# SCH_Central_Unit_for_AgOpenGPS_Zentralba.net
KiCad netlist of a schematic drawn in EasyEDA
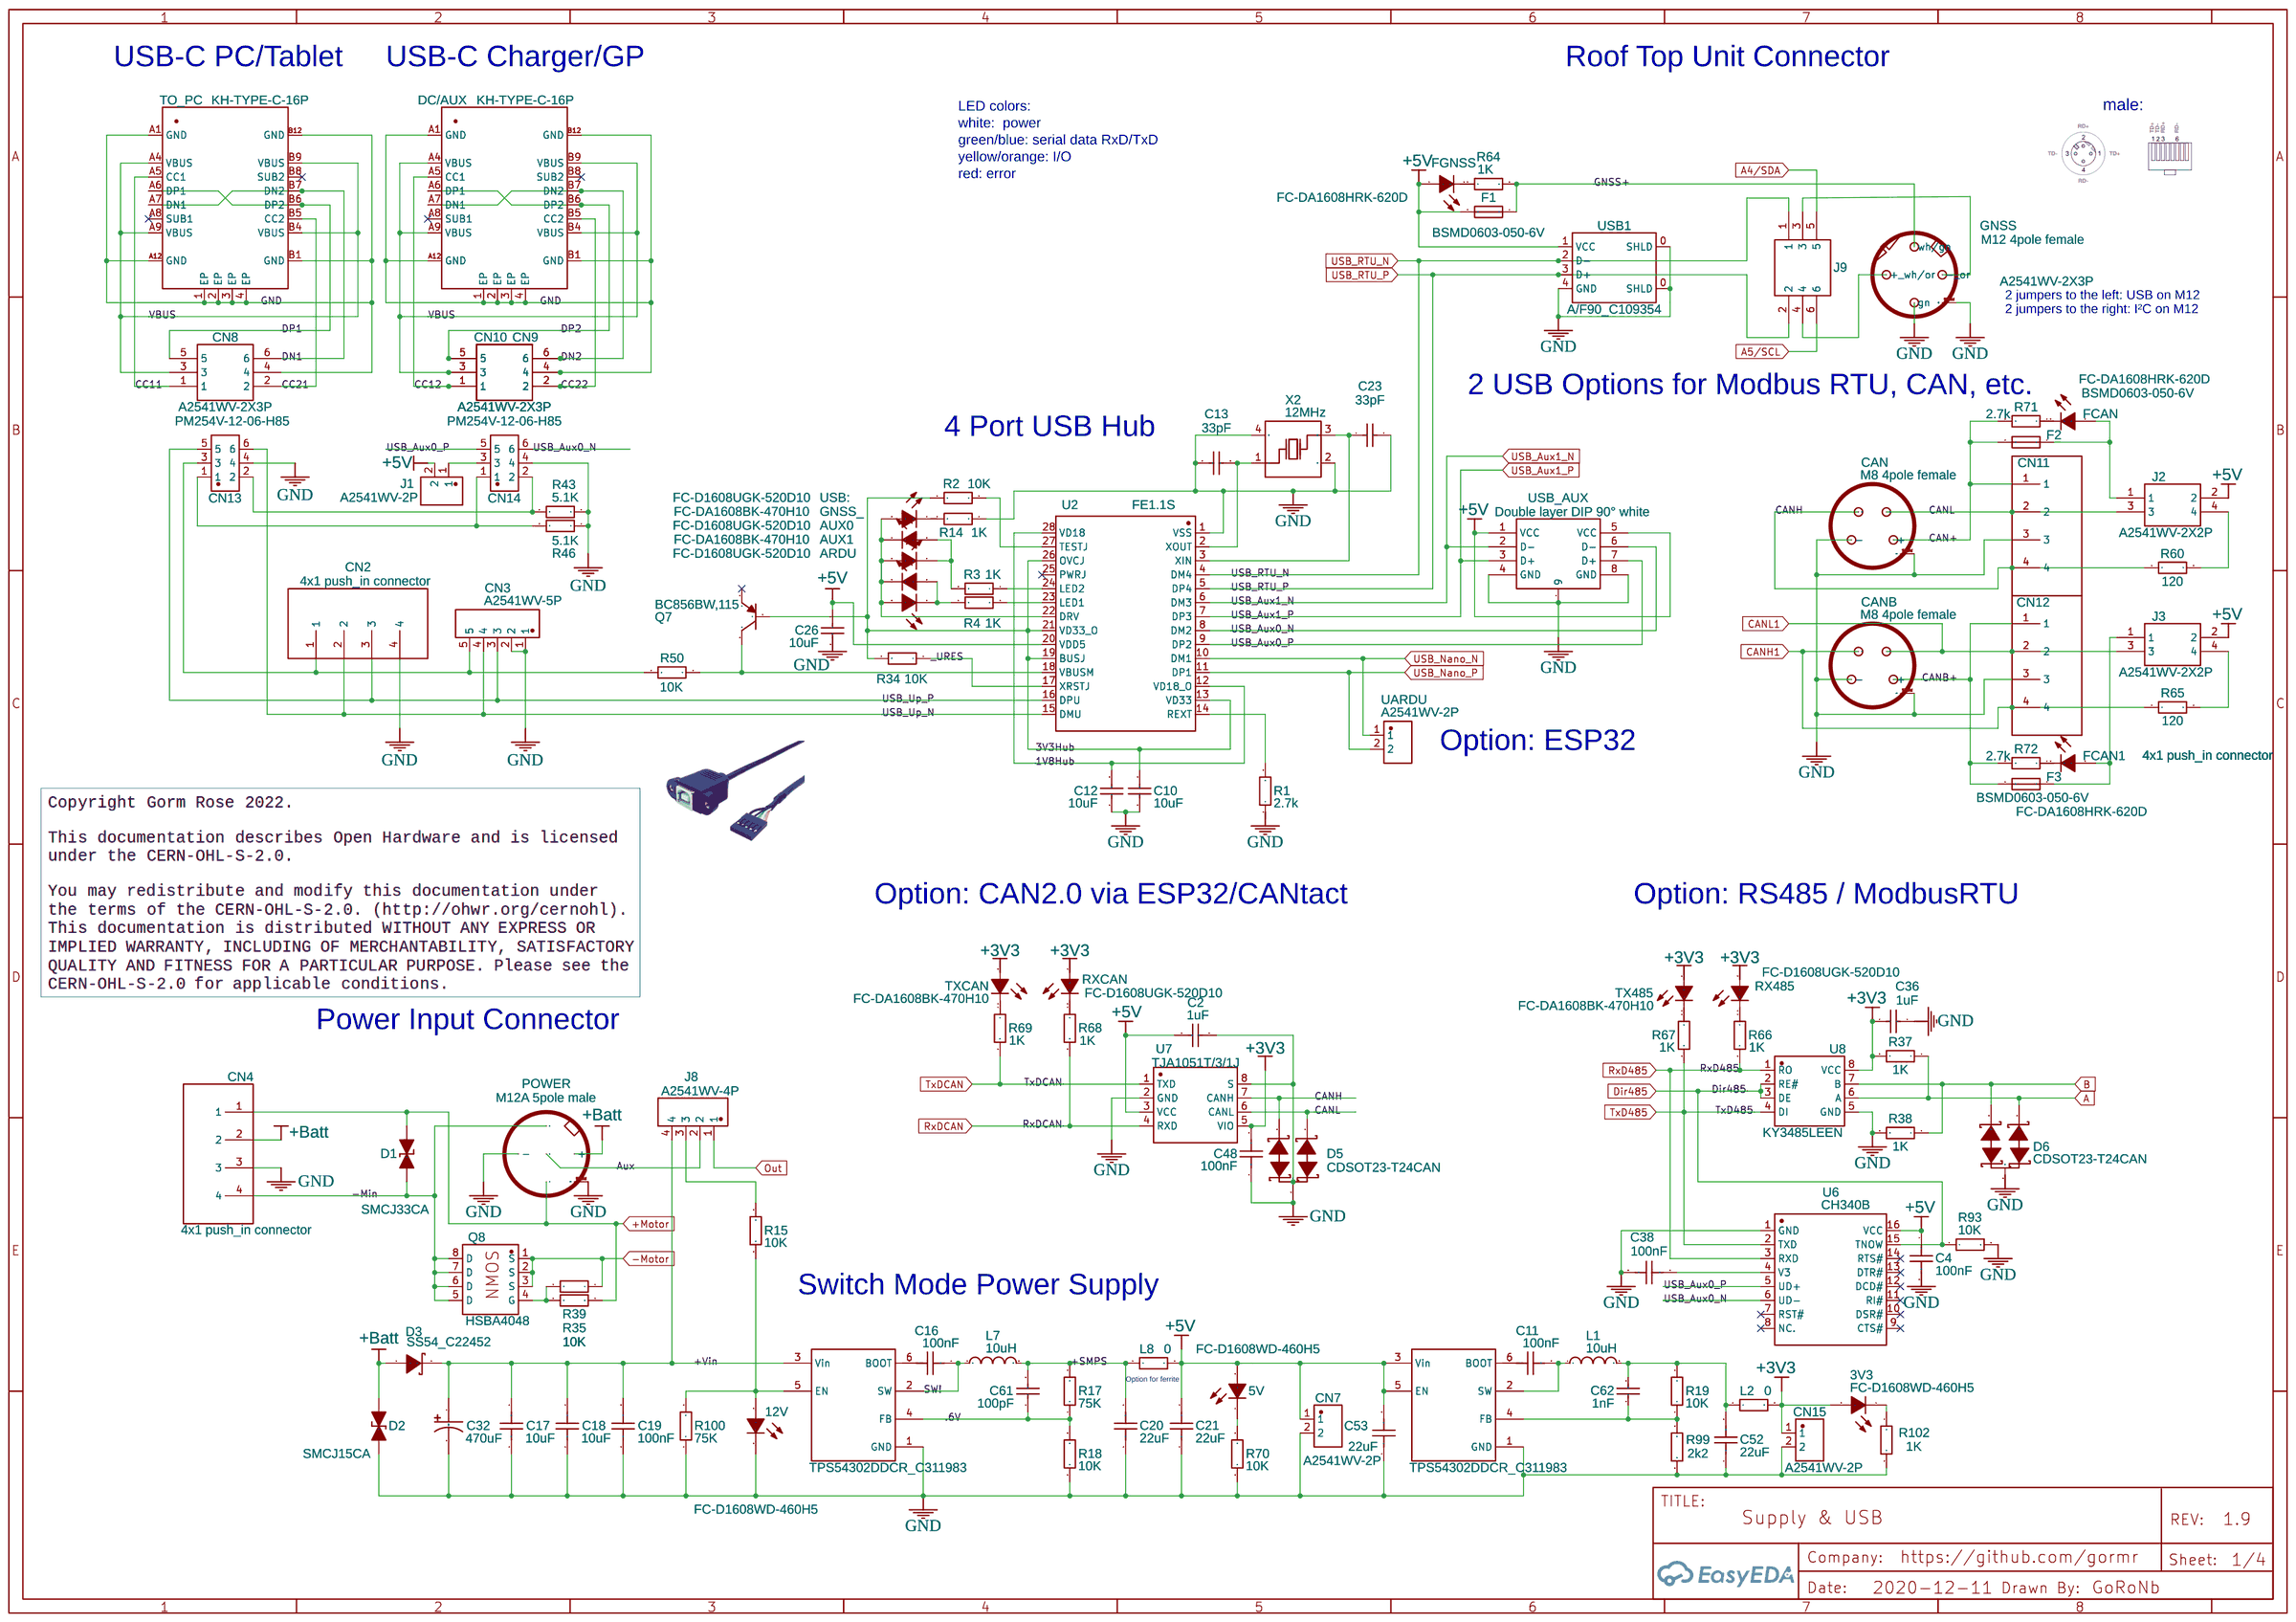
[diagram p0: Supply_USB]
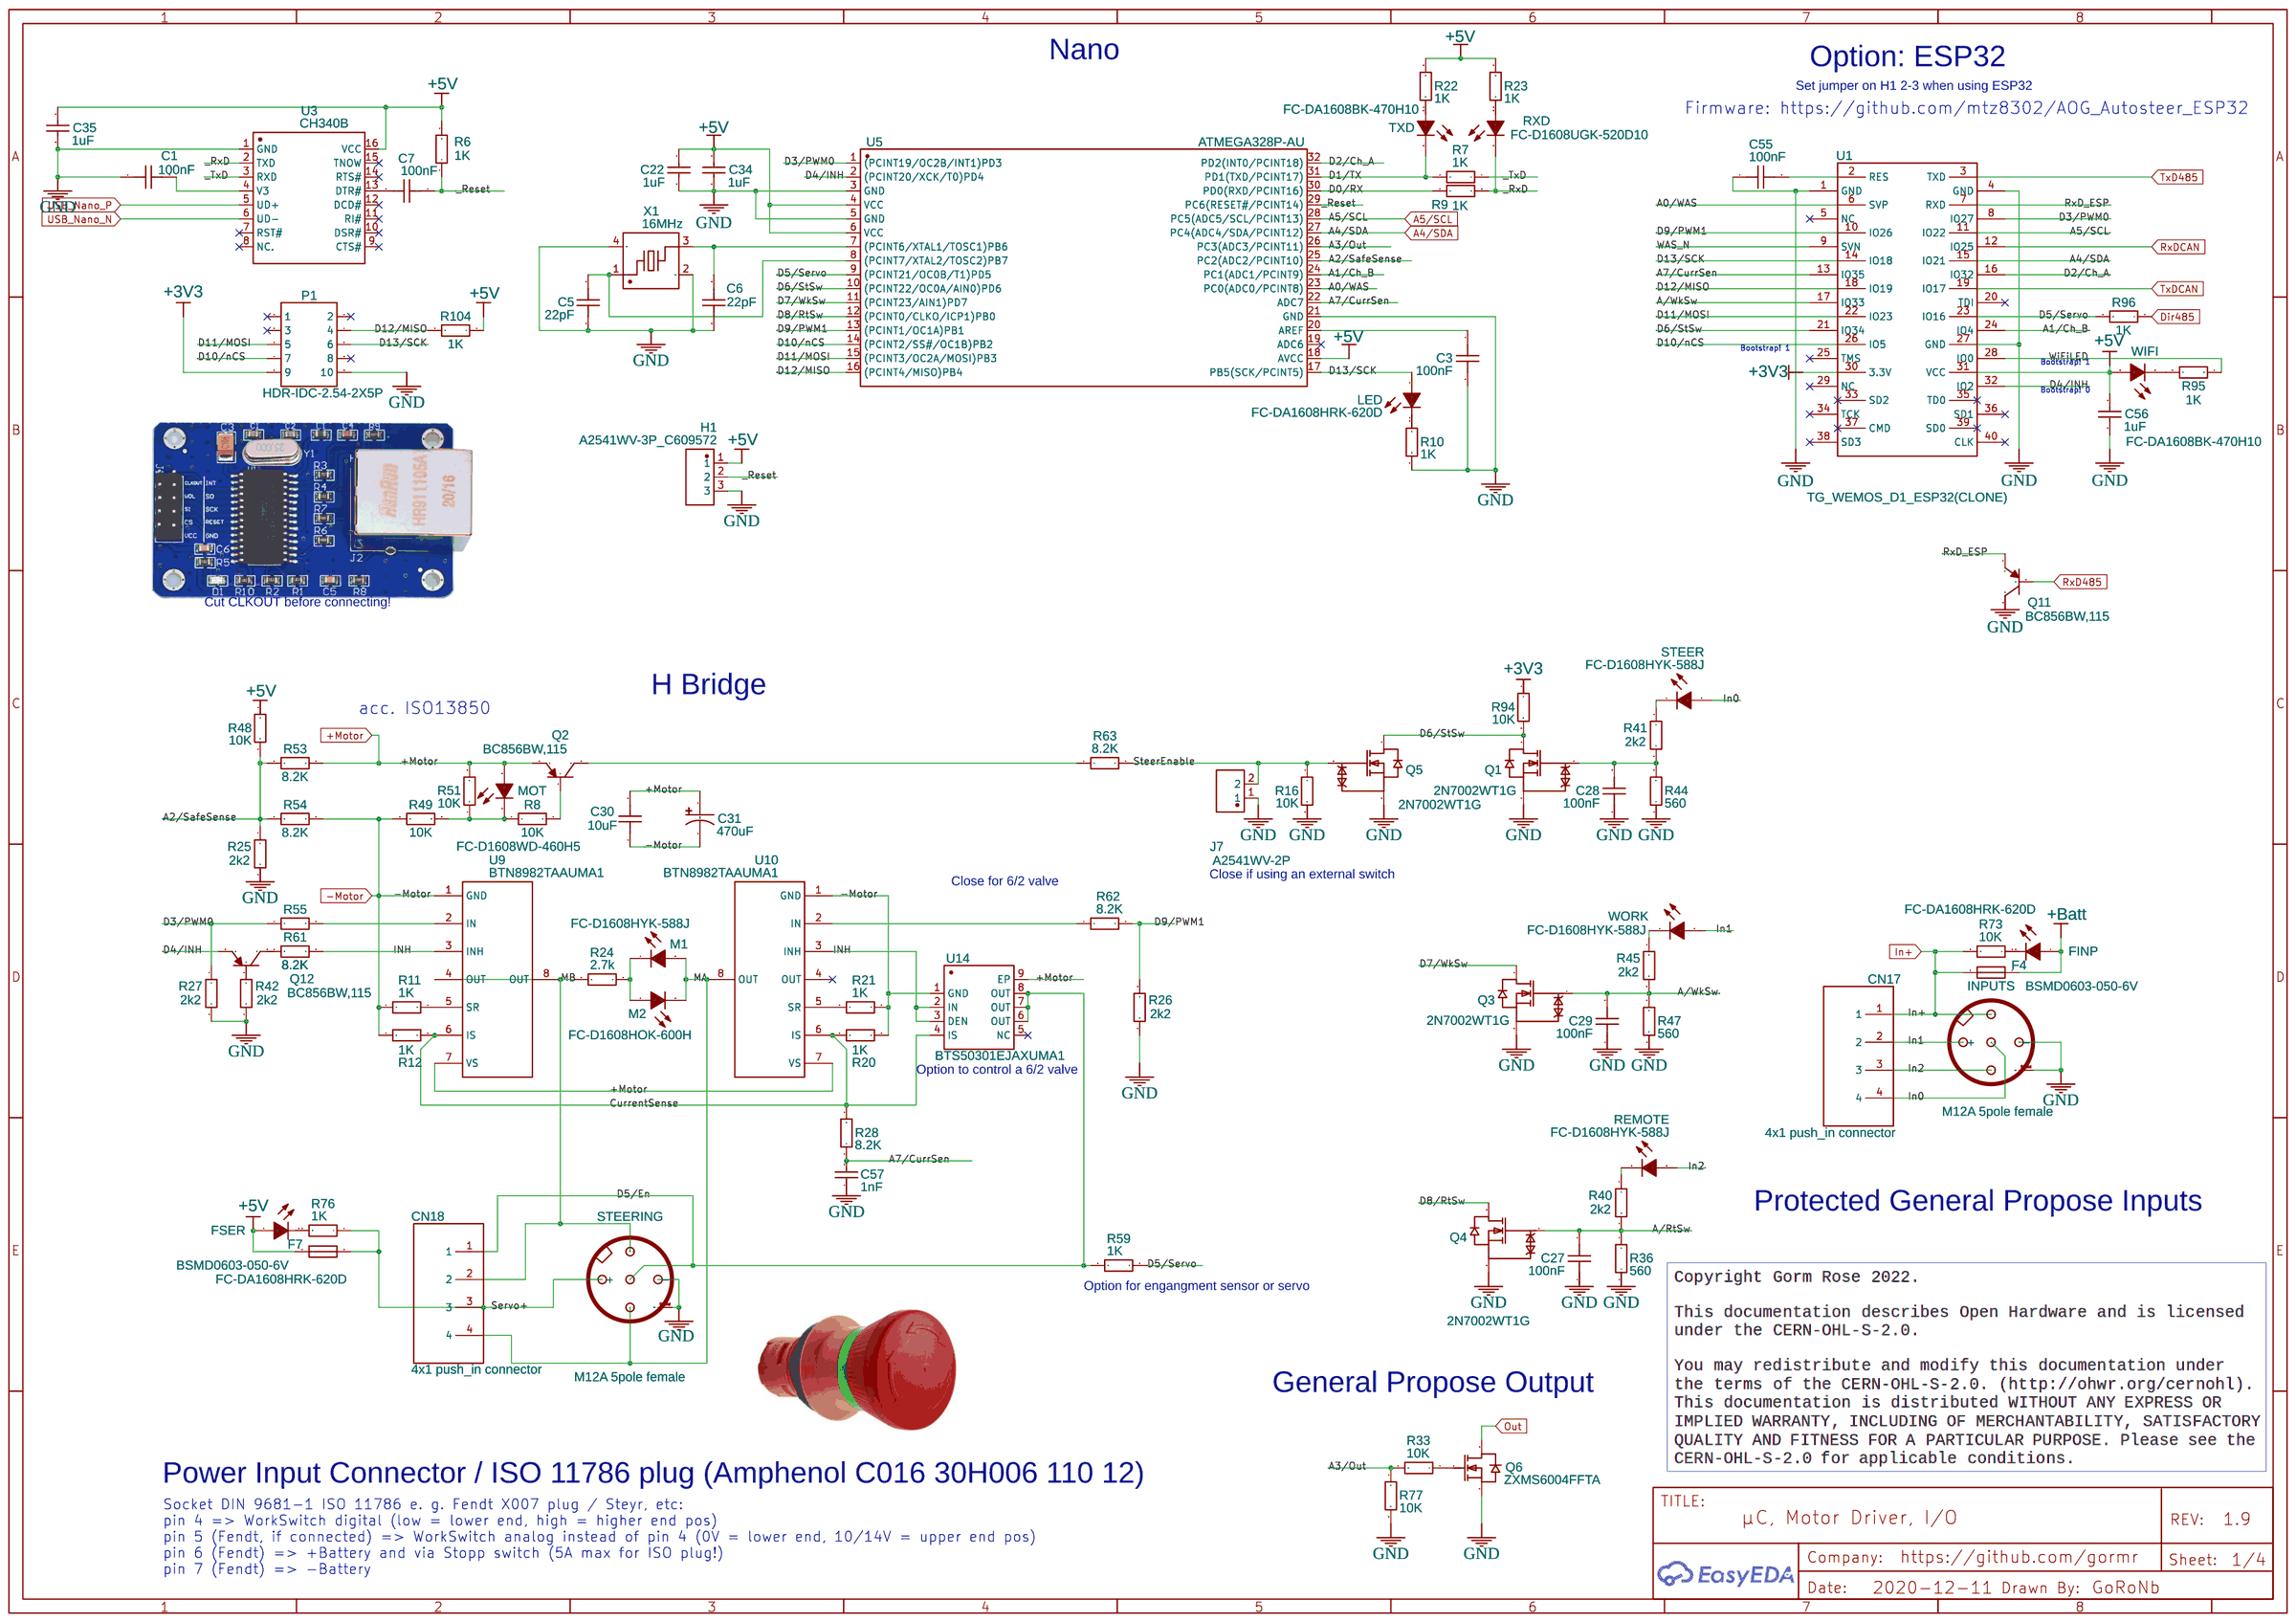
[diagram p1: Motor control]
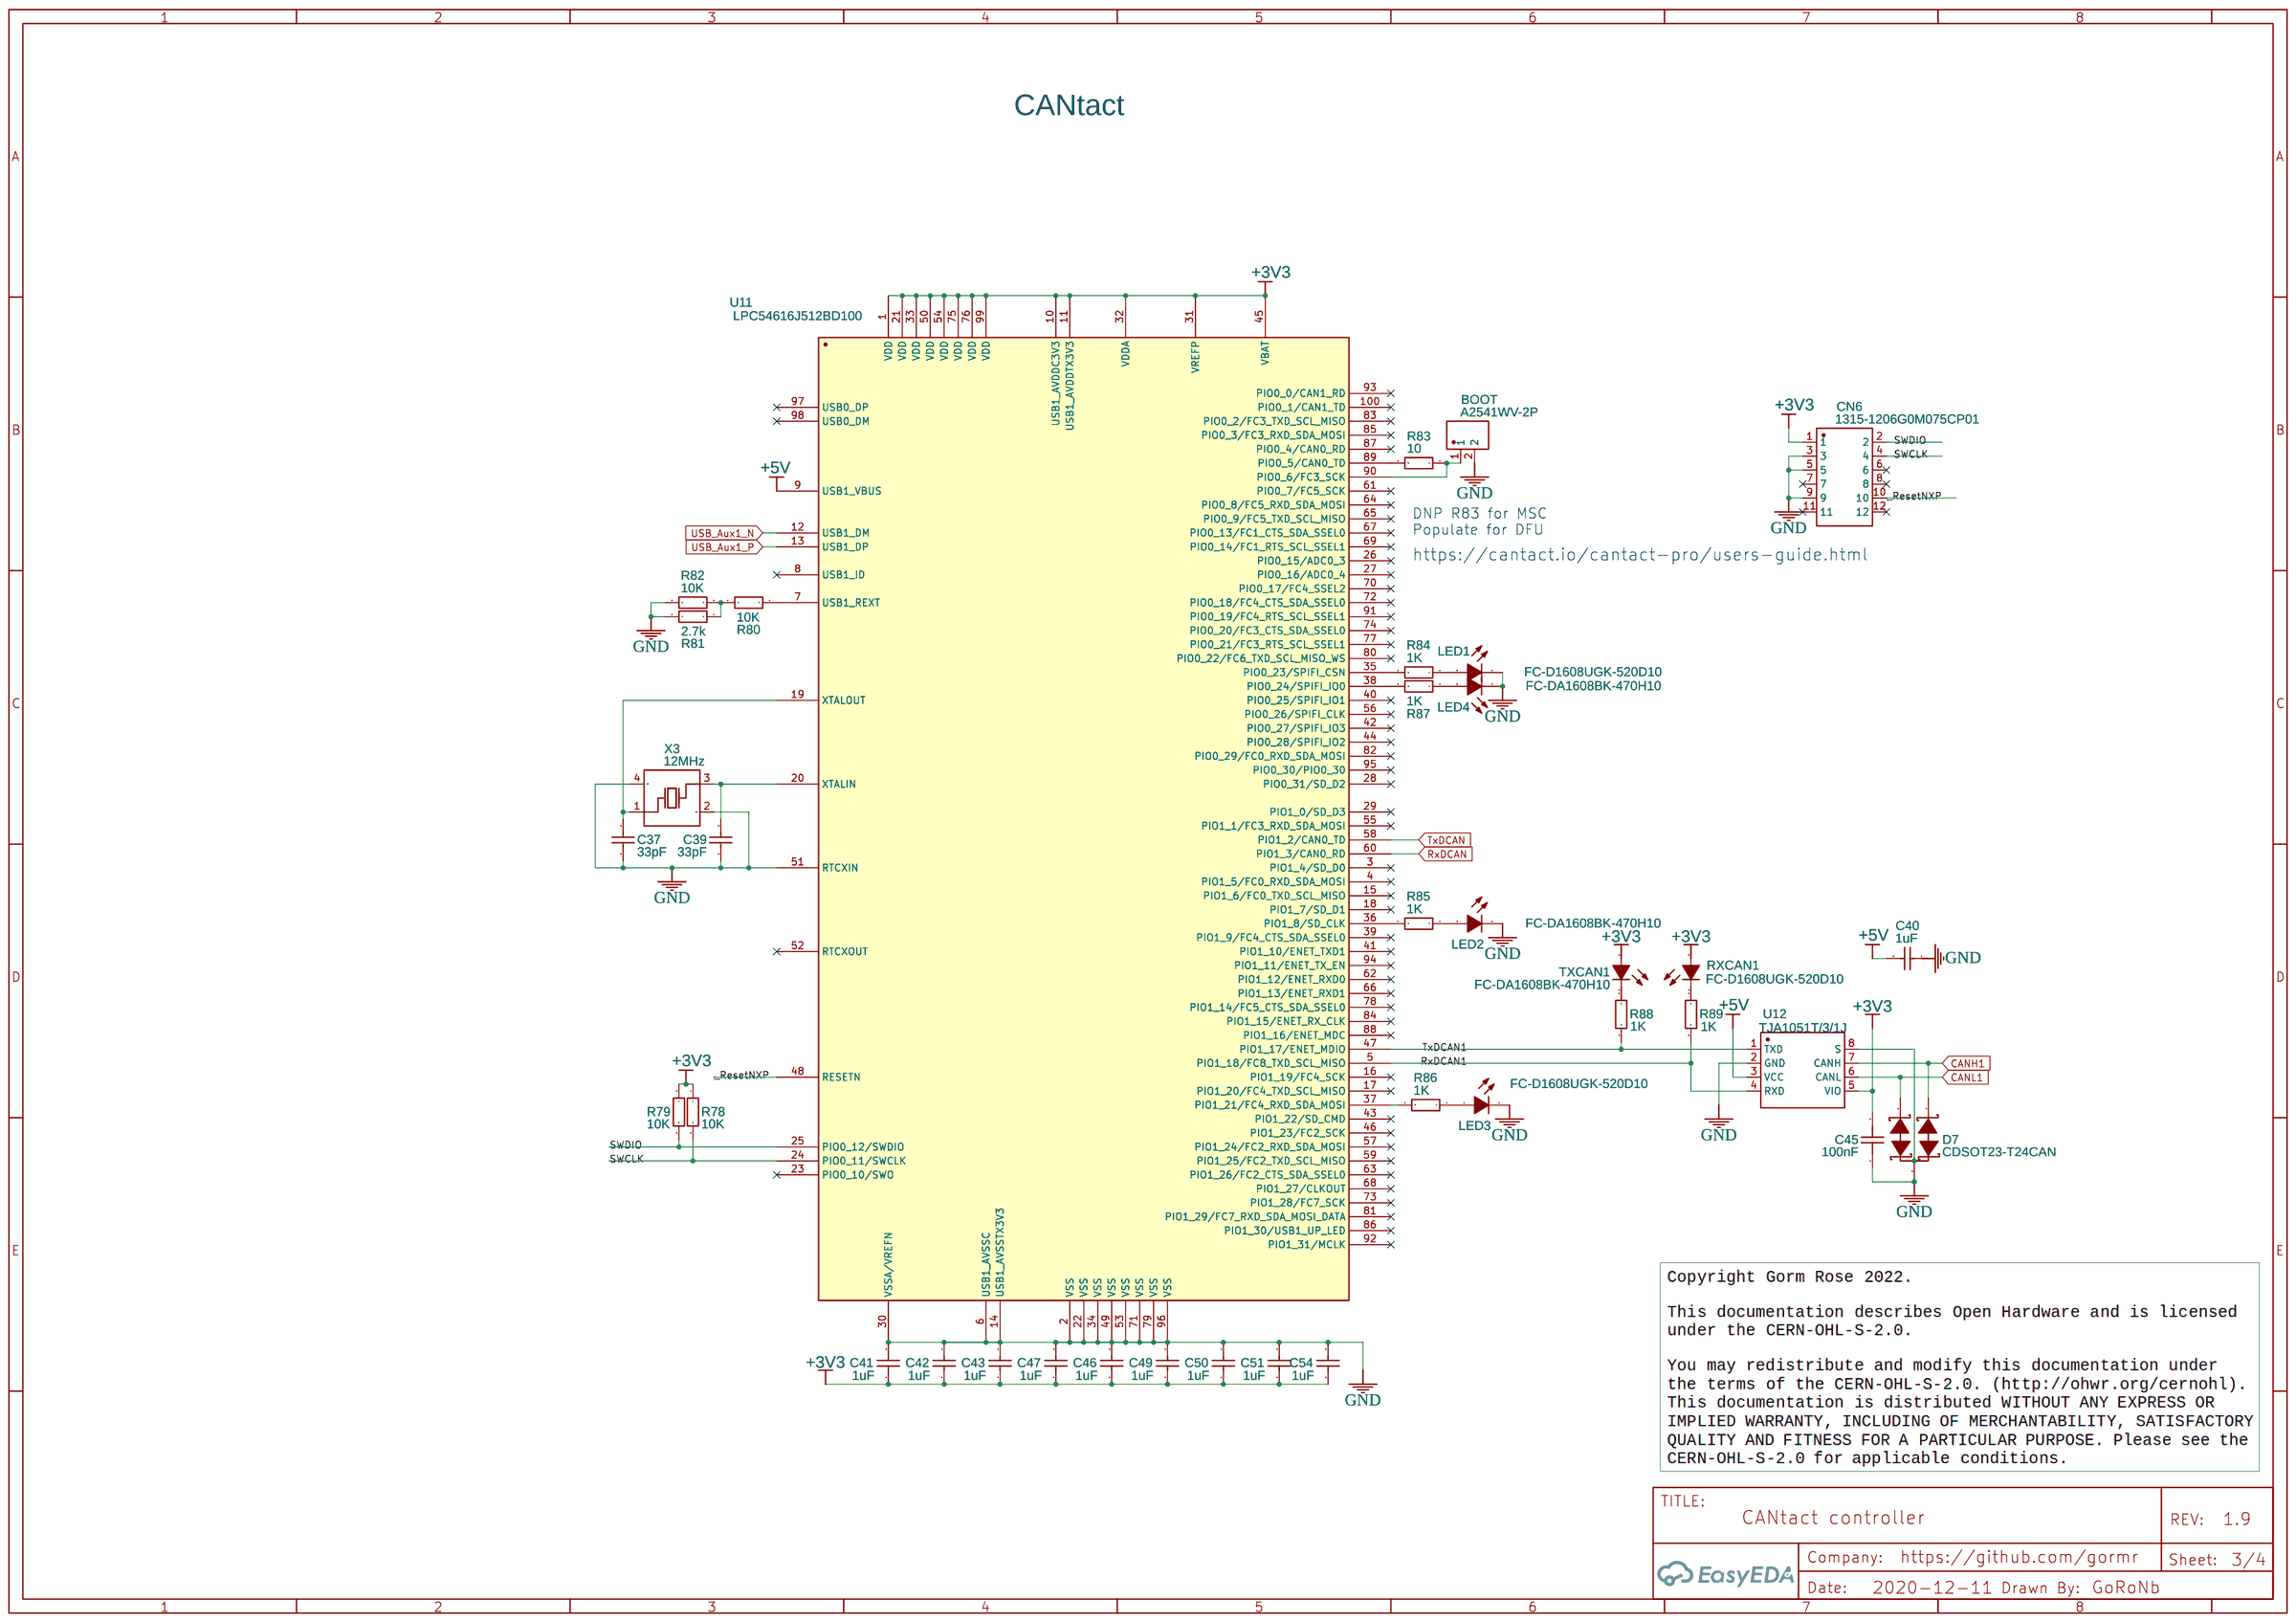
[diagram p2: CANtact]
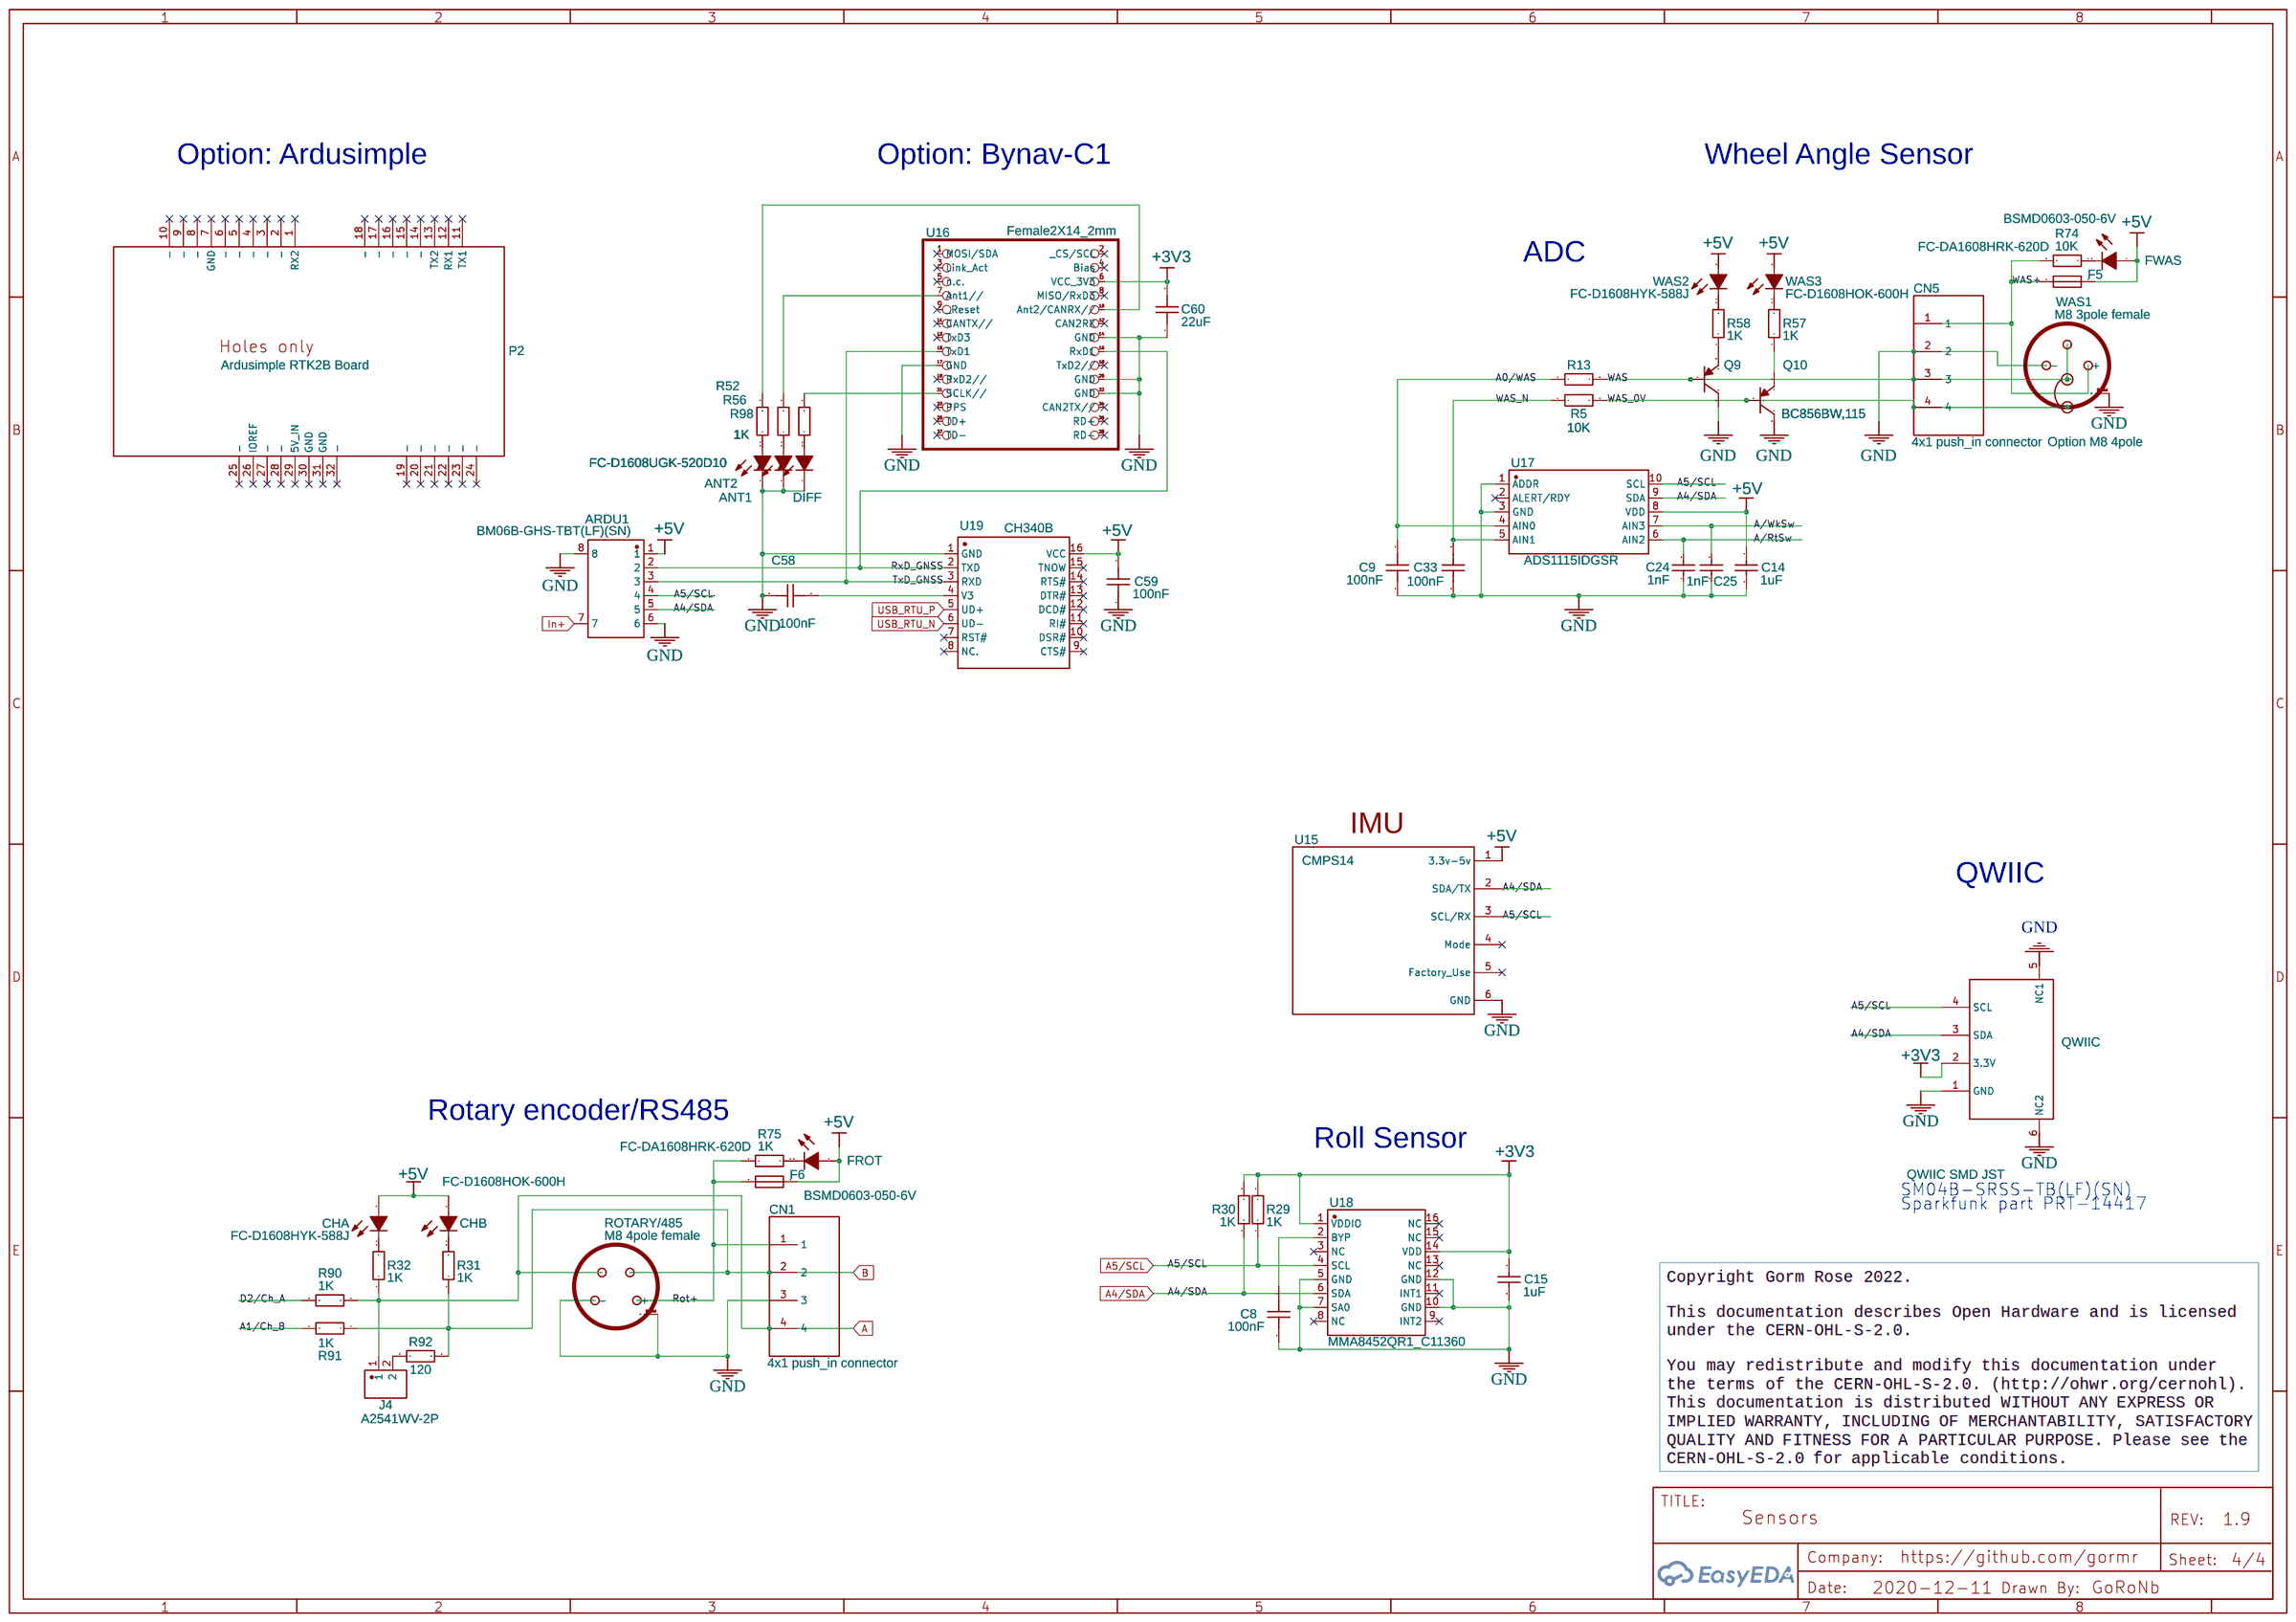
[diagram p3: Sensors]

(export (version "E")
  (design (tool "Eeschema 10.0.6"))
  (components
    (comp (ref "3V3")
      (value "FC-D1608WD-460H5")
      (fields (field (name "BOM_Supplier Part") "C84265"))
      (libsource (lib "") (part "FC-D1608WD-460H5"))
    )
    (comp (ref "5V")
      (value "FC-D1608WD-460H5")
      (fields (field (name "BOM_Supplier Part") "C84265"))
      (libsource (lib "") (part "FC-D1608WD-460H5_2"))
    )
    (comp (ref "12V")
      (value "FC-D1608WD-460H5")
      (fields (field (name "BOM_Supplier Part") "C84265"))
      (libsource (lib "") (part "FC-D1608WD-460H5_1"))
    )
    (comp (ref "ARDU")
      (value "FC-D1608UGK-520D10")
      (fields (field (name "BOM_Supplier Part") "C84267"))
      (libsource (lib "") (part "FC-D1608UGK-520D10_2"))
    )
    (comp (ref "AUX0")
      (value "FC-D1608UGK-520D10")
      (fields (field (name "BOM_Supplier Part") "C84267"))
      (libsource (lib "") (part "FC-D1608UGK-520D10_4"))
    )
    (comp (ref "AUX1")
      (value "FC-DA1608BK-470H10")
      (fields (field (name "BOM_Supplier Part") "C84266"))
      (libsource (lib "") (part "FC-DA1608BK-470H10_3"))
    )
    (comp (ref "C2")
      (value "1uF")
      (fields
        (field (name "BOM_Manufacturer Part") "CL10A105KP8NNNC")
        (field (name "BOM_Supplier Part") "C26413")
      )
      (libsource (lib "") (part "CL10A105KP8NNNC"))
    )
    (comp (ref "C4")
      (value "100nF")
      (fields
        (field (name "BOM_Manufacturer Part") "CC0603JRX7R8BB104")
        (field (name "BOM_Supplier Part") "C327087")
      )
      (libsource (lib "") (part "CC0603JRX7R8BB104_1"))
    )
    (comp (ref "C10")
      (value "10uF")
      (fields
        (field (name "BOM_Manufacturer Part") "0805X106K100")
        (field (name "BOM_Supplier Part") "C105505")
      )
      (libsource (lib "") (part "0805X106K100_1"))
    )
    (comp (ref "C11")
      (value "100nF")
      (fields
        (field (name "BOM_Manufacturer Part") "CC0603JRX7R8BB104")
        (field (name "BOM_Supplier Part") "C327087")
      )
      (libsource (lib "") (part "CC0603JRX7R8BB104_2"))
    )
    (comp (ref "C12")
      (value "10uF")
      (fields
        (field (name "BOM_Manufacturer Part") "0805X106K100")
        (field (name "BOM_Supplier Part") "C105505")
      )
      (libsource (lib "") (part "0805X106K100_2"))
    )
    (comp (ref "C13")
      (value "33pF")
      (fields
        (field (name "BOM_Manufacturer Part") "CL10C330JB8NNNC")
        (field (name "BOM_Supplier Part") "C1663")
      )
      (libsource (lib "") (part "CC0603JRNPO9BN330"))
    )
    (comp (ref "C16")
      (value "100nF")
      (fields
        (field (name "BOM_Manufacturer Part") "CC0603JRX7R8BB104")
        (field (name "BOM_Supplier Part") "C327087")
      )
      (libsource (lib "") (part "CC0603JRX7R8BB104_2"))
    )
    (comp (ref "C17")
      (value "10uF")
      (fields
        (field (name "BOM_Manufacturer Part") "TCC1206X7R106K250HT")
        (field (name "BOM_Supplier Part") "C380364")
      )
      (libsource (lib "") (part "TCC1206X7R106K250HT"))
    )
    (comp (ref "C18")
      (value "10uF")
      (fields
        (field (name "BOM_Manufacturer Part") "TCC1206X7R106K250HT")
        (field (name "BOM_Supplier Part") "C380364")
      )
      (libsource (lib "") (part "TCC1206X7R106K250HT"))
    )
    (comp (ref "C19")
      (value "100nF")
      (fields
        (field (name "BOM_Manufacturer Part") "CC0603JRX7R8BB104")
        (field (name "BOM_Supplier Part") "C327087")
      )
      (libsource (lib "") (part "CC0603JRX7R8BB104"))
    )
    (comp (ref "C20")
      (value "22uF")
      (fields
        (field (name "BOM_Manufacturer Part") "CL21A226MAQNNNE")
        (field (name "BOM_Supplier Part") "C45783")
      )
      (libsource (lib "") (part "CL21A226MAQNNNE"))
    )
    (comp (ref "C21")
      (value "22uF")
      (fields
        (field (name "BOM_Manufacturer Part") "CL21A226MAQNNNE")
        (field (name "BOM_Supplier Part") "C45783")
      )
      (libsource (lib "") (part "CL21A226MAQNNNE"))
    )
    (comp (ref "C23")
      (value "33pF")
      (fields
        (field (name "BOM_Manufacturer Part") "CL10C330JB8NNNC")
        (field (name "BOM_Supplier Part") "C1663")
      )
      (libsource (lib "") (part "CC0603JRNPO9BN330"))
    )
    (comp (ref "C26")
      (value "10uF")
      (fields
        (field (name "BOM_Manufacturer Part") "0805X106K100")
        (field (name "BOM_Supplier Part") "C105505")
      )
      (libsource (lib "") (part "0805X106K100"))
    )
    (comp (ref "C32")
      (value "470uF")
      (fields
        (field (name "BOM_Manufacturer Part") "HV471M016F105R")
        (field (name "BOM_Supplier Part") "C59924")
      )
      (libsource (lib "") (part "RT1E471M1010"))
    )
    (comp (ref "C36")
      (value "1uF")
      (fields
        (field (name "BOM_Manufacturer Part") "CL10A105KP8NNNC")
        (field (name "BOM_Supplier Part") "C26413")
      )
      (libsource (lib "") (part "CL10A105KP8NNNC"))
    )
    (comp (ref "C38")
      (value "100nF")
      (fields
        (field (name "BOM_Manufacturer Part") "CC0603JRX7R8BB104")
        (field (name "BOM_Supplier Part") "C327087")
      )
      (libsource (lib "") (part "CC0603JRX7R8BB104_3"))
    )
    (comp (ref "C48")
      (value "100nF")
      (fields
        (field (name "BOM_Manufacturer Part") "CC0603JRX7R8BB104")
        (field (name "BOM_Supplier Part") "C327087")
      )
      (libsource (lib "") (part "CC0603JRX7R8BB104"))
    )
    (comp (ref "C52")
      (value "22uF")
      (fields
        (field (name "BOM_Manufacturer Part") "CL21A226MAQNNNE")
        (field (name "BOM_Supplier Part") "C45783")
      )
      (libsource (lib "") (part "CL21A226MAQNNNE"))
    )
    (comp (ref "C53")
      (value "22uF")
      (fields
        (field (name "BOM_Manufacturer Part") "CL21A226MAQNNNE")
        (field (name "BOM_Supplier Part") "C45783")
      )
      (libsource (lib "") (part "CL21A226MAQNNNE"))
    )
    (comp (ref "C61")
      (value "100pF")
      (fields
        (field (name "BOM_Manufacturer Part") "CL10C101JB8NNNC")
        (field (name "BOM_Supplier Part") "C14858")
      )
      (libsource (lib "") (part "CL10C101JB8NNNC"))
    )
    (comp (ref "C62")
      (value "1nF")
      (fields
        (field (name "BOM_Manufacturer Part") "0603CG102F500NT")
        (field (name "BOM_Supplier Part") "C507408")
      )
      (libsource (lib "") (part "0603CG102F500NT"))
    )
    (comp (ref "CAN") (value "M8 4pole female") (libsource (lib "") (part "M8 4pole female_1")))
    (comp (ref "CANB") (value "M8 4pole female") (libsource (lib "") (part "M8 4pole female")))
    (comp (ref "CN2")
      (value "4x1 push_in connector")
      (fields
        (field (name "BOM_Manufacturer Part") "1825660000")
        (field (name "BOM_Supplier Part") "281-2044-ND")
      )
      (libsource (lib "") (part "4x1 push_in connector"))
    )
    (comp (ref "CN3")
      (value "A2541WV-5P")
      (fields (field (name "BOM_Supplier Part") "C225480"))
      (libsource (lib "") (part "A2541WV-5P"))
    )
    (comp (ref "CN4")
      (value "4x1 push_in connector")
      (fields
        (field (name "BOM_Manufacturer Part") "1825660000")
        (field (name "BOM_Supplier Part") "281-2044-ND")
      )
      (libsource (lib "") (part "4x1 push_in connector_2"))
    )
    (comp (ref "CN7")
      (value "A2541WV-2P")
      (fields (field (name "BOM_Supplier Part") "C225477"))
      (libsource (lib "") (part "A2541WV-2P_1"))
    )
    (comp (ref "CN8")
      (value "A2541WV-2X3P")
      (fields
        (field (name "BOM_Manufacturer Part") "A2541WV-2x3P")
        (field (name "BOM_Supplier Part") "C225518")
      )
      (libsource (lib "") (part "A2541WV-2X3P"))
    )
    (comp (ref "CN9")
      (value "A2541WV-2X3P")
      (fields
        (field (name "BOM_Manufacturer Part") "A2541WV-2x3P")
        (field (name "BOM_Supplier Part") "C225518")
      )
      (libsource (lib "") (part "A2541WV-2X3P"))
    )
    (comp (ref "CN10")
      (value "A2541WV-2X3P")
      (fields
        (field (name "BOM_Manufacturer Part") "A2541WV-2x3P")
        (field (name "BOM_Supplier Part") "C225518")
      )
      (libsource (lib "") (part "A2541WV-2X3P"))
    )
    (comp (ref "CN11")
      (value "4x1 push_in connector")
      (fields
        (field (name "BOM_Manufacturer Part") "1825660000")
        (field (name "BOM_Supplier Part") "281-2044-ND")
      )
      (libsource (lib "") (part "4x1 push_in connector_1"))
    )
    (comp (ref "CN12")
      (value "4x1 push_in connector")
      (fields
        (field (name "BOM_Manufacturer Part") "1825660000")
        (field (name "BOM_Supplier Part") "281-2044-ND")
      )
      (libsource (lib "") (part "4x1 push_in connector_1"))
    )
    (comp (ref "CN13")
      (value "PM254V-12-06-H85")
      (fields (field (name "BOM_Supplier Part") "C541853"))
      (libsource (lib "") (part "PM254V-12-06-H85"))
    )
    (comp (ref "CN14")
      (value "PM254V-12-06-H85")
      (fields (field (name "BOM_Supplier Part") "C541853"))
      (libsource (lib "") (part "PM254V-12-06-H85"))
    )
    (comp (ref "CN15")
      (value "A2541WV-2P")
      (fields (field (name "BOM_Supplier Part") "C225477"))
      (libsource (lib "") (part "A2541WV-2P_1"))
    )
    (comp (ref "D1")
      (value "SMCJ33CA")
      (fields (field (name "BOM_Supplier Part") "C310048"))
      (libsource (lib "") (part "SMCJ33CA_C310048"))
    )
    (comp (ref "D2")
      (value "SMCJ15CA")
      (fields (field (name "BOM_Supplier Part") "C310017"))
      (libsource (lib "") (part "SMCJ15CA_C310017"))
    )
    (comp (ref "D3")
      (value "SS54_C22452")
      (fields (field (name "BOM_Manufacturer Part") "SS54") (field (name "BOM_Supplier Part") "C22452"))
      (libsource (lib "") (part "SS54_C22452"))
    )
    (comp (ref "D5")
      (value "CDSOT23-T24CAN")
      (fields (field (name "BOM_Supplier Part") "C252430"))
      (libsource (lib "") (part "CDSOT23-T24CAN"))
    )
    (comp (ref "D6")
      (value "CDSOT23-T24CAN")
      (fields (field (name "BOM_Supplier Part") "C252430"))
      (libsource (lib "") (part "CDSOT23-T24CAN"))
    )
    (comp (ref "DC/AUX")
      (value "KH-TYPE-C-16P")
      (fields (field (name "BOM_Supplier Part") "C709357"))
      (libsource (lib "") (part "KH-TYPE-C-16P_1"))
    )
    (comp (ref "F1")
      (value "BSMD0603-050-6V")
      (fields (field (name "BOM_Supplier Part") "C883095"))
      (libsource (lib "") (part "BSMD0603-050-6V"))
    )
    (comp (ref "F2")
      (value "BSMD0603-050-6V")
      (fields (field (name "BOM_Supplier Part") "C883095"))
      (libsource (lib "") (part "BSMD0603-050-6V"))
    )
    (comp (ref "F3")
      (value "BSMD0603-050-6V")
      (fields (field (name "BOM_Supplier Part") "C883095"))
      (libsource (lib "") (part "BSMD0603-050-6V"))
    )
    (comp (ref "FCAN")
      (value "FC-DA1608HRK-620D")
      (fields (field (name "BOM_Supplier Part") "C84263"))
      (libsource (lib "") (part "FC-DA1608HRK-620D"))
    )
    (comp (ref "FCAN1")
      (value "FC-DA1608HRK-620D")
      (fields (field (name "BOM_Supplier Part") "C84263"))
      (libsource (lib "") (part "FC-DA1608HRK-620D"))
    )
    (comp (ref "FGNSS")
      (value "FC-DA1608HRK-620D")
      (fields (field (name "BOM_Supplier Part") "C84263"))
      (libsource (lib "") (part "FC-DA1608HRK-620D_1"))
    )
    (comp (ref "GNSS") (value "M12 4pole female") (libsource (lib "") (part "M12 4pole female")))
    (comp (ref "GNSS_")
      (value "FC-DA1608BK-470H10")
      (fields (field (name "BOM_Supplier Part") "C84266"))
      (libsource (lib "") (part "FC-DA1608BK-470H10"))
    )
    (comp (ref "J1")
      (value "A2541WV-2P")
      (fields (field (name "BOM_Supplier Part") "C225477"))
      (libsource (lib "") (part "A2541WV-2P"))
    )
    (comp (ref "J2")
      (value "A2541WV-2X2P")
      (fields
        (field (name "BOM_Manufacturer Part") "A2541WV-2x2P")
        (field (name "BOM_Supplier Part") "C225517")
      )
      (libsource (lib "") (part "A2541WV-2X2P"))
    )
    (comp (ref "J3")
      (value "A2541WV-2X2P")
      (fields
        (field (name "BOM_Manufacturer Part") "A2541WV-2x2P")
        (field (name "BOM_Supplier Part") "C225517")
      )
      (libsource (lib "") (part "A2541WV-2X2P"))
    )
    (comp (ref "J8")
      (value "A2541WV-4P")
      (fields (field (name "BOM_Supplier Part") "C225479"))
      (libsource (lib "") (part "A2541WV-4P"))
    )
    (comp (ref "J9")
      (value "A2541WV-2X3P")
      (fields
        (field (name "BOM_Manufacturer Part") "A2541WV-2x3P")
        (field (name "BOM_Supplier Part") "C225518")
      )
      (libsource (lib "") (part "A2541WV-2X3P_1"))
    )
    (comp (ref "L1")
      (value "10uH")
      (fields
        (field (name "BOM_Manufacturer Part") "MWSA0503-100MT")
        (field (name "BOM_Supplier Part") "C139506")
      )
      (libsource (lib "") (part "MWSA0503-100MT_1"))
    )
    (comp (ref "L2")
      (value "0")
      (fields
        (field (name "BOM_Manufacturer Part") "0603WAF0000T5E")
        (field (name "BOM_Supplier Part") "C21189")
      )
      (libsource (lib "") (part "0603WAF0000T5E"))
    )
    (comp (ref "L7")
      (value "10uH")
      (fields
        (field (name "BOM_Manufacturer Part") "MWSA0503-100MT")
        (field (name "BOM_Supplier Part") "C139506")
      )
      (libsource (lib "") (part "MWSA0503-100MT"))
    )
    (comp (ref "L8")
      (value "0")
      (fields
        (field (name "BOM_Manufacturer Part") "0603WAF0000T5E")
        (field (name "BOM_Supplier Part") "C21189")
      )
      (libsource (lib "") (part "0603WAF0000T5E"))
    )
    (comp (ref "POWER") (value "M12A 5pole male") (libsource (lib "") (part "M12A 5pole male")))
    (comp (ref "Q7")
      (value "BC856BW,115")
      (fields (field (name "BOM_Supplier Part") "C28063"))
      (libsource (lib "") (part "BC856BW,115"))
    )
    (comp (ref "Q8")
      (value "HSBA4048")
      (fields (field (name "BOM_Supplier Part") "C508827"))
      (libsource (lib "") (part "HSBA4048"))
    )
    (comp (ref "R1")
      (value "2.7k")
      (fields (field (name "BOM_Manufacturer Part") "RTT03272JTP"))
      (libsource (lib "") (part "RTT03473JTP"))
    )
    (comp (ref "R2")
      (value "10K")
      (fields
        (field (name "BOM_Manufacturer Part") "RTT03103JTP")
        (field (name "BOM_Supplier Part") "C103210")
      )
      (libsource (lib "") (part "RTT03103JTP_1"))
    )
    (comp (ref "R3")
      (value "1K")
      (fields
        (field (name "BOM_Manufacturer Part") "RTT03102JTP")
        (field (name "BOM_Supplier Part") "C103209")
      )
      (libsource (lib "") (part "RTT03102JTP_1"))
    )
    (comp (ref "R4")
      (value "1K")
      (fields
        (field (name "BOM_Manufacturer Part") "RTT03102JTP")
        (field (name "BOM_Supplier Part") "C103209")
      )
      (libsource (lib "") (part "RTT03102JTP_2"))
    )
    (comp (ref "R14")
      (value "1K")
      (fields
        (field (name "BOM_Manufacturer Part") "RTT03102JTP")
        (field (name "BOM_Supplier Part") "C103209")
      )
      (libsource (lib "") (part "RTT03102JTP_1"))
    )
    (comp (ref "R15")
      (value "10K")
      (fields
        (field (name "BOM_Manufacturer Part") "RTT03103JTP")
        (field (name "BOM_Supplier Part") "C103210")
      )
      (libsource (lib "") (part "RTT03103JTP_2"))
    )
    (comp (ref "R17")
      (value "75K")
      (fields
        (field (name "BOM_Manufacturer Part") "0603WAF7502T5E")
        (field (name "BOM_Supplier Part") "C23242")
      )
      (libsource (lib "") (part "0603WAF7502T5E"))
    )
    (comp (ref "R18")
      (value "10K")
      (fields
        (field (name "BOM_Manufacturer Part") "RTT03103JTP")
        (field (name "BOM_Supplier Part") "C103210")
      )
      (libsource (lib "") (part "RTT03103JTP_2"))
    )
    (comp (ref "R19")
      (value "10K")
      (fields
        (field (name "BOM_Manufacturer Part") "RTT03103JTP")
        (field (name "BOM_Supplier Part") "C103210")
      )
      (libsource (lib "") (part "RTT03103JTP_2"))
    )
    (comp (ref "R34")
      (value "10K")
      (fields
        (field (name "BOM_Manufacturer Part") "RTT03103JTP")
        (field (name "BOM_Supplier Part") "C103210")
      )
      (libsource (lib "") (part "RTT03103JTP_1"))
    )
    (comp (ref "R35")
      (value "10K")
      (fields
        (field (name "BOM_Manufacturer Part") "RTT03103JTP")
        (field (name "BOM_Supplier Part") "C103210")
      )
      (libsource (lib "") (part "RTT03103JTP_1"))
    )
    (comp (ref "R37")
      (value "1K")
      (fields
        (field (name "BOM_Manufacturer Part") "RTT03102JTP")
        (field (name "BOM_Supplier Part") "C103209")
      )
      (libsource (lib "") (part "RTT03102JTP_1"))
    )
    (comp (ref "R38")
      (value "1K")
      (fields
        (field (name "BOM_Manufacturer Part") "RTT03102JTP")
        (field (name "BOM_Supplier Part") "C103209")
      )
      (libsource (lib "") (part "RTT03102JTP_1"))
    )
    (comp (ref "R39")
      (value "10K")
      (fields
        (field (name "BOM_Manufacturer Part") "RTT03103JTP")
        (field (name "BOM_Supplier Part") "C103210")
      )
      (libsource (lib "") (part "RTT03103JTP_1"))
    )
    (comp (ref "R43")
      (value "5.1K")
      (fields
        (field (name "BOM_Manufacturer Part") "0603WAF5101T5E")
        (field (name "BOM_Supplier Part") "C23186")
      )
      (libsource (lib "") (part "0603WAF5101T5E"))
    )
    (comp (ref "R46")
      (value "5.1K")
      (fields
        (field (name "BOM_Manufacturer Part") "0603WAF5101T5E")
        (field (name "BOM_Supplier Part") "C23186")
      )
      (libsource (lib "") (part "0603WAF5101T5E"))
    )
    (comp (ref "R50")
      (value "10K")
      (fields
        (field (name "BOM_Manufacturer Part") "RTT03103JTP")
        (field (name "BOM_Supplier Part") "C103210")
      )
      (libsource (lib "") (part "RTT03103JTP"))
    )
    (comp (ref "R60")
      (value "120")
      (fields
        (field (name "BOM_Manufacturer Part") "RTT06121JTP")
        (field (name "BOM_Supplier Part") "C104621")
      )
      (libsource (lib "") (part "RTT06121JTP"))
    )
    (comp (ref "R64")
      (value "1K")
      (fields
        (field (name "BOM_Manufacturer Part") "RTT03102JTP")
        (field (name "BOM_Supplier Part") "C103209")
      )
      (libsource (lib "") (part "RTT03102JTP_2"))
    )
    (comp (ref "R65")
      (value "120")
      (fields
        (field (name "BOM_Manufacturer Part") "RTT06121JTP")
        (field (name "BOM_Supplier Part") "C104621")
      )
      (libsource (lib "") (part "RTT06121JTP"))
    )
    (comp (ref "R66")
      (value "1K")
      (fields
        (field (name "BOM_Manufacturer Part") "RTT03102JTP")
        (field (name "BOM_Supplier Part") "C103209")
      )
      (libsource (lib "") (part "RTT03102JTP"))
    )
    (comp (ref "R67")
      (value "1K")
      (fields
        (field (name "BOM_Manufacturer Part") "RTT03102JTP")
        (field (name "BOM_Supplier Part") "C103209")
      )
      (libsource (lib "") (part "RTT03102JTP"))
    )
    (comp (ref "R68")
      (value "1K")
      (fields
        (field (name "BOM_Manufacturer Part") "RTT03102JTP")
        (field (name "BOM_Supplier Part") "C103209")
      )
      (libsource (lib "") (part "RTT03102JTP"))
    )
    (comp (ref "R69")
      (value "1K")
      (fields
        (field (name "BOM_Manufacturer Part") "RTT03102JTP")
        (field (name "BOM_Supplier Part") "C103209")
      )
      (libsource (lib "") (part "RTT03102JTP"))
    )
    (comp (ref "R70")
      (value "10K")
      (fields
        (field (name "BOM_Manufacturer Part") "RTT03103JTP")
        (field (name "BOM_Supplier Part") "C103210")
      )
      (libsource (lib "") (part "RTT03103JTP_2"))
    )
    (comp (ref "R71")
      (value "2.7k")
      (fields (field (name "BOM_Manufacturer Part") "RTT03272JTP"))
      (libsource (lib "") (part "RTT03473JTP_1"))
    )
    (comp (ref "R72")
      (value "2.7k")
      (fields (field (name "BOM_Manufacturer Part") "RTT03272JTP"))
      (libsource (lib "") (part "RTT03473JTP_1"))
    )
    (comp (ref "R93")
      (value "10K")
      (fields
        (field (name "BOM_Manufacturer Part") "RTT03103JTP")
        (field (name "BOM_Supplier Part") "C103210")
      )
      (libsource (lib "") (part "RTT03103JTP"))
    )
    (comp (ref "R99")
      (value "2k2")
      (fields
        (field (name "BOM_Manufacturer Part") "RTT03222JTP")
        (field (name "BOM_Supplier Part") "C103203")
      )
      (libsource (lib "") (part "RTT03100JTP"))
    )
    (comp (ref "R100")
      (value "75K")
      (fields
        (field (name "BOM_Manufacturer Part") "0603WAF7502T5E")
        (field (name "BOM_Supplier Part") "C23242")
      )
      (libsource (lib "") (part "0603WAF7502T5E"))
    )
    (comp (ref "R102")
      (value "1K")
      (fields
        (field (name "BOM_Manufacturer Part") "RTT03102JTP")
        (field (name "BOM_Supplier Part") "C103209")
      )
      (libsource (lib "") (part "RTT03102JTP"))
    )
    (comp (ref "RX485")
      (value "FC-D1608UGK-520D10")
      (fields (field (name "BOM_Supplier Part") "C84267"))
      (libsource (lib "") (part "FC-D1608UGK-520D10"))
    )
    (comp (ref "RXCAN")
      (value "FC-D1608UGK-520D10")
      (fields (field (name "BOM_Supplier Part") "C84267"))
      (libsource (lib "") (part "FC-D1608UGK-520D10_1"))
    )
    (comp (ref "TO_PC")
      (value "KH-TYPE-C-16P")
      (fields (field (name "BOM_Supplier Part") "C709357"))
      (libsource (lib "") (part "KH-TYPE-C-16P"))
    )
    (comp (ref "TX485")
      (value "FC-DA1608BK-470H10")
      (fields (field (name "BOM_Supplier Part") "C84266"))
      (libsource (lib "") (part "FC-DA1608BK-470H10_1"))
    )
    (comp (ref "TXCAN")
      (value "FC-DA1608BK-470H10")
      (fields (field (name "BOM_Supplier Part") "C84266"))
      (libsource (lib "") (part "FC-DA1608BK-470H10_2"))
    )
    (comp (ref "U2")
      (value "FE1.1S")
      (fields (field (name "BOM_Supplier Part") "C9359"))
      (libsource (lib "") (part "FE1.1S"))
    )
    (comp (ref "U4")
      (value "TPS54302DDCR_C311983")
      (fields
        (field (name "BOM_Manufacturer Part") "TPS54302DDCR")
        (field (name "BOM_Supplier Part") "C311983")
      )
      (libsource (lib "") (part "TPS56339"))
    )
    (comp (ref "U6")
      (value "CH340B")
      (fields (field (name "BOM_Supplier Part") "C81010"))
      (libsource (lib "") (part "CH340B"))
    )
    (comp (ref "U7")
      (value "TJA1051T/3/1J")
      (fields (field (name "BOM_Supplier Part") "C38695"))
      (libsource (lib "") (part "TJA1051T/3/1J"))
    )
    (comp (ref "U8")
      (value "KY3485LEEN")
      (fields (field (name "BOM_Supplier Part") "C428902"))
      (libsource (lib "") (part "KY3485LEEN"))
    )
    (comp (ref "U13")
      (value "TPS54302DDCR_C311983")
      (fields
        (field (name "BOM_Manufacturer Part") "TPS54302DDCR")
        (field (name "BOM_Supplier Part") "C311983")
      )
      (libsource (lib "") (part "TPS56339"))
    )
    (comp (ref "UARDU")
      (value "A2541WV-2P")
      (fields (field (name "BOM_Supplier Part") "C225477"))
      (libsource (lib "") (part "A2541WV-2P_2"))
    )
    (comp (ref "USB1")
      (value "A/F90_C109354")
      (fields (field (name "BOM_Supplier Part") "C109354"))
      (libsource (lib "") (part "A/F90_C109354"))
    )
    (comp (ref "USB:")
      (value "FC-D1608UGK-520D10")
      (fields (field (name "BOM_Supplier Part") "C84267"))
      (libsource (lib "") (part "FC-D1608UGK-520D10_3"))
    )
    (comp (ref "USB_AUX")
      (value "Double layer DIP 90° white")
      (fields (field (name "BOM_Supplier Part") "C2341"))
      (libsource (lib "") (part "Double layer DIP 90° white"))
    )
    (comp (ref "X2")
      (value "12MHz")
      (fields
        (field (name "BOM_Manufacturer Part") "X322512MSB4SI")
        (field (name "BOM_Supplier Part") "C9002")
      )
      (libsource (lib "") (part "X322512MSB4SI"))
    )
    (comp (ref "C1")
      (value "100nF")
      (fields
        (field (name "BOM_Manufacturer Part") "CC0603JRX7R8BB104")
        (field (name "BOM_Supplier Part") "C327087")
      )
      (libsource (lib "") (part "CC0603JRX7R8BB104_2"))
    )
    (comp (ref "C3")
      (value "100nF")
      (fields
        (field (name "BOM_Manufacturer Part") "CC0603JRX7R8BB104")
        (field (name "BOM_Supplier Part") "C327087")
      )
      (libsource (lib "") (part "CC0603JRX7R8BB104"))
    )
    (comp (ref "C5")
      (value "22pF")
      (fields
        (field (name "BOM_Manufacturer Part") "TCC0603COG220J500CT")
        (field (name "BOM_Supplier Part") "C376775")
      )
      (libsource (lib "") (part "TCC0603COG220J500CT"))
    )
    (comp (ref "C6")
      (value "22pF")
      (fields
        (field (name "BOM_Manufacturer Part") "TCC0603COG220J500CT")
        (field (name "BOM_Supplier Part") "C376775")
      )
      (libsource (lib "") (part "TCC0603COG220J500CT_1"))
    )
    (comp (ref "C7")
      (value "100nF")
      (fields
        (field (name "BOM_Manufacturer Part") "CC0603JRX7R8BB104")
        (field (name "BOM_Supplier Part") "C327087")
      )
      (libsource (lib "") (part "CC0603JRX7R8BB104_2"))
    )
    (comp (ref "C22")
      (value "1uF")
      (fields
        (field (name "BOM_Manufacturer Part") "CL10A105KP8NNNC")
        (field (name "BOM_Supplier Part") "C26413")
      )
      (libsource (lib "") (part "CL10A105KP8NNNC_1"))
    )
    (comp (ref "C27")
      (value "100nF")
      (fields
        (field (name "BOM_Manufacturer Part") "CC0603JRX7R8BB104")
        (field (name "BOM_Supplier Part") "C327087")
      )
      (libsource (lib "") (part "CC0603JRX7R8BB104_1"))
    )
    (comp (ref "C28")
      (value "100nF")
      (fields
        (field (name "BOM_Manufacturer Part") "CC0603JRX7R8BB104")
        (field (name "BOM_Supplier Part") "C327087")
      )
      (libsource (lib "") (part "CC0603JRX7R8BB104_1"))
    )
    (comp (ref "C29")
      (value "100nF")
      (fields
        (field (name "BOM_Manufacturer Part") "CC0603JRX7R8BB104")
        (field (name "BOM_Supplier Part") "C327087")
      )
      (libsource (lib "") (part "CC0603JRX7R8BB104_1"))
    )
    (comp (ref "C30")
      (value "10uF")
      (fields
        (field (name "BOM_Manufacturer Part") "TCC1206X7R106K250HT")
        (field (name "BOM_Supplier Part") "C380364")
      )
      (libsource (lib "") (part "TCC1206X7R106K250HT"))
    )
    (comp (ref "C31")
      (value "470uF")
      (fields
        (field (name "BOM_Manufacturer Part") "HV471M016F105R")
        (field (name "BOM_Supplier Part") "C59924")
      )
      (libsource (lib "") (part "RT1E471M1010"))
    )
    (comp (ref "C34")
      (value "1uF")
      (fields
        (field (name "BOM_Manufacturer Part") "CL10A105KP8NNNC")
        (field (name "BOM_Supplier Part") "C26413")
      )
      (libsource (lib "") (part "CL10A105KP8NNNC"))
    )
    (comp (ref "C35")
      (value "1uF")
      (fields
        (field (name "BOM_Manufacturer Part") "CL10A105KP8NNNC")
        (field (name "BOM_Supplier Part") "C26413")
      )
      (libsource (lib "") (part "CL10A105KP8NNNC"))
    )
    (comp (ref "C55")
      (value "100nF")
      (fields
        (field (name "BOM_Manufacturer Part") "CC0603JRX7R8BB104")
        (field (name "BOM_Supplier Part") "C327087")
      )
      (libsource (lib "") (part "CC0603JRX7R8BB104_3"))
    )
    (comp (ref "C56")
      (value "1uF")
      (fields
        (field (name "BOM_Manufacturer Part") "CL10A105KP8NNNC")
        (field (name "BOM_Supplier Part") "C26413")
      )
      (libsource (lib "") (part "CL10A105KP8NNNC"))
    )
    (comp (ref "C57")
      (value "1nF")
      (fields
        (field (name "BOM_Manufacturer Part") "0603CG102F500NT")
        (field (name "BOM_Supplier Part") "C507408")
      )
      (libsource (lib "") (part "0603CG102F500NT"))
    )
    (comp (ref "CN17")
      (value "4x1 push_in connector")
      (fields
        (field (name "BOM_Manufacturer Part") "1825660000")
        (field (name "BOM_Supplier Part") "281-2044-ND")
      )
      (libsource (lib "") (part "4x1 push_in connector"))
    )
    (comp (ref "CN18")
      (value "4x1 push_in connector")
      (fields
        (field (name "BOM_Manufacturer Part") "1825660000")
        (field (name "BOM_Supplier Part") "281-2044-ND")
      )
      (libsource (lib "") (part "4x1 push_in connector"))
    )
    (comp (ref "F4")
      (value "BSMD0603-050-6V")
      (fields (field (name "BOM_Supplier Part") "C883095"))
      (libsource (lib "") (part "BSMD0603-050-6V"))
    )
    (comp (ref "F7")
      (value "BSMD0603-050-6V")
      (fields (field (name "BOM_Supplier Part") "C883095"))
      (libsource (lib "") (part "BSMD0603-050-6V_1"))
    )
    (comp (ref "FINP")
      (value "FC-DA1608HRK-620D")
      (fields (field (name "BOM_Supplier Part") "C84263"))
      (libsource (lib "") (part "FC-DA1608HRK-620D_1"))
    )
    (comp (ref "FSER")
      (value "FC-DA1608HRK-620D")
      (fields (field (name "BOM_Supplier Part") "C84263"))
      (libsource (lib "") (part "FC-DA1608HRK-620D"))
    )
    (comp (ref "H1")
      (value "A2541WV-3P_C609572")
      (fields
        (field (name "BOM_Manufacturer Part") "A2541WV-3P")
        (field (name "BOM_Supplier Part") "C609572")
      )
      (libsource (lib "") (part "A2541WV-3P_C609572"))
    )
    (comp (ref "INPUTS") (value "M12A 5pole female") (libsource (lib "") (part "M12A 5pole female")))
    (comp (ref "J7")
      (value "A2541WV-2P")
      (fields (field (name "BOM_Supplier Part") "C225477"))
      (libsource (lib "") (part "A2541WV-2P"))
    )
    (comp (ref "LED")
      (value "FC-DA1608HRK-620D")
      (fields (field (name "BOM_Supplier Part") "C84263"))
      (libsource (lib "") (part "FC-DA1608HRK-620D_2"))
    )
    (comp (ref "M1")
      (value "FC-D1608HYK-588J")
      (fields (field (name "BOM_Supplier Part") "C84268"))
      (libsource (lib "") (part "FC-D1608HYK-588J_3"))
    )
    (comp (ref "M2")
      (value "FC-D1608HOK-600H")
      (fields (field (name "BOM_Supplier Part") "C84269"))
      (libsource (lib "") (part "FC-D1608HOK-600H"))
    )
    (comp (ref "MOT")
      (value "FC-D1608WD-460H5")
      (fields (field (name "BOM_Supplier Part") "C84265"))
      (libsource (lib "") (part "FC-D1608WD-460H5"))
    )
    (comp (ref "P1")
      (value "HDR-IDC-2.54-2X5P")
      (fields
        (field (name "BOM_Manufacturer Part") "IDC Box 2.54mm 2X5P")
        (field (name "BOM_Supplier Part") "C5665")
      )
      (libsource (lib "") (part "HDR-IDC-2.54-2X5P"))
    )
    (comp (ref "Q1")
      (value "2N7002WT1G")
      (fields (field (name "BOM_Supplier Part") "C12778"))
      (libsource (lib "") (part "2N7002WT1G"))
    )
    (comp (ref "Q2")
      (value "BC856BW,115")
      (fields (field (name "BOM_Supplier Part") "C28063"))
      (libsource (lib "") (part "BC856BW,115"))
    )
    (comp (ref "Q3")
      (value "2N7002WT1G")
      (fields (field (name "BOM_Supplier Part") "C12778"))
      (libsource (lib "") (part "2N7002WT1G"))
    )
    (comp (ref "Q4")
      (value "2N7002WT1G")
      (fields (field (name "BOM_Supplier Part") "C12778"))
      (libsource (lib "") (part "2N7002WT1G"))
    )
    (comp (ref "Q5")
      (value "2N7002WT1G")
      (fields (field (name "BOM_Supplier Part") "C12778"))
      (libsource (lib "") (part "2N7002WT1G_1"))
    )
    (comp (ref "Q6")
      (value "ZXMS6004FFTA")
      (fields (field (name "BOM_Supplier Part") "C95063"))
      (libsource (lib "") (part "ZXMS6004FFTA"))
    )
    (comp (ref "Q11")
      (value "BC856BW,115")
      (fields (field (name "BOM_Supplier Part") "C28063"))
      (libsource (lib "") (part "BC856BW,115_1"))
    )
    (comp (ref "Q12")
      (value "BC856BW,115")
      (fields (field (name "BOM_Supplier Part") "C28063"))
      (libsource (lib "") (part "BC856BW,115"))
    )
    (comp (ref "R6")
      (value "1K")
      (fields
        (field (name "BOM_Manufacturer Part") "RTT03102JTP")
        (field (name "BOM_Supplier Part") "C103210")
      )
      (libsource (lib "") (part "RTT03103JTP"))
    )
    (comp (ref "R7")
      (value "1K")
      (fields
        (field (name "BOM_Manufacturer Part") "RTT03102JTP")
        (field (name "BOM_Supplier Part") "C103210")
      )
      (libsource (lib "") (part "RTT03103JTP_1"))
    )
    (comp (ref "R8")
      (value "10K")
      (fields
        (field (name "BOM_Manufacturer Part") "RTT03103JTP")
        (field (name "BOM_Supplier Part") "C103210")
      )
      (libsource (lib "") (part "RTT03103JTP_2"))
    )
    (comp (ref "R9")
      (value "1K")
      (fields
        (field (name "BOM_Manufacturer Part") "RTT03102JTP")
        (field (name "BOM_Supplier Part") "C103210")
      )
      (libsource (lib "") (part "RTT03103JTP_2"))
    )
    (comp (ref "R10")
      (value "1K")
      (fields
        (field (name "BOM_Manufacturer Part") "RTT03102JTP")
        (field (name "BOM_Supplier Part") "C103210")
      )
      (libsource (lib "") (part "RTT03103JTP"))
    )
    (comp (ref "R11")
      (value "1K")
      (fields
        (field (name "BOM_Manufacturer Part") "RTT03102JTP")
        (field (name "BOM_Supplier Part") "C103210")
      )
      (libsource (lib "") (part "RTT03103JTP_2"))
    )
    (comp (ref "R12")
      (value "1K")
      (fields
        (field (name "BOM_Manufacturer Part") "RTT03102JTP")
        (field (name "BOM_Supplier Part") "C103210")
      )
      (libsource (lib "") (part "RTT03103JTP_2"))
    )
    (comp (ref "R16")
      (value "10K")
      (fields
        (field (name "BOM_Manufacturer Part") "RTT03103JTP")
        (field (name "BOM_Supplier Part") "C103210")
      )
      (libsource (lib "") (part "RTT03103JTP_3"))
    )
    (comp (ref "R20")
      (value "1K")
      (fields
        (field (name "BOM_Manufacturer Part") "RTT03102JTP")
        (field (name "BOM_Supplier Part") "C103210")
      )
      (libsource (lib "") (part "RTT03103JTP_2"))
    )
    (comp (ref "R21")
      (value "1K")
      (fields
        (field (name "BOM_Manufacturer Part") "RTT03102JTP")
        (field (name "BOM_Supplier Part") "C103210")
      )
      (libsource (lib "") (part "RTT03103JTP_2"))
    )
    (comp (ref "R22")
      (value "1K")
      (fields
        (field (name "BOM_Manufacturer Part") "RTT03102JTP")
        (field (name "BOM_Supplier Part") "C103210")
      )
      (libsource (lib "") (part "RTT03103JTP"))
    )
    (comp (ref "R23")
      (value "1K")
      (fields
        (field (name "BOM_Manufacturer Part") "RTT03102JTP")
        (field (name "BOM_Supplier Part") "C103210")
      )
      (libsource (lib "") (part "RTT03103JTP"))
    )
    (comp (ref "R24")
      (value "2.7k")
      (fields (field (name "BOM_Manufacturer Part") "RTT03272JTP"))
      (libsource (lib "") (part "RTT03473JTP"))
    )
    (comp (ref "R25")
      (value "2k2")
      (fields
        (field (name "BOM_Manufacturer Part") "RTT03222JTP")
        (field (name "BOM_Supplier Part") "C103203")
      )
      (libsource (lib "") (part "RTT03100JTP"))
    )
    (comp (ref "R26")
      (value "2k2")
      (fields
        (field (name "BOM_Manufacturer Part") "RTT03222JTP")
        (field (name "BOM_Supplier Part") "C103203")
      )
      (libsource (lib "") (part "RTT03100JTP"))
    )
    (comp (ref "R27")
      (value "2k2")
      (fields
        (field (name "BOM_Manufacturer Part") "RTT03222JTP")
        (field (name "BOM_Supplier Part") "C103203")
      )
      (libsource (lib "") (part "RTT03100JTP"))
    )
    (comp (ref "R28")
      (value "8.2K")
      (fields
        (field (name "BOM_Manufacturer Part") "MElF-MFR02041/4WS130ΩFT50")
        (field (name "BOM_Supplier Part") "C265574")
      )
      (libsource (lib "") (part "MELF-MFR02041/4WS8.2KΩFT50_1"))
    )
    (comp (ref "R33")
      (value "10K")
      (fields
        (field (name "BOM_Manufacturer Part") "RTT03103JTP")
        (field (name "BOM_Supplier Part") "C103210")
      )
      (libsource (lib "") (part "RTT03103JTP_1"))
    )
    (comp (ref "R36")
      (value "560")
      (fields
        (field (name "BOM_Manufacturer Part") "RTT03561JTP")
        (field (name "BOM_Supplier Part") "C103717")
      )
      (libsource (lib "") (part "RTT03561JTP"))
    )
    (comp (ref "R40")
      (value "2k2")
      (fields
        (field (name "BOM_Manufacturer Part") "RTT03222JTP")
        (field (name "BOM_Supplier Part") "C103203")
      )
      (libsource (lib "") (part "RTT03100JTP"))
    )
    (comp (ref "R41")
      (value "2k2")
      (fields
        (field (name "BOM_Manufacturer Part") "RTT03222JTP")
        (field (name "BOM_Supplier Part") "C103203")
      )
      (libsource (lib "") (part "RTT03100JTP"))
    )
    (comp (ref "R42")
      (value "2k2")
      (fields
        (field (name "BOM_Manufacturer Part") "RTT03222JTP")
        (field (name "BOM_Supplier Part") "C103203")
      )
      (libsource (lib "") (part "RTT03100JTP"))
    )
    (comp (ref "R44")
      (value "560")
      (fields
        (field (name "BOM_Manufacturer Part") "RTT03561JTP")
        (field (name "BOM_Supplier Part") "C103717")
      )
      (libsource (lib "") (part "RTT03561JTP"))
    )
    (comp (ref "R45")
      (value "2k2")
      (fields
        (field (name "BOM_Manufacturer Part") "RTT03222JTP")
        (field (name "BOM_Supplier Part") "C103203")
      )
      (libsource (lib "") (part "RTT03100JTP"))
    )
    (comp (ref "R47")
      (value "560")
      (fields
        (field (name "BOM_Manufacturer Part") "RTT03561JTP")
        (field (name "BOM_Supplier Part") "C103717")
      )
      (libsource (lib "") (part "RTT03561JTP"))
    )
    (comp (ref "R48")
      (value "10K")
      (fields
        (field (name "BOM_Manufacturer Part") "RTT03103JTP")
        (field (name "BOM_Supplier Part") "C103210")
      )
      (libsource (lib "") (part "RTT03103JTP_3"))
    )
    (comp (ref "R49")
      (value "10K")
      (fields
        (field (name "BOM_Manufacturer Part") "RTT03103JTP")
        (field (name "BOM_Supplier Part") "C103210")
      )
      (libsource (lib "") (part "RTT03103JTP_2"))
    )
    (comp (ref "R51")
      (value "10K")
      (fields
        (field (name "BOM_Manufacturer Part") "RTT03103JTP")
        (field (name "BOM_Supplier Part") "C103210")
      )
      (libsource (lib "") (part "RTT03103JTP"))
    )
    (comp (ref "R53")
      (value "8.2K")
      (fields
        (field (name "BOM_Manufacturer Part") "MElF-MFR02041/4WS130ΩFT50")
        (field (name "BOM_Supplier Part") "C265574")
      )
      (libsource (lib "") (part "MELF-MFR02041/4WS8.2KΩFT50"))
    )
    (comp (ref "R54")
      (value "8.2K")
      (fields
        (field (name "BOM_Manufacturer Part") "MElF-MFR02041/4WS130ΩFT50")
        (field (name "BOM_Supplier Part") "C265574")
      )
      (libsource (lib "") (part "MELF-MFR02041/4WS8.2KΩFT50"))
    )
    (comp (ref "R55")
      (value "8.2K")
      (fields
        (field (name "BOM_Manufacturer Part") "MElF-MFR02041/4WS130ΩFT50")
        (field (name "BOM_Supplier Part") "C265574")
      )
      (libsource (lib "") (part "MELF-MFR02041/4WS8.2KΩFT50"))
    )
    (comp (ref "R59")
      (value "1K")
      (fields
        (field (name "BOM_Manufacturer Part") "RTT03102JTP")
        (field (name "BOM_Supplier Part") "C103210")
      )
      (libsource (lib "") (part "RTT03103JTP_1"))
    )
    (comp (ref "R61")
      (value "8.2K")
      (fields
        (field (name "BOM_Manufacturer Part") "MElF-MFR02041/4WS130ΩFT50")
        (field (name "BOM_Supplier Part") "C265574")
      )
      (libsource (lib "") (part "MELF-MFR02041/4WS8.2KΩFT50"))
    )
    (comp (ref "R62")
      (value "8.2K")
      (fields
        (field (name "BOM_Manufacturer Part") "MElF-MFR02041/4WS130ΩFT50")
        (field (name "BOM_Supplier Part") "C265574")
      )
      (libsource (lib "") (part "MELF-MFR02041/4WS8.2KΩFT50"))
    )
    (comp (ref "R63")
      (value "8.2K")
      (fields
        (field (name "BOM_Manufacturer Part") "MElF-MFR02041/4WS130ΩFT50")
        (field (name "BOM_Supplier Part") "C265574")
      )
      (libsource (lib "") (part "MELF-MFR02041/4WS8.2KΩFT50"))
    )
    (comp (ref "R73")
      (value "10K")
      (fields
        (field (name "BOM_Manufacturer Part") "RTT03103JTP")
        (field (name "BOM_Supplier Part") "C103210")
      )
      (libsource (lib "") (part "RTT03103JTP_1"))
    )
    (comp (ref "R76")
      (value "1K")
      (fields
        (field (name "BOM_Manufacturer Part") "RTT03102JTP")
        (field (name "BOM_Supplier Part") "C103210")
      )
      (libsource (lib "") (part "RTT03103JTP_1"))
    )
    (comp (ref "R77")
      (value "10K")
      (fields
        (field (name "BOM_Manufacturer Part") "RTT03103JTP")
        (field (name "BOM_Supplier Part") "C103210")
      )
      (libsource (lib "") (part "RTT03103JTP_3"))
    )
    (comp (ref "R94")
      (value "10K")
      (fields
        (field (name "BOM_Manufacturer Part") "RTT03103JTP")
        (field (name "BOM_Supplier Part") "C103210")
      )
      (libsource (lib "") (part "RTT03103JTP_3"))
    )
    (comp (ref "R95")
      (value "1K")
      (fields
        (field (name "BOM_Manufacturer Part") "RTT03102JTP")
        (field (name "BOM_Supplier Part") "C103210")
      )
      (libsource (lib "") (part "RTT03103JTP_1"))
    )
    (comp (ref "R96")
      (value "1K")
      (fields
        (field (name "BOM_Manufacturer Part") "RTT03102JTP")
        (field (name "BOM_Supplier Part") "C103210")
      )
      (libsource (lib "") (part "RTT03103JTP_1"))
    )
    (comp (ref "R104")
      (value "1K")
      (fields
        (field (name "BOM_Manufacturer Part") "RTT03102JTP")
        (field (name "BOM_Supplier Part") "C103210")
      )
      (libsource (lib "") (part "RTT03103JTP_1"))
    )
    (comp (ref "REMOTE")
      (value "FC-D1608HYK-588J")
      (fields (field (name "BOM_Supplier Part") "C84268"))
      (libsource (lib "") (part "FC-D1608HYK-588J_1"))
    )
    (comp (ref "RXD")
      (value "FC-D1608UGK-520D10")
      (fields (field (name "BOM_Supplier Part") "C84267"))
      (libsource (lib "") (part "FC-D1608UGK-520D10"))
    )
    (comp (ref "STEER")
      (value "FC-D1608HYK-588J")
      (fields (field (name "BOM_Supplier Part") "C84268"))
      (libsource (lib "") (part "FC-D1608HYK-588J"))
    )
    (comp (ref "STEERING") (value "M12A 5pole female") (libsource (lib "") (part "M12A 5pole female_1")))
    (comp (ref "TXD")
      (value "FC-DA1608BK-470H10")
      (fields (field (name "BOM_Supplier Part") "C84266"))
      (libsource (lib "") (part "FC-DA1608BK-470H10_1"))
    )
    (comp (ref "U1")
      (value "TG_WEMOS_D1_ESP32(CLONE)")
      (fields
        (field (name "BOM_Manufacturer Part") "New SchematicLib")
        (field (name "BOM_Supplier Part") "undefined")
      )
      (libsource (lib "") (part "TG_WEMOS_D1_ESP32(CLONE)"))
    )
    (comp (ref "U3")
      (value "CH340B")
      (fields (field (name "BOM_Supplier Part") "C81010"))
      (libsource (lib "") (part "CH340B"))
    )
    (comp (ref "U5")
      (value "ATMEGA328P-AU")
      (fields (field (name "BOM_Supplier Part") "C14877"))
      (libsource (lib "") (part "ATMEGA328P-AU"))
    )
    (comp (ref "U9")
      (value "BTN8982TAAUMA1")
      (fields (field (name "BOM_Supplier Part") "C74175"))
      (libsource (lib "") (part "BTN8982TAAUMA1"))
    )
    (comp (ref "U10")
      (value "BTN8982TAAUMA1")
      (fields (field (name "BOM_Supplier Part") "C74175"))
      (libsource (lib "") (part "BTN8982TAAUMA1_1"))
    )
    (comp (ref "U14")
      (value "BTS50301EJAXUMA1")
      (fields (field (name "BOM_Supplier Part") "C454924"))
      (libsource (lib "") (part "BTS50301EJAXUMA1"))
    )
    (comp (ref "WIFI")
      (value "FC-DA1608BK-470H10")
      (fields (field (name "BOM_Supplier Part") "C84266"))
      (libsource (lib "") (part "FC-DA1608BK-470H10"))
    )
    (comp (ref "WORK")
      (value "FC-D1608HYK-588J")
      (fields (field (name "BOM_Supplier Part") "C84268"))
      (libsource (lib "") (part "FC-D1608HYK-588J_2"))
    )
    (comp (ref "X1")
      (value "16MHz")
      (fields
        (field (name "BOM_Manufacturer Part") "X201616MPB4SC")
        (field (name "BOM_Supplier Part") "C108156")
      )
      (libsource (lib "") (part "TZ2315C"))
    )
    (comp (ref "BOOT")
      (value "A2541WV-2P")
      (fields (field (name "BOM_Supplier Part") "C225477"))
      (libsource (lib "") (part "A2541WV-2P"))
    )
    (comp (ref "C37")
      (value "33pF")
      (fields
        (field (name "BOM_Manufacturer Part") "CL10C330JB8NNNC")
        (field (name "BOM_Supplier Part") "C1663")
      )
      (libsource (lib "") (part "CC0603JRNPO9BN330"))
    )
    (comp (ref "C39")
      (value "33pF")
      (fields
        (field (name "BOM_Manufacturer Part") "CL10C330JB8NNNC")
        (field (name "BOM_Supplier Part") "C1663")
      )
      (libsource (lib "") (part "CC0603JRNPO9BN330_1"))
    )
    (comp (ref "C40")
      (value "1uF")
      (fields
        (field (name "BOM_Manufacturer Part") "CL10A105KP8NNNC")
        (field (name "BOM_Supplier Part") "C26413")
      )
      (libsource (lib "") (part "CL10A105KP8NNNC_1"))
    )
    (comp (ref "C41")
      (value "1uF")
      (fields
        (field (name "BOM_Manufacturer Part") "CL10A105KP8NNNC")
        (field (name "BOM_Supplier Part") "C26413")
      )
      (libsource (lib "") (part "CL10A105KP8NNNC"))
    )
    (comp (ref "C42")
      (value "1uF")
      (fields
        (field (name "BOM_Manufacturer Part") "CL10A105KP8NNNC")
        (field (name "BOM_Supplier Part") "C26413")
      )
      (libsource (lib "") (part "CL10A105KP8NNNC"))
    )
    (comp (ref "C43")
      (value "1uF")
      (fields
        (field (name "BOM_Manufacturer Part") "CL10A105KP8NNNC")
        (field (name "BOM_Supplier Part") "C26413")
      )
      (libsource (lib "") (part "CL10A105KP8NNNC"))
    )
    (comp (ref "C45")
      (value "100nF")
      (fields
        (field (name "BOM_Manufacturer Part") "CC0603JRX7R8BB104")
        (field (name "BOM_Supplier Part") "C327087")
      )
      (libsource (lib "") (part "CC0603JRX7R8BB104"))
    )
    (comp (ref "C46")
      (value "1uF")
      (fields
        (field (name "BOM_Manufacturer Part") "CL10A105KP8NNNC")
        (field (name "BOM_Supplier Part") "C26413")
      )
      (libsource (lib "") (part "CL10A105KP8NNNC"))
    )
    (comp (ref "C47")
      (value "1uF")
      (fields
        (field (name "BOM_Manufacturer Part") "CL10A105KP8NNNC")
        (field (name "BOM_Supplier Part") "C26413")
      )
      (libsource (lib "") (part "CL10A105KP8NNNC"))
    )
    (comp (ref "C49")
      (value "1uF")
      (fields
        (field (name "BOM_Manufacturer Part") "CL10A105KP8NNNC")
        (field (name "BOM_Supplier Part") "C26413")
      )
      (libsource (lib "") (part "CL10A105KP8NNNC"))
    )
    (comp (ref "C50")
      (value "1uF")
      (fields
        (field (name "BOM_Manufacturer Part") "CL10A105KP8NNNC")
        (field (name "BOM_Supplier Part") "C26413")
      )
      (libsource (lib "") (part "CL10A105KP8NNNC"))
    )
    (comp (ref "C51")
      (value "1uF")
      (fields
        (field (name "BOM_Manufacturer Part") "CL10A105KP8NNNC")
        (field (name "BOM_Supplier Part") "C26413")
      )
      (libsource (lib "") (part "CL10A105KP8NNNC"))
    )
    (comp (ref "C54")
      (value "1uF")
      (fields
        (field (name "BOM_Manufacturer Part") "CL10A105KP8NNNC")
        (field (name "BOM_Supplier Part") "C26413")
      )
      (libsource (lib "") (part "CL10A105KP8NNNC"))
    )
    (comp (ref "CN6")
      (value "1315-1206G0M075CP01")
      (fields (field (name "BOM_Supplier Part") "C721777"))
      (libsource (lib "") (part "1315-1206G0M075CP01"))
    )
    (comp (ref "D7")
      (value "CDSOT23-T24CAN")
      (fields (field (name "BOM_Supplier Part") "C252430"))
      (libsource (lib "") (part "CDSOT23-T24CAN"))
    )
    (comp (ref "LED1")
      (value "FC-D1608UGK-520D10")
      (fields (field (name "BOM_Supplier Part") "C84267"))
      (libsource (lib "") (part "FC-D1608UGK-520D10"))
    )
    (comp (ref "LED2")
      (value "FC-DA1608BK-470H10")
      (fields (field (name "BOM_Supplier Part") "C84266"))
      (libsource (lib "") (part "FC-DA1608BK-470H10_2"))
    )
    (comp (ref "LED3")
      (value "FC-D1608UGK-520D10")
      (fields (field (name "BOM_Supplier Part") "C84267"))
      (libsource (lib "") (part "FC-D1608UGK-520D10"))
    )
    (comp (ref "LED4")
      (value "FC-DA1608BK-470H10")
      (fields (field (name "BOM_Supplier Part") "C84266"))
      (libsource (lib "") (part "FC-DA1608BK-470H10"))
    )
    (comp (ref "R78")
      (value "10K")
      (fields
        (field (name "BOM_Manufacturer Part") "RTT03103JTP")
        (field (name "BOM_Supplier Part") "C103210")
      )
      (libsource (lib "") (part "RTT03103JTP"))
    )
    (comp (ref "R79")
      (value "10K")
      (fields
        (field (name "BOM_Manufacturer Part") "RTT03103JTP")
        (field (name "BOM_Supplier Part") "C103210")
      )
      (libsource (lib "") (part "RTT03103JTP"))
    )
    (comp (ref "R80")
      (value "10K")
      (fields
        (field (name "BOM_Manufacturer Part") "RTT03103JTP")
        (field (name "BOM_Supplier Part") "C103210")
      )
      (libsource (lib "") (part "RTT03103JTP_1"))
    )
    (comp (ref "R81")
      (value "2.7k")
      (fields (field (name "BOM_Manufacturer Part") "RTT03272JTP"))
      (libsource (lib "") (part "RTT03473JTP"))
    )
    (comp (ref "R82")
      (value "10K")
      (fields
        (field (name "BOM_Manufacturer Part") "RTT03103JTP")
        (field (name "BOM_Supplier Part") "C103210")
      )
      (libsource (lib "") (part "RTT03103JTP_1"))
    )
    (comp (ref "R83")
      (value "10")
      (fields
        (field (name "BOM_Manufacturer Part") "RTT03100JTP")
        (field (name "BOM_Supplier Part") "C103203")
      )
      (libsource (lib "") (part "RTT03100JTP"))
    )
    (comp (ref "R84")
      (value "1K")
      (fields
        (field (name "BOM_Manufacturer Part") "RTT03102JTP")
        (field (name "BOM_Supplier Part") "C103209")
      )
      (libsource (lib "") (part "RTT03102JTP"))
    )
    (comp (ref "R85")
      (value "1K")
      (fields
        (field (name "BOM_Manufacturer Part") "RTT03102JTP")
        (field (name "BOM_Supplier Part") "C103209")
      )
      (libsource (lib "") (part "RTT03102JTP"))
    )
    (comp (ref "R86")
      (value "1K")
      (fields
        (field (name "BOM_Manufacturer Part") "RTT03102JTP")
        (field (name "BOM_Supplier Part") "C103209")
      )
      (libsource (lib "") (part "RTT03102JTP"))
    )
    (comp (ref "R87")
      (value "1K")
      (fields
        (field (name "BOM_Manufacturer Part") "RTT03102JTP")
        (field (name "BOM_Supplier Part") "C103209")
      )
      (libsource (lib "") (part "RTT03102JTP"))
    )
    (comp (ref "R88")
      (value "1K")
      (fields
        (field (name "BOM_Manufacturer Part") "RTT03102JTP")
        (field (name "BOM_Supplier Part") "C103209")
      )
      (libsource (lib "") (part "RTT03102JTP_1"))
    )
    (comp (ref "R89")
      (value "1K")
      (fields
        (field (name "BOM_Manufacturer Part") "RTT03102JTP")
        (field (name "BOM_Supplier Part") "C103209")
      )
      (libsource (lib "") (part "RTT03102JTP_1"))
    )
    (comp (ref "RXCAN1")
      (value "FC-D1608UGK-520D10")
      (fields (field (name "BOM_Supplier Part") "C84267"))
      (libsource (lib "") (part "FC-D1608UGK-520D10_1"))
    )
    (comp (ref "TXCAN1")
      (value "FC-DA1608BK-470H10")
      (fields (field (name "BOM_Supplier Part") "C84266"))
      (libsource (lib "") (part "FC-DA1608BK-470H10_1"))
    )
    (comp (ref "U11")
      (value "LPC54616J512BD100")
      (fields (field (name "BOM_Supplier Part") "568-13457-ND"))
      (libsource (lib "") (part "LPC54616J512BD100"))
    )
    (comp (ref "U12")
      (value "TJA1051T/3/1J")
      (fields (field (name "BOM_Supplier Part") "C38695"))
      (libsource (lib "") (part "TJA1051T/3/1J"))
    )
    (comp (ref "X3")
      (value "12MHz")
      (fields
        (field (name "BOM_Manufacturer Part") "X322512MSB4SI")
        (field (name "BOM_Supplier Part") "C9002")
      )
      (libsource (lib "") (part "X322512MSB4SI"))
    )
    (comp (ref "ANT1")
      (value "FC-D1608UGK-520D10")
      (fields (field (name "BOM_Supplier Part") "C84267"))
      (libsource (lib "") (part "FC-D1608UGK-520D10"))
    )
    (comp (ref "ANT2")
      (value "FC-D1608UGK-520D10")
      (fields (field (name "BOM_Supplier Part") "C84267"))
      (libsource (lib "") (part "FC-D1608UGK-520D10"))
    )
    (comp (ref "ARDU1")
      (value "BM06B-GHS-TBT(LF)(SN)")
      (fields
        (field (name "BOM_Manufacturer Part") "SM06B-GHS-TB(LF)(SN)")
        (field (name "BOM_Supplier Part") "C133065")
      )
      (libsource (lib "") (part "SM06B-GHS-TB(LF)(SN)"))
    )
    (comp (ref "C8")
      (value "100nF")
      (fields
        (field (name "BOM_Manufacturer Part") "CC0603JRX7R8BB104")
        (field (name "BOM_Supplier Part") "C327087")
      )
      (libsource (lib "") (part "CC0603JRX7R8BB104_1"))
    )
    (comp (ref "C9")
      (value "100nF")
      (fields
        (field (name "BOM_Manufacturer Part") "CC0603JRX7R8BB104")
        (field (name "BOM_Supplier Part") "C327087")
      )
      (libsource (lib "") (part "CC0603JRX7R8BB104_1"))
    )
    (comp (ref "C14")
      (value "1uF")
      (fields
        (field (name "BOM_Manufacturer Part") "CL10A105KP8NNNC")
        (field (name "BOM_Supplier Part") "C26413")
      )
      (libsource (lib "") (part "CL10A105KP8NNNC"))
    )
    (comp (ref "C15")
      (value "1uF")
      (fields
        (field (name "BOM_Manufacturer Part") "CL10A105KP8NNNC")
        (field (name "BOM_Supplier Part") "C26413")
      )
      (libsource (lib "") (part "CL10A105KP8NNNC"))
    )
    (comp (ref "C24")
      (value "1nF")
      (fields
        (field (name "BOM_Manufacturer Part") "0603CG102F500NT")
        (field (name "BOM_Supplier Part") "C507408")
      )
      (libsource (lib "") (part "0603CG102F500NT"))
    )
    (comp (ref "C25")
      (value "1nF")
      (fields
        (field (name "BOM_Manufacturer Part") "0603CG102F500NT")
        (field (name "BOM_Supplier Part") "C507408")
      )
      (libsource (lib "") (part "0603CG102F500NT"))
    )
    (comp (ref "C33")
      (value "100nF")
      (fields
        (field (name "BOM_Manufacturer Part") "CC0603JRX7R8BB104")
        (field (name "BOM_Supplier Part") "C327087")
      )
      (libsource (lib "") (part "CC0603JRX7R8BB104_1"))
    )
    (comp (ref "C58")
      (value "100nF")
      (fields
        (field (name "BOM_Manufacturer Part") "CC0603JRX7R8BB104")
        (field (name "BOM_Supplier Part") "C327087")
      )
      (libsource (lib "") (part "CC0603JRX7R8BB104"))
    )
    (comp (ref "C59")
      (value "100nF")
      (fields
        (field (name "BOM_Manufacturer Part") "CC0603JRX7R8BB104")
        (field (name "BOM_Supplier Part") "C327087")
      )
      (libsource (lib "") (part "CC0603JRX7R8BB104_2"))
    )
    (comp (ref "C60")
      (value "22uF")
      (fields
        (field (name "BOM_Manufacturer Part") "CL21A226MAQNNNE")
        (field (name "BOM_Supplier Part") "C45783")
      )
      (libsource (lib "") (part "CL21A226MAQNNNE"))
    )
    (comp (ref "CHA")
      (value "FC-D1608HYK-588J")
      (fields (field (name "BOM_Supplier Part") "C84268"))
      (libsource (lib "") (part "FC-D1608HYK-588J"))
    )
    (comp (ref "CHB")
      (value "FC-D1608HOK-600H")
      (fields (field (name "BOM_Supplier Part") "C84269"))
      (libsource (lib "") (part "FC-D1608HOK-600H_1"))
    )
    (comp (ref "CN1")
      (value "4x1 push_in connector")
      (fields
        (field (name "BOM_Manufacturer Part") "1825660000")
        (field (name "BOM_Supplier Part") "281-2044-ND")
      )
      (libsource (lib "") (part "4x1 push_in connector"))
    )
    (comp (ref "CN5")
      (value "4x1 push_in connector")
      (fields
        (field (name "BOM_Manufacturer Part") "1825660000")
        (field (name "BOM_Supplier Part") "281-2044-ND")
      )
      (libsource (lib "") (part "4x1 push_in connector"))
    )
    (comp (ref "DIFF")
      (value "FC-D1608UGK-520D10")
      (fields (field (name "BOM_Supplier Part") "C84267"))
      (libsource (lib "") (part "FC-D1608UGK-520D10_1"))
    )
    (comp (ref "F5")
      (value "BSMD0603-050-6V")
      (fields (field (name "BOM_Supplier Part") "C883095"))
      (libsource (lib "") (part "BSMD0603-050-6V"))
    )
    (comp (ref "F6")
      (value "BSMD0603-050-6V")
      (fields (field (name "BOM_Supplier Part") "C883095"))
      (libsource (lib "") (part "BSMD0603-050-6V"))
    )
    (comp (ref "FROT")
      (value "FC-DA1608HRK-620D")
      (fields (field (name "BOM_Supplier Part") "C84263"))
      (libsource (lib "") (part "FC-DA1608HRK-620D"))
    )
    (comp (ref "FWAS")
      (value "FC-DA1608HRK-620D")
      (fields (field (name "BOM_Supplier Part") "C84263"))
      (libsource (lib "") (part "FC-DA1608HRK-620D_1"))
    )
    (comp (ref "J4")
      (value "A2541WV-2P")
      (fields (field (name "BOM_Supplier Part") "C225477"))
      (libsource (lib "") (part "A2541WV-2P"))
    )
    (comp (ref "OP1") (value "Option M8 4pole") (libsource (lib "") (part "JUMPER")))
    (comp (ref "P2") (value "Ardusimple RTK2B Board") (libsource (lib "") (part "Ardusimple RTK2B Board")))
    (comp (ref "Q9")
      (value "BC856BW,115")
      (fields (field (name "BOM_Supplier Part") "C28063"))
      (libsource (lib "") (part "BC856BW,115"))
    )
    (comp (ref "Q10")
      (value "BC856BW,115")
      (fields (field (name "BOM_Supplier Part") "C28063"))
      (libsource (lib "") (part "BC856BW,115"))
    )
    (comp (ref "QWIIC")
      (value "QWIIC SMD JST")
      (fields
        (field (name "BOM_Manufacturer Part") "SM04B-SRSS-TB(LF)(SN)")
        (field (name "BOM_Supplier Part") "C160404")
      )
      (libsource (lib "") (part "QWIIC SMD JST"))
    )
    (comp (ref "R5")
      (value "10K")
      (fields
        (field (name "BOM_Manufacturer Part") "RTT03103JTP")
        (field (name "BOM_Supplier Part") "C103210")
      )
      (libsource (lib "") (part "RTT03103JTP_2"))
    )
    (comp (ref "R13")
      (value "10K")
      (fields
        (field (name "BOM_Manufacturer Part") "RTT03103JTP")
        (field (name "BOM_Supplier Part") "C103210")
      )
      (libsource (lib "") (part "RTT03103JTP_2"))
    )
    (comp (ref "R29")
      (value "1K")
      (fields
        (field (name "BOM_Manufacturer Part") "RTT03102JTP")
        (field (name "BOM_Supplier Part") "C103209")
      )
      (libsource (lib "") (part "RTT03102JTP"))
    )
    (comp (ref "R30")
      (value "1K")
      (fields
        (field (name "BOM_Manufacturer Part") "RTT03102JTP")
        (field (name "BOM_Supplier Part") "C103209")
      )
      (libsource (lib "") (part "RTT03102JTP"))
    )
    (comp (ref "R31")
      (value "1K")
      (fields
        (field (name "BOM_Manufacturer Part") "RTT03102JTP")
        (field (name "BOM_Supplier Part") "C103210")
      )
      (libsource (lib "") (part "RTT03103JTP"))
    )
    (comp (ref "R32")
      (value "1K")
      (fields
        (field (name "BOM_Manufacturer Part") "RTT03102JTP")
        (field (name "BOM_Supplier Part") "C103210")
      )
      (libsource (lib "") (part "RTT03103JTP"))
    )
    (comp (ref "R52")
      (value "1K")
      (fields
        (field (name "BOM_Manufacturer Part") "RTT03102JTP")
        (field (name "BOM_Supplier Part") "C103210")
      )
      (libsource (lib "") (part "RTT03103JTP"))
    )
    (comp (ref "R56")
      (value "1K")
      (fields
        (field (name "BOM_Manufacturer Part") "RTT03102JTP")
        (field (name "BOM_Supplier Part") "C103210")
      )
      (libsource (lib "") (part "RTT03103JTP"))
    )
    (comp (ref "R57")
      (value "1K")
      (fields
        (field (name "BOM_Manufacturer Part") "RTT03102JTP")
        (field (name "BOM_Supplier Part") "C103210")
      )
      (libsource (lib "") (part "RTT03103JTP"))
    )
    (comp (ref "R58")
      (value "1K")
      (fields
        (field (name "BOM_Manufacturer Part") "RTT03102JTP")
        (field (name "BOM_Supplier Part") "C103210")
      )
      (libsource (lib "") (part "RTT03103JTP"))
    )
    (comp (ref "R74")
      (value "10K")
      (fields
        (field (name "BOM_Manufacturer Part") "RTT03103JTP")
        (field (name "BOM_Supplier Part") "C103210")
      )
      (libsource (lib "") (part "RTT03103JTP_1"))
    )
    (comp (ref "R75")
      (value "1K")
      (fields
        (field (name "BOM_Manufacturer Part") "RTT03102JTP")
        (field (name "BOM_Supplier Part") "C103210")
      )
      (libsource (lib "") (part "RTT03103JTP_1"))
    )
    (comp (ref "R90")
      (value "1K")
      (fields
        (field (name "BOM_Manufacturer Part") "RTT03102JTP")
        (field (name "BOM_Supplier Part") "C103210")
      )
      (libsource (lib "") (part "RTT03103JTP_1"))
    )
    (comp (ref "R91")
      (value "1K")
      (fields
        (field (name "BOM_Manufacturer Part") "RTT03102JTP")
        (field (name "BOM_Supplier Part") "C103210")
      )
      (libsource (lib "") (part "RTT03103JTP_1"))
    )
    (comp (ref "R92")
      (value "120")
      (fields
        (field (name "BOM_Manufacturer Part") "RTT06121JTP")
        (field (name "BOM_Supplier Part") "C104621")
      )
      (libsource (lib "") (part "RTT06121JTP"))
    )
    (comp (ref "R98")
      (value "1K")
      (fields
        (field (name "BOM_Manufacturer Part") "RTT03102JTP")
        (field (name "BOM_Supplier Part") "C103210")
      )
      (libsource (lib "") (part "RTT03103JTP"))
    )
    (comp (ref "ROTARY/485") (value "M8 4pole female") (libsource (lib "") (part "M8 4pole female")))
    (comp (ref "U15") (value "CMPS14") (libsource (lib "") (part "CMPS14")))
    (comp (ref "U16") (value "Female2X14_2mm") (libsource (lib "") (part "Female2X14_2mm")))
    (comp (ref "U17")
      (value "ADS1115IDGSR")
      (fields (field (name "BOM_Supplier Part") "C37593"))
      (libsource (lib "") (part "ADS1115IDGSR"))
    )
    (comp (ref "U18")
      (value "MMA8452QR1_C11360")
      (fields (field (name "BOM_Manufacturer Part") "MMA8452QR1") (field (name "BOM_Supplier Part") "C11360"))
      (libsource (lib "") (part "MMA8452QR1_C11360"))
    )
    (comp (ref "U19")
      (value "CH340B")
      (fields (field (name "BOM_Supplier Part") "C81010"))
      (libsource (lib "") (part "CH340B"))
    )
    (comp (ref "WAS1") (value "M8 3pole female") (libsource (lib "") (part "M8 3pole female")))
    (comp (ref "WAS2")
      (value "FC-D1608HYK-588J")
      (fields (field (name "BOM_Supplier Part") "C84268"))
      (libsource (lib "") (part "FC-D1608HYK-588J_1"))
    )
    (comp (ref "WAS3")
      (value "FC-D1608HOK-600H")
      (fields (field (name "BOM_Supplier Part") "C84269"))
      (libsource (lib "") (part "FC-D1608HOK-600H"))
    )
  )
  (nets
    (net (code "1") (name "+3V3") (class "Default")
      (node (ref "3V3") (pin "2") (pinfunction "+_2") (pintype "input"))
      (node (ref "C15") (pin "1") (pinfunction "1_1") (pintype "input"))
      (node (ref "C36") (pin "1") (pinfunction "1_1") (pintype "input"))
      (node (ref "C41") (pin "2") (pinfunction "2_2") (pintype "input"))
      (node (ref "C42") (pin "2") (pinfunction "2_2") (pintype "input"))
      (node (ref "C43") (pin "2") (pinfunction "2_2") (pintype "input"))
      (node (ref "C45") (pin "2") (pinfunction "2_2") (pintype "unspecified"))
      (node (ref "C46") (pin "2") (pinfunction "2_2") (pintype "input"))
      (node (ref "C47") (pin "2") (pinfunction "2_2") (pintype "input"))
      (node (ref "C48") (pin "2") (pinfunction "2_2") (pintype "unspecified"))
      (node (ref "C49") (pin "2") (pinfunction "2_2") (pintype "input"))
      (node (ref "C50") (pin "2") (pinfunction "2_2") (pintype "input"))
      (node (ref "C51") (pin "2") (pinfunction "2_2") (pintype "input"))
      (node (ref "C54") (pin "2") (pinfunction "2_2") (pintype "input"))
      (node (ref "C60") (pin "2") (pinfunction "2_2") (pintype "unspecified"))
      (node (ref "CN15") (pin "1") (pinfunction "1_1") (pintype "unspecified"))
      (node (ref "CN6") (pin "1") (pinfunction "1_1") (pintype "unspecified"))
      (node (ref "L2") (pin "2") (pinfunction "2_2") (pintype "input"))
      (node (ref "P1") (pin "9") (pinfunction "9_9") (pintype "unspecified"))
      (node (ref "QWIIC") (pin "2") (pinfunction "3.3V_2") (pintype "unspecified"))
      (node (ref "R29") (pin "2") (pinfunction "2_2") (pintype "input"))
      (node (ref "R30") (pin "2") (pinfunction "2_2") (pintype "input"))
      (node (ref "R37") (pin "2") (pinfunction "2_2") (pintype "input"))
      (node (ref "R78") (pin "1") (pinfunction "1_1") (pintype "input"))
      (node (ref "R79") (pin "1") (pinfunction "1_1") (pintype "input"))
      (node (ref "R94") (pin "1") (pinfunction "1_1") (pintype "input"))
      (node (ref "RX485") (pin "2") (pinfunction "A_2") (pintype "input"))
      (node (ref "RXCAN") (pin "2") (pinfunction "A_2") (pintype "input"))
      (node (ref "RXCAN1") (pin "2") (pinfunction "A_2") (pintype "input"))
      (node (ref "TX485") (pin "2") (pinfunction "+_2") (pintype "input"))
      (node (ref "TXCAN") (pin "2") (pinfunction "+_2") (pintype "input"))
      (node (ref "TXCAN1") (pin "2") (pinfunction "+_2") (pintype "input"))
      (node (ref "U1") (pin "30") (pinfunction "3.3V_30") (pintype "unspecified"))
      (node (ref "U11") (pin "1") (pinfunction "VDD_1") (pintype "passive"))
      (node (ref "U11") (pin "10") (pinfunction "USB1_AVDDC3V3_10") (pintype "passive"))
      (node (ref "U11") (pin "11") (pinfunction "USB1_AVDDTX3V3_11") (pintype "passive"))
      (node (ref "U11") (pin "21") (pinfunction "VDD_21") (pintype "passive"))
      (node (ref "U11") (pin "31") (pinfunction "VREFP_31") (pintype "unspecified"))
      (node (ref "U11") (pin "32") (pinfunction "VDDA_32") (pintype "passive"))
      (node (ref "U11") (pin "33") (pinfunction "VDD_33") (pintype "passive"))
      (node (ref "U11") (pin "45") (pinfunction "VBAT_45") (pintype "bidirectional"))
      (node (ref "U11") (pin "50") (pinfunction "VDD_50") (pintype "passive"))
      (node (ref "U11") (pin "54") (pinfunction "VDD_54") (pintype "passive"))
      (node (ref "U11") (pin "75") (pinfunction "VDD_75") (pintype "passive"))
      (node (ref "U11") (pin "76") (pinfunction "VDD_76") (pintype "passive"))
      (node (ref "U11") (pin "99") (pinfunction "VDD_99") (pintype "passive"))
      (node (ref "U12") (pin "5") (pinfunction "VIO_5") (pintype "unspecified"))
      (node (ref "U16") (pin "6") (pinfunction "VCC_3V3_6") (pintype "unspecified"))
      (node (ref "U18") (pin "1") (pinfunction "VDDIO_1") (pintype "unspecified"))
      (node (ref "U18") (pin "14") (pinfunction "VDD_14") (pintype "unspecified"))
      (node (ref "U7") (pin "5") (pinfunction "VIO_5") (pintype "unspecified"))
      (node (ref "U8") (pin "8") (pinfunction "VCC_8") (pintype "unspecified"))
    )
    (net (code "2") (name "+5V") (class "Default")
      (node (ref "5V") (pin "2") (pinfunction "+_2") (pintype "input"))
      (node (ref "ARDU1") (pin "1") (pinfunction "1_1") (pintype "unspecified"))
      (node (ref "C14") (pin "1") (pinfunction "1_1") (pintype "input"))
      (node (ref "C2") (pin "1") (pinfunction "1_1") (pintype "input"))
      (node (ref "C21") (pin "2") (pinfunction "2_2") (pintype "unspecified"))
      (node (ref "C22") (pin "1") (pinfunction "1_1") (pintype "input"))
      (node (ref "C26") (pin "1") (pinfunction "1_1") (pintype "input"))
      (node (ref "C34") (pin "1") (pinfunction "1_1") (pintype "input"))
      (node (ref "C35") (pin "1") (pinfunction "1_1") (pintype "input"))
      (node (ref "C4") (pin "1") (pinfunction "1_1") (pintype "unspecified"))
      (node (ref "C40") (pin "1") (pinfunction "1_1") (pintype "input"))
      (node (ref "C53") (pin "2") (pinfunction "2_2") (pintype "unspecified"))
      (node (ref "C56") (pin "1") (pinfunction "1_1") (pintype "input"))
      (node (ref "C59") (pin "1") (pinfunction "1_1") (pintype "unspecified"))
      (node (ref "CHA") (pin "2") (pinfunction "A_2") (pintype "input"))
      (node (ref "CHB") (pin "2") (pinfunction "A_2") (pintype "input"))
      (node (ref "CN7") (pin "1") (pinfunction "1_1") (pintype "unspecified"))
      (node (ref "F1") (pin "2") (pinfunction "2_2") (pintype "unspecified"))
      (node (ref "F5") (pin "1") (pinfunction "1_1") (pintype "unspecified"))
      (node (ref "F6") (pin "1") (pinfunction "1_1") (pintype "unspecified"))
      (node (ref "F7") (pin "1") (pinfunction "1_1") (pintype "unspecified"))
      (node (ref "FGNSS") (pin "1") (pinfunction "A_1") (pintype "input"))
      (node (ref "FROT") (pin "1") (pinfunction "A_1") (pintype "input"))
      (node (ref "FSER") (pin "1") (pinfunction "A_1") (pintype "input"))
      (node (ref "FWAS") (pin "1") (pinfunction "A_1") (pintype "input"))
      (node (ref "H1") (pin "1") (pinfunction "1_1") (pintype "unspecified"))
      (node (ref "J1") (pin "2") (pinfunction "2_2") (pintype "unspecified"))
      (node (ref "J2") (pin "2") (pinfunction "2_2") (pintype "unspecified"))
      (node (ref "J3") (pin "2") (pinfunction "2_2") (pintype "unspecified"))
      (node (ref "L8") (pin "2") (pinfunction "2_2") (pintype "input"))
      (node (ref "R104") (pin "1") (pinfunction "1_1") (pintype "input"))
      (node (ref "R22") (pin "2") (pinfunction "2_2") (pintype "input"))
      (node (ref "R23") (pin "2") (pinfunction "2_2") (pintype "input"))
      (node (ref "R48") (pin "1") (pinfunction "1_1") (pintype "input"))
      (node (ref "R6") (pin "2") (pinfunction "2_2") (pintype "input"))
      (node (ref "U1") (pin "31") (pinfunction "VCC_31") (pintype "unspecified"))
      (node (ref "U11") (pin "9") (pinfunction "USB1_VBUS_9") (pintype "unspecified"))
      (node (ref "U12") (pin "3") (pinfunction "VCC_3") (pintype "unspecified"))
      (node (ref "U13") (pin "3") (pinfunction "Vin_3") (pintype "unspecified"))
      (node (ref "U13") (pin "5") (pinfunction "EN_5") (pintype "unspecified"))
      (node (ref "U15") (pin "1") (pinfunction "3.3v-5v_1") (pintype "passive"))
      (node (ref "U17") (pin "8") (pinfunction "VDD_8") (pintype "unspecified"))
      (node (ref "U19") (pin "16") (pinfunction "VCC_16") (pintype "unspecified"))
      (node (ref "U2") (pin "20") (pinfunction "VDD5_20") (pintype "unspecified"))
      (node (ref "U3") (pin "16") (pinfunction "VCC_16") (pintype "unspecified"))
      (node (ref "U5") (pin "18") (pinfunction "AVCC_18") (pintype "unspecified"))
      (node (ref "U5") (pin "4") (pinfunction "VCC_4") (pintype "unspecified"))
      (node (ref "U5") (pin "6") (pinfunction "VCC_6") (pintype "unspecified"))
      (node (ref "U6") (pin "16") (pinfunction "VCC_16") (pintype "unspecified"))
      (node (ref "U7") (pin "3") (pinfunction "VCC_3") (pintype "unspecified"))
      (node (ref "USB1") (pin "1") (pinfunction "VCC_1") (pintype "input"))
      (node (ref "USB_AUX") (pin "1") (pinfunction "VCC_1") (pintype "unspecified"))
      (node (ref "USB_AUX") (pin "5") (pinfunction "VCC_5") (pintype "unspecified"))
      (node (ref "WAS2") (pin "2") (pinfunction "A_2") (pintype "input"))
      (node (ref "WAS3") (pin "2") (pinfunction "A_2") (pintype "input"))
      (node (ref "WIFI") (pin "2") (pinfunction "+_2") (pintype "input"))
    )
    (net (code "3") (name "+Batt") (class "Default")
      (node (ref "CN4") (pin "2") (pinfunction "2_2") (pintype "unspecified"))
      (node (ref "D2") (pin "2") (pinfunction "A_2") (pintype "unspecified"))
      (node (ref "D3") (pin "1") (pinfunction "A_1") (pintype "unspecified"))
      (node (ref "F4") (pin "1") (pinfunction "1_1") (pintype "unspecified"))
      (node (ref "FINP") (pin "1") (pinfunction "A_1") (pintype "input"))
      (node (ref "POWER") (pin "1") (pinfunction "+_1") (pintype "unspecified"))
    )
    (net (code "4") (name "+Motor") (class "Default")
      (node (ref "C30") (pin "2") (pinfunction "2_2") (pintype "unspecified"))
      (node (ref "C31") (pin "1") (pinfunction "1_1") (pintype "unspecified"))
      (node (ref "CN4") (pin "1") (pinfunction "1_1") (pintype "unspecified"))
      (node (ref "D1") (pin "2") (pinfunction "A_2") (pintype "unspecified"))
      (node (ref "MOT") (pin "2") (pinfunction "+_2") (pintype "input"))
      (node (ref "POWER") (pin "4") (pinfunction "4_4") (pintype "unspecified"))
      (node (ref "Q2") (pin "2") (pinfunction "2_2") (pintype "input"))
      (node (ref "R35") (pin "1") (pinfunction "1_1") (pintype "input"))
      (node (ref "R51") (pin "2") (pinfunction "2_2") (pintype "input"))
      (node (ref "R53") (pin "2") (pinfunction "2_2") (pintype "unspecified"))
      (node (ref "U10") (pin "7") (pinfunction "VS_7") (pintype "unspecified"))
      (node (ref "U14") (pin "9") (pinfunction "EP_9") (pintype "unspecified"))
      (node (ref "U9") (pin "7") (pinfunction "VS_7") (pintype "unspecified"))
    )
    (net (code "5") (name "+SMPS") (class "Default")
      (node (ref "C20") (pin "2") (pinfunction "2_2") (pintype "unspecified"))
      (node (ref "C61") (pin "2") (pinfunction "2_2") (pintype "input"))
      (node (ref "L7") (pin "2") (pinfunction "2_2") (pintype "unspecified"))
      (node (ref "L8") (pin "1") (pinfunction "1_1") (pintype "input"))
      (node (ref "R17") (pin "2") (pinfunction "2_2") (pintype "input"))
    )
    (net (code "6") (name "+Vin") (class "Default")
      (node (ref "C17") (pin "2") (pinfunction "2_2") (pintype "unspecified"))
      (node (ref "C18") (pin "2") (pinfunction "2_2") (pintype "unspecified"))
      (node (ref "C19") (pin "2") (pinfunction "2_2") (pintype "unspecified"))
      (node (ref "C32") (pin "1") (pinfunction "1_1") (pintype "unspecified"))
      (node (ref "D3") (pin "2") (pinfunction "K_2") (pintype "unspecified"))
      (node (ref "J8") (pin "4") (pinfunction "4_4") (pintype "unspecified"))
      (node (ref "U4") (pin "3") (pinfunction "Vin_3") (pintype "unspecified"))
    )
    (net (code "7") (name "-Min") (class "Default")
      (node (ref "CN4") (pin "4") (pinfunction "4_4") (pintype "unspecified"))
      (node (ref "D1") (pin "1") (pinfunction "K_1") (pintype "unspecified"))
      (node (ref "POWER") (pin "2") (pinfunction "2_2") (pintype "unspecified"))
      (node (ref "Q8") (pin "5") (pinfunction "D_5") (pintype "unspecified"))
      (node (ref "Q8") (pin "6") (pinfunction "D_6") (pintype "unspecified"))
      (node (ref "Q8") (pin "7") (pinfunction "D_7") (pintype "unspecified"))
      (node (ref "Q8") (pin "8") (pinfunction "D_8") (pintype "unspecified"))
    )
    (net (code "8") (name "-Motor") (class "Default")
      (node (ref "C30") (pin "1") (pinfunction "1_1") (pintype "unspecified"))
      (node (ref "C31") (pin "2") (pinfunction "2_2") (pintype "unspecified"))
      (node (ref "Q8") (pin "1") (pinfunction "S_1") (pintype "unspecified"))
      (node (ref "Q8") (pin "2") (pinfunction "S_2") (pintype "unspecified"))
      (node (ref "Q8") (pin "3") (pinfunction "S_3") (pintype "unspecified"))
      (node (ref "R11") (pin "1") (pinfunction "1_1") (pintype "input"))
      (node (ref "R12") (pin "1") (pinfunction "1_1") (pintype "input"))
      (node (ref "R20") (pin "2") (pinfunction "2_2") (pintype "input"))
      (node (ref "R21") (pin "2") (pinfunction "2_2") (pintype "input"))
      (node (ref "R39") (pin "1") (pinfunction "1_1") (pintype "input"))
      (node (ref "R49") (pin "1") (pinfunction "1_1") (pintype "input"))
      (node (ref "R54") (pin "2") (pinfunction "2_2") (pintype "unspecified"))
      (node (ref "U10") (pin "1") (pinfunction "GND_1") (pintype "unspecified"))
      (node (ref "U14") (pin "1") (pinfunction "GND_1") (pintype "unspecified"))
      (node (ref "U9") (pin "1") (pinfunction "GND_1") (pintype "unspecified"))
    )
    (net (code "9") (name ".6V") (class "Default")
      (node (ref "C61") (pin "1") (pinfunction "1_1") (pintype "input"))
      (node (ref "R17") (pin "1") (pinfunction "1_1") (pintype "input"))
      (node (ref "R18") (pin "2") (pinfunction "2_2") (pintype "input"))
      (node (ref "U4") (pin "4") (pinfunction "FB_4") (pintype "unspecified"))
    )
    (net (code "10") (name "1V8Hub") (class "Default")
      (node (ref "C12") (pin "2") (pinfunction "2_2") (pintype "input"))
      (node (ref "U2") (pin "12") (pinfunction "VD18_O_12") (pintype "unspecified"))
      (node (ref "U2") (pin "28") (pinfunction "VD18_28") (pintype "unspecified"))
    )
    (net (code "11") (name "3V3Hub") (class "Default")
      (node (ref "C10") (pin "2") (pinfunction "2_2") (pintype "input"))
      (node (ref "Q7") (pin "1") (pinfunction "1_1") (pintype "input"))
      (node (ref "R2") (pin "2") (pinfunction "2_2") (pintype "input"))
      (node (ref "R34") (pin "2") (pinfunction "2_2") (pintype "input"))
      (node (ref "U2") (pin "13") (pinfunction "VD33_13") (pintype "unspecified"))
      (node (ref "U2") (pin "19") (pinfunction "BUSJ_19") (pintype "unspecified"))
      (node (ref "U2") (pin "21") (pinfunction "VD33_O_21") (pintype "unspecified"))
      (node (ref "U2") (pin "26") (pinfunction "OVCJ_26") (pintype "unspecified"))
    )
    (net (code "12") (name "A") (class "Default")
      (node (ref "CN1") (pin "4") (pinfunction "4_4") (pintype "unspecified"))
      (node (ref "D6") (pin "1") (pinfunction "1_1") (pintype "unspecified"))
      (node (ref "J4") (pin "1") (pinfunction "1_1") (pintype "unspecified"))
      (node (ref "R32") (pin "1") (pinfunction "1_1") (pintype "input"))
      (node (ref "R37") (pin "1") (pinfunction "1_1") (pintype "input"))
      (node (ref "R90") (pin "1") (pinfunction "1_1") (pintype "input"))
      (node (ref "ROTARY/485") (pin "4") (pinfunction "4_4") (pintype "unspecified"))
      (node (ref "U8") (pin "6") (pinfunction "A_6") (pintype "unspecified"))
    )
    (net (code "13") (name "A0{slash}WAS") (class "Default")
      (node (ref "C9") (pin "2") (pinfunction "2_2") (pintype "unspecified"))
      (node (ref "R13") (pin "1") (pinfunction "1_1") (pintype "input"))
      (node (ref "U1") (pin "6") (pinfunction "SVP_6") (pintype "unspecified"))
      (node (ref "U17") (pin "4") (pinfunction "AIN0_4") (pintype "unspecified"))
      (node (ref "U5") (pin "23") (pinfunction "PC0(ADC0/PCINT8)_23") (pintype "unspecified"))
    )
    (net (code "14") (name "A1{slash}Ch_B") (class "Default")
      (node (ref "R91") (pin "2") (pinfunction "2_2") (pintype "input"))
      (node (ref "U1") (pin "24") (pinfunction "IO4_24") (pintype "unspecified"))
      (node (ref "U5") (pin "24") (pinfunction "PC1(ADC1/PCINT9)_24") (pintype "unspecified"))
    )
    (net (code "15") (name "A2{slash}SafeSense") (class "Default")
      (node (ref "R25") (pin "1") (pinfunction "1_1") (pintype "input"))
      (node (ref "R48") (pin "2") (pinfunction "2_2") (pintype "input"))
      (node (ref "R53") (pin "1") (pinfunction "1_1") (pintype "unspecified"))
      (node (ref "R54") (pin "1") (pinfunction "1_1") (pintype "unspecified"))
      (node (ref "U5") (pin "25") (pinfunction "PC2(ADC2/PCINT10)_25") (pintype "unspecified"))
    )
    (net (code "16") (name "A3{slash}Out") (class "Default")
      (node (ref "R33") (pin "2") (pinfunction "2_2") (pintype "input"))
      (node (ref "R77") (pin "1") (pinfunction "1_1") (pintype "input"))
      (node (ref "U5") (pin "26") (pinfunction "PC3(ADC3/PCINT11)_26") (pintype "unspecified"))
    )
    (net (code "17") (name "A4{slash}SDA") (class "Default")
      (node (ref "ARDU1") (pin "5") (pinfunction "5_5") (pintype "unspecified"))
      (node (ref "J9") (pin "5") (pinfunction "5_5") (pintype "unspecified"))
      (node (ref "QWIIC") (pin "3") (pinfunction "SDA_3") (pintype "unspecified"))
      (node (ref "R30") (pin "1") (pinfunction "1_1") (pintype "input"))
      (node (ref "U1") (pin "15") (pinfunction "IO21_15") (pintype "unspecified"))
      (node (ref "U15") (pin "2") (pinfunction "SDA/TX_2") (pintype "bidirectional"))
      (node (ref "U17") (pin "9") (pinfunction "SDA_9") (pintype "unspecified"))
      (node (ref "U18") (pin "6") (pinfunction "SDA_6") (pintype "unspecified"))
      (node (ref "U5") (pin "27") (pinfunction "PC4(ADC4/SDA/PCINT12)_27") (pintype "unspecified"))
    )
    (net (code "18") (name "A5{slash}SCL") (class "Default")
      (node (ref "ARDU1") (pin "4") (pinfunction "4_4") (pintype "unspecified"))
      (node (ref "J9") (pin "6") (pinfunction "6_6") (pintype "unspecified"))
      (node (ref "QWIIC") (pin "4") (pinfunction "SCL_4") (pintype "unspecified"))
      (node (ref "R29") (pin "1") (pinfunction "1_1") (pintype "input"))
      (node (ref "U1") (pin "11") (pinfunction "IO22_11") (pintype "unspecified"))
      (node (ref "U15") (pin "3") (pinfunction "SCL/RX_3") (pintype "bidirectional"))
      (node (ref "U17") (pin "10") (pinfunction "SCL_10") (pintype "unspecified"))
      (node (ref "U18") (pin "4") (pinfunction "SCL_4") (pintype "unspecified"))
      (node (ref "U5") (pin "28") (pinfunction "PC5(ADC5/SCL/PCINT13)_28") (pintype "unspecified"))
    )
    (net (code "19") (name "A7{slash}CurrSen") (class "Default")
      (node (ref "C57") (pin "2") (pinfunction "2_2") (pintype "input"))
      (node (ref "R28") (pin "1") (pinfunction "1_1") (pintype "unspecified"))
      (node (ref "U1") (pin "13") (pinfunction "IO35_13") (pintype "unspecified"))
      (node (ref "U5") (pin "22") (pinfunction "ADC7_22") (pintype "unspecified"))
    )
    (net (code "20") (name "Aux") (class "Default")
      (node (ref "J8") (pin "2") (pinfunction "2_2") (pintype "unspecified"))
      (node (ref "POWER") (pin "5") (pinfunction "5_5") (pintype "unspecified"))
    )
    (net (code "21") (name "A{slash}RtSw") (class "Default")
      (node (ref "C24") (pin "2") (pinfunction "2_2") (pintype "input"))
      (node (ref "C27") (pin "2") (pinfunction "2_2") (pintype "unspecified"))
      (node (ref "Q4") (pin "1") (pinfunction "G_1") (pintype "unspecified"))
      (node (ref "R36") (pin "2") (pinfunction "2_2") (pintype "input"))
      (node (ref "R40") (pin "2") (pinfunction "2_2") (pintype "input"))
      (node (ref "U17") (pin "6") (pinfunction "AIN2_6") (pintype "unspecified"))
    )
    (net (code "22") (name "A{slash}WkSw") (class "Default")
      (node (ref "C25") (pin "2") (pinfunction "2_2") (pintype "input"))
      (node (ref "C29") (pin "2") (pinfunction "2_2") (pintype "unspecified"))
      (node (ref "Q3") (pin "1") (pinfunction "G_1") (pintype "unspecified"))
      (node (ref "R45") (pin "2") (pinfunction "2_2") (pintype "input"))
      (node (ref "R47") (pin "2") (pinfunction "2_2") (pintype "input"))
      (node (ref "U1") (pin "17") (pinfunction "IO33_17") (pintype "unspecified"))
      (node (ref "U17") (pin "7") (pinfunction "AIN3_7") (pintype "unspecified"))
    )
    (net (code "23") (name "B") (class "Default")
      (node (ref "CN1") (pin "2") (pinfunction "2_2") (pintype "unspecified"))
      (node (ref "D6") (pin "2") (pinfunction "2_2") (pintype "unspecified"))
      (node (ref "R31") (pin "1") (pinfunction "1_1") (pintype "input"))
      (node (ref "R38") (pin "1") (pinfunction "1_1") (pintype "input"))
      (node (ref "R91") (pin "1") (pinfunction "1_1") (pintype "input"))
      (node (ref "R92") (pin "2") (pinfunction "2_2") (pintype "input"))
      (node (ref "ROTARY/485") (pin "2") (pinfunction "2_2") (pintype "unspecified"))
      (node (ref "U8") (pin "7") (pinfunction "B_7") (pintype "unspecified"))
    )
    (net (code "24") (name "CAN+") (class "Default")
      (node (ref "CAN") (pin "1") (pinfunction "+_1") (pintype "unspecified"))
      (node (ref "CN11") (pin "1") (pinfunction "1_1") (pintype "unspecified"))
      (node (ref "F2") (pin "2") (pinfunction "2_2") (pintype "unspecified"))
      (node (ref "R71") (pin "2") (pinfunction "2_2") (pintype "input"))
    )
    (net (code "25") (name "CANB+") (class "Default")
      (node (ref "CANB") (pin "1") (pinfunction "+_1") (pintype "unspecified"))
      (node (ref "CN12") (pin "1") (pinfunction "1_1") (pintype "unspecified"))
      (node (ref "F3") (pin "2") (pinfunction "2_2") (pintype "unspecified"))
      (node (ref "R72") (pin "2") (pinfunction "2_2") (pintype "input"))
    )
    (net (code "26") (name "CANH") (class "Default")
      (node (ref "CAN") (pin "4") (pinfunction "4_4") (pintype "unspecified"))
      (node (ref "CN11") (pin "4") (pinfunction "4_4") (pintype "unspecified"))
      (node (ref "D5") (pin "2") (pinfunction "2_2") (pintype "unspecified"))
      (node (ref "R60") (pin "1") (pinfunction "1_1") (pintype "input"))
      (node (ref "U7") (pin "7") (pinfunction "CANH_7") (pintype "unspecified"))
    )
    (net (code "27") (name "CANH1") (class "Default")
      (node (ref "CANB") (pin "4") (pinfunction "4_4") (pintype "unspecified"))
      (node (ref "CN12") (pin "4") (pinfunction "4_4") (pintype "unspecified"))
      (node (ref "D7") (pin "1") (pinfunction "1_1") (pintype "unspecified"))
      (node (ref "R65") (pin "1") (pinfunction "1_1") (pintype "input"))
      (node (ref "U12") (pin "7") (pinfunction "CANH_7") (pintype "unspecified"))
    )
    (net (code "28") (name "CANL") (class "Default")
      (node (ref "CAN") (pin "2") (pinfunction "2_2") (pintype "unspecified"))
      (node (ref "CN11") (pin "2") (pinfunction "2_2") (pintype "unspecified"))
      (node (ref "D5") (pin "1") (pinfunction "1_1") (pintype "unspecified"))
      (node (ref "J2") (pin "3") (pinfunction "3_3") (pintype "unspecified"))
      (node (ref "U7") (pin "6") (pinfunction "CANL_6") (pintype "unspecified"))
    )
    (net (code "29") (name "CANL1") (class "Default")
      (node (ref "CANB") (pin "2") (pinfunction "2_2") (pintype "unspecified"))
      (node (ref "CN12") (pin "2") (pinfunction "2_2") (pintype "unspecified"))
      (node (ref "D7") (pin "2") (pinfunction "2_2") (pintype "unspecified"))
      (node (ref "J3") (pin "3") (pinfunction "3_3") (pintype "unspecified"))
      (node (ref "U12") (pin "6") (pinfunction "CANL_6") (pintype "unspecified"))
    )
    (net (code "30") (name "CC11") (class "Default")
      (node (ref "CN8") (pin "1") (pinfunction "1_1") (pintype "unspecified"))
      (node (ref "TO_PC") (pin "A5") (pinfunction "CC1_A5") (pintype "unspecified"))
    )
    (net (code "31") (name "CC12") (class "Default")
      (node (ref "CN10") (pin "1") (pinfunction "1_1") (pintype "unspecified"))
      (node (ref "CN9") (pin "1") (pinfunction "1_1") (pintype "unspecified"))
      (node (ref "DC/AUX") (pin "A5") (pinfunction "CC1_A5") (pintype "unspecified"))
    )
    (net (code "32") (name "CC21") (class "Default")
      (node (ref "CN8") (pin "2") (pinfunction "2_2") (pintype "unspecified"))
      (node (ref "TO_PC") (pin "B5") (pinfunction "CC2_B5") (pintype "unspecified"))
    )
    (net (code "33") (name "CC22") (class "Default")
      (node (ref "CN10") (pin "2") (pinfunction "2_2") (pintype "unspecified"))
      (node (ref "CN9") (pin "2") (pinfunction "2_2") (pintype "unspecified"))
      (node (ref "DC/AUX") (pin "B5") (pinfunction "CC2_B5") (pintype "unspecified"))
    )
    (net (code "34") (name "CurrentSense") (class "Default")
      (node (ref "R12") (pin "2") (pinfunction "2_2") (pintype "input"))
      (node (ref "R20") (pin "1") (pinfunction "1_1") (pintype "input"))
      (node (ref "R28") (pin "2") (pinfunction "2_2") (pintype "unspecified"))
      (node (ref "U10") (pin "6") (pinfunction "IS_6") (pintype "unspecified"))
      (node (ref "U14") (pin "4") (pinfunction "IS_4") (pintype "unspecified"))
      (node (ref "U9") (pin "6") (pinfunction "IS_6") (pintype "unspecified"))
    )
    (net (code "35") (name "D0{slash}RX") (class "Default")
      (node (ref "R9") (pin "1") (pinfunction "1_1") (pintype "input"))
      (node (ref "U5") (pin "30") (pinfunction "PD0(RXD/PCINT16)_30") (pintype "unspecified"))
    )
    (net (code "36") (name "D1{slash}TX") (class "Default")
      (node (ref "R7") (pin "2") (pinfunction "2_2") (pintype "input"))
      (node (ref "TXD") (pin "1") (pinfunction "-_1") (pintype "input"))
      (node (ref "U5") (pin "31") (pinfunction "PD1(TXD/PCINT17)_31") (pintype "unspecified"))
    )
    (net (code "37") (name "D2{slash}Ch_A") (class "Default")
      (node (ref "R90") (pin "2") (pinfunction "2_2") (pintype "input"))
      (node (ref "U1") (pin "16") (pinfunction "IO32_16") (pintype "unspecified"))
      (node (ref "U5") (pin "32") (pinfunction "PD2(INT0/PCINT18)_32") (pintype "unspecified"))
    )
    (net (code "38") (name "D3{slash}PWM0") (class "Default")
      (node (ref "R27") (pin "1") (pinfunction "1_1") (pintype "input"))
      (node (ref "R55") (pin "1") (pinfunction "1_1") (pintype "unspecified"))
      (node (ref "U1") (pin "8") (pinfunction "IO27_8") (pintype "unspecified"))
      (node (ref "U5") (pin "1") (pinfunction "(PCINT19/OC2B/INT1)PD3_1") (pintype "unspecified"))
    )
    (net (code "39") (name "D4{slash}INH") (class "Default")
      (node (ref "Q12") (pin "2") (pinfunction "2_2") (pintype "input"))
      (node (ref "U1") (pin "32") (pinfunction "IO2_32") (pintype "unspecified"))
      (node (ref "U5") (pin "2") (pinfunction "(PCINT20/XCK/T0)PD4_2") (pintype "unspecified"))
    )
    (net (code "40") (name "D5{slash}En") (class "Default")
      (node (ref "CN18") (pin "1") (pinfunction "1_1") (pintype "unspecified"))
      (node (ref "R59") (pin "2") (pinfunction "2_2") (pintype "input"))
      (node (ref "STEERING") (pin "5") (pinfunction "5_5") (pintype "unspecified"))
      (node (ref "U14") (pin "6") (pinfunction "OUT_6") (pintype "unspecified"))
      (node (ref "U14") (pin "7") (pinfunction "OUT_7") (pintype "unspecified"))
      (node (ref "U14") (pin "8") (pinfunction "OUT_8") (pintype "unspecified"))
    )
    (net (code "41") (name "D5{slash}Servo") (class "Default")
      (node (ref "R59") (pin "1") (pinfunction "1_1") (pintype "input"))
      (node (ref "R96") (pin "2") (pinfunction "2_2") (pintype "input"))
      (node (ref "U1") (pin "23") (pinfunction "IO16_23") (pintype "unspecified"))
      (node (ref "U5") (pin "9") (pinfunction "(PCINT21/OC0B/T1)PD5_9") (pintype "unspecified"))
    )
    (net (code "42") (name "D6{slash}StSw") (class "Default")
      (node (ref "Q1") (pin "3") (pinfunction "D_3") (pintype "unspecified"))
      (node (ref "Q5") (pin "3") (pinfunction "D_3") (pintype "unspecified"))
      (node (ref "R94") (pin "2") (pinfunction "2_2") (pintype "input"))
      (node (ref "U1") (pin "21") (pinfunction "IO34_21") (pintype "unspecified"))
      (node (ref "U5") (pin "10") (pinfunction "(PCINT22/OC0A/AIN0)PD6_10") (pintype "unspecified"))
    )
    (net (code "43") (name "D7{slash}WkSw") (class "Default")
      (node (ref "Q3") (pin "3") (pinfunction "D_3") (pintype "unspecified"))
      (node (ref "U5") (pin "11") (pinfunction "(PCINT23/AIN1)PD7_11") (pintype "unspecified"))
    )
    (net (code "44") (name "D8{slash}RtSw") (class "Default")
      (node (ref "Q4") (pin "3") (pinfunction "D_3") (pintype "unspecified"))
      (node (ref "U5") (pin "12") (pinfunction "(PCINT0/CLKO/ICP1)PB0_12") (pintype "unspecified"))
    )
    (net (code "45") (name "D9{slash}PWM1") (class "Default")
      (node (ref "R26") (pin "1") (pinfunction "1_1") (pintype "input"))
      (node (ref "R62") (pin "2") (pinfunction "2_2") (pintype "unspecified"))
      (node (ref "U1") (pin "10") (pinfunction "IO26_10") (pintype "unspecified"))
      (node (ref "U5") (pin "13") (pinfunction "(PCINT1/OC1A)PB1_13") (pintype "unspecified"))
    )
    (net (code "46") (name "D10{slash}nCS") (class "Default")
      (node (ref "P1") (pin "7") (pinfunction "7_7") (pintype "unspecified"))
      (node (ref "U1") (pin "26") (pinfunction "IO5_26") (pintype "unspecified"))
      (node (ref "U5") (pin "14") (pinfunction "(PCINT2/SS#/OC1B)PB2_14") (pintype "unspecified"))
    )
    (net (code "47") (name "D11{slash}MOSI") (class "Default")
      (node (ref "P1") (pin "5") (pinfunction "5_5") (pintype "unspecified"))
      (node (ref "U1") (pin "22") (pinfunction "IO23_22") (pintype "unspecified"))
      (node (ref "U5") (pin "15") (pinfunction "(PCINT3/OC2A/MOSI)PB3_15") (pintype "unspecified"))
    )
    (net (code "48") (name "D12{slash}MISO") (class "Default")
      (node (ref "P1") (pin "4") (pinfunction "4_4") (pintype "unspecified"))
      (node (ref "R104") (pin "2") (pinfunction "2_2") (pintype "input"))
      (node (ref "U1") (pin "18") (pinfunction "IO19_18") (pintype "unspecified"))
      (node (ref "U5") (pin "16") (pinfunction "(PCINT4/MISO)PB4_16") (pintype "unspecified"))
    )
    (net (code "49") (name "D13{slash}SCK") (class "Default")
      (node (ref "LED") (pin "1") (pinfunction "A_1") (pintype "input"))
      (node (ref "P1") (pin "6") (pinfunction "6_6") (pintype "unspecified"))
      (node (ref "U1") (pin "14") (pinfunction "IO18_14") (pintype "unspecified"))
      (node (ref "U5") (pin "17") (pinfunction "PB5(SCK/PCINT5)_17") (pintype "unspecified"))
    )
    (net (code "50") (name "DN1") (class "Default")
      (node (ref "CN8") (pin "6") (pinfunction "6_6") (pintype "unspecified"))
      (node (ref "TO_PC") (pin "A7") (pinfunction "DN1_A7") (pintype "unspecified"))
      (node (ref "TO_PC") (pin "B7") (pinfunction "DN2_B7") (pintype "unspecified"))
    )
    (net (code "51") (name "DN2") (class "Default")
      (node (ref "CN10") (pin "6") (pinfunction "6_6") (pintype "unspecified"))
      (node (ref "CN9") (pin "6") (pinfunction "6_6") (pintype "unspecified"))
      (node (ref "DC/AUX") (pin "A7") (pinfunction "DN1_A7") (pintype "unspecified"))
      (node (ref "DC/AUX") (pin "B7") (pinfunction "DN2_B7") (pintype "unspecified"))
    )
    (net (code "52") (name "DP1") (class "Default")
      (node (ref "CN8") (pin "5") (pinfunction "5_5") (pintype "unspecified"))
      (node (ref "TO_PC") (pin "A6") (pinfunction "DP1_A6") (pintype "unspecified"))
      (node (ref "TO_PC") (pin "B6") (pinfunction "DP2_B6") (pintype "unspecified"))
    )
    (net (code "53") (name "DP2") (class "Default")
      (node (ref "CN10") (pin "5") (pinfunction "5_5") (pintype "unspecified"))
      (node (ref "CN9") (pin "5") (pinfunction "5_5") (pintype "unspecified"))
      (node (ref "DC/AUX") (pin "A6") (pinfunction "DP1_A6") (pintype "unspecified"))
      (node (ref "DC/AUX") (pin "B6") (pinfunction "DP2_B6") (pintype "unspecified"))
    )
    (net (code "54") (name "Dir485") (class "Default")
      (node (ref "R93") (pin "1") (pinfunction "1_1") (pintype "input"))
      (node (ref "R96") (pin "1") (pinfunction "1_1") (pintype "input"))
      (node (ref "U6") (pin "15") (pinfunction "TNOW_15") (pintype "unspecified"))
      (node (ref "U8") (pin "2") (pinfunction "RE#_2") (pintype "unspecified"))
      (node (ref "U8") (pin "3") (pinfunction "DE_3") (pintype "unspecified"))
    )
    (net (code "55") (name "GND") (class "Default")
      (node (ref "12V") (pin "1") (pinfunction "-_1") (pintype "input"))
      (node (ref "ANT1") (pin "1") (pinfunction "K_1") (pintype "input"))
      (node (ref "ANT2") (pin "1") (pinfunction "K_1") (pintype "input"))
      (node (ref "ARDU1") (pin "6") (pinfunction "6_6") (pintype "unspecified"))
      (node (ref "ARDU1") (pin "8") (pinfunction "8_8") (pintype "unspecified"))
      (node (ref "BOOT") (pin "2") (pinfunction "2_2") (pintype "unspecified"))
      (node (ref "C1") (pin "2") (pinfunction "2_2") (pintype "unspecified"))
      (node (ref "C10") (pin "1") (pinfunction "1_1") (pintype "input"))
      (node (ref "C12") (pin "1") (pinfunction "1_1") (pintype "input"))
      (node (ref "C13") (pin "1") (pinfunction "1_1") (pintype "input"))
      (node (ref "C14") (pin "2") (pinfunction "2_2") (pintype "input"))
      (node (ref "C15") (pin "2") (pinfunction "2_2") (pintype "input"))
      (node (ref "C17") (pin "1") (pinfunction "1_1") (pintype "unspecified"))
      (node (ref "C18") (pin "1") (pinfunction "1_1") (pintype "unspecified"))
      (node (ref "C19") (pin "1") (pinfunction "1_1") (pintype "unspecified"))
      (node (ref "C2") (pin "2") (pinfunction "2_2") (pintype "input"))
      (node (ref "C20") (pin "1") (pinfunction "1_1") (pintype "unspecified"))
      (node (ref "C21") (pin "1") (pinfunction "1_1") (pintype "unspecified"))
      (node (ref "C22") (pin "2") (pinfunction "2_2") (pintype "input"))
      (node (ref "C23") (pin "2") (pinfunction "2_2") (pintype "input"))
      (node (ref "C24") (pin "1") (pinfunction "1_1") (pintype "input"))
      (node (ref "C25") (pin "1") (pinfunction "1_1") (pintype "input"))
      (node (ref "C26") (pin "2") (pinfunction "2_2") (pintype "input"))
      (node (ref "C27") (pin "1") (pinfunction "1_1") (pintype "unspecified"))
      (node (ref "C28") (pin "1") (pinfunction "1_1") (pintype "unspecified"))
      (node (ref "C29") (pin "1") (pinfunction "1_1") (pintype "unspecified"))
      (node (ref "C3") (pin "2") (pinfunction "2_2") (pintype "unspecified"))
      (node (ref "C32") (pin "2") (pinfunction "2_2") (pintype "unspecified"))
      (node (ref "C33") (pin "1") (pinfunction "1_1") (pintype "unspecified"))
      (node (ref "C34") (pin "2") (pinfunction "2_2") (pintype "input"))
      (node (ref "C35") (pin "2") (pinfunction "2_2") (pintype "input"))
      (node (ref "C36") (pin "2") (pinfunction "2_2") (pintype "input"))
      (node (ref "C37") (pin "1") (pinfunction "1_1") (pintype "input"))
      (node (ref "C38") (pin "2") (pinfunction "2_2") (pintype "unspecified"))
      (node (ref "C39") (pin "1") (pinfunction "1_1") (pintype "input"))
      (node (ref "C4") (pin "2") (pinfunction "2_2") (pintype "unspecified"))
      (node (ref "C40") (pin "2") (pinfunction "2_2") (pintype "input"))
      (node (ref "C41") (pin "1") (pinfunction "1_1") (pintype "input"))
      (node (ref "C42") (pin "1") (pinfunction "1_1") (pintype "input"))
      (node (ref "C43") (pin "1") (pinfunction "1_1") (pintype "input"))
      (node (ref "C45") (pin "1") (pinfunction "1_1") (pintype "unspecified"))
      (node (ref "C46") (pin "1") (pinfunction "1_1") (pintype "input"))
      (node (ref "C47") (pin "1") (pinfunction "1_1") (pintype "input"))
      (node (ref "C48") (pin "1") (pinfunction "1_1") (pintype "unspecified"))
      (node (ref "C49") (pin "1") (pinfunction "1_1") (pintype "input"))
      (node (ref "C5") (pin "1") (pinfunction "1_1") (pintype "unspecified"))
      (node (ref "C50") (pin "1") (pinfunction "1_1") (pintype "input"))
      (node (ref "C51") (pin "1") (pinfunction "1_1") (pintype "input"))
      (node (ref "C52") (pin "1") (pinfunction "1_1") (pintype "unspecified"))
      (node (ref "C53") (pin "1") (pinfunction "1_1") (pintype "unspecified"))
      (node (ref "C54") (pin "1") (pinfunction "1_1") (pintype "input"))
      (node (ref "C55") (pin "1") (pinfunction "1_1") (pintype "unspecified"))
      (node (ref "C56") (pin "2") (pinfunction "2_2") (pintype "input"))
      (node (ref "C57") (pin "1") (pinfunction "1_1") (pintype "input"))
      (node (ref "C58") (pin "2") (pinfunction "2_2") (pintype "unspecified"))
      (node (ref "C59") (pin "2") (pinfunction "2_2") (pintype "unspecified"))
      (node (ref "C6") (pin "1") (pinfunction "1_1") (pintype "unspecified"))
      (node (ref "C60") (pin "1") (pinfunction "1_1") (pintype "unspecified"))
      (node (ref "C8") (pin "1") (pinfunction "1_1") (pintype "unspecified"))
      (node (ref "C9") (pin "1") (pinfunction "1_1") (pintype "unspecified"))
      (node (ref "CAN") (pin "3") (pinfunction "-_3") (pintype "unspecified"))
      (node (ref "CAN") (pin "Shield") (pinfunction "Shield_Shield") (pintype "unspecified"))
      (node (ref "CANB") (pin "3") (pinfunction "-_3") (pintype "unspecified"))
      (node (ref "CANB") (pin "Shield") (pinfunction "Shield_Shield") (pintype "unspecified"))
      (node (ref "CN1") (pin "3") (pinfunction "3_3") (pintype "unspecified"))
      (node (ref "CN10") (pin "4") (pinfunction "4_4") (pintype "unspecified"))
      (node (ref "CN11") (pin "3") (pinfunction "3_3") (pintype "unspecified"))
      (node (ref "CN12") (pin "3") (pinfunction "3_3") (pintype "unspecified"))
      (node (ref "CN13") (pin "4") (pinfunction "4_4") (pintype "unspecified"))
      (node (ref "CN14") (pin "4") (pinfunction "4_4") (pintype "unspecified"))
      (node (ref "CN15") (pin "2") (pinfunction "2_2") (pintype "unspecified"))
      (node (ref "CN2") (pin "4") (pinfunction "4_4") (pintype "unspecified"))
      (node (ref "CN3") (pin "1") (pinfunction "1_1") (pintype "unspecified"))
      (node (ref "CN3") (pin "2") (pinfunction "2_2") (pintype "unspecified"))
      (node (ref "CN4") (pin "3") (pinfunction "3_3") (pintype "unspecified"))
      (node (ref "CN5") (pin "2") (pinfunction "2_2") (pintype "unspecified"))
      (node (ref "CN6") (pin "3") (pinfunction "3_3") (pintype "unspecified"))
      (node (ref "CN6") (pin "5") (pinfunction "5_5") (pintype "unspecified"))
      (node (ref "CN6") (pin "9") (pinfunction "9_9") (pintype "unspecified"))
      (node (ref "CN7") (pin "2") (pinfunction "2_2") (pintype "unspecified"))
      (node (ref "CN8") (pin "4") (pinfunction "4_4") (pintype "unspecified"))
      (node (ref "CN9") (pin "4") (pinfunction "4_4") (pintype "unspecified"))
      (node (ref "D2") (pin "1") (pinfunction "K_1") (pintype "unspecified"))
      (node (ref "D5") (pin "3") (pinfunction "3_3") (pintype "unspecified"))
      (node (ref "D6") (pin "3") (pinfunction "3_3") (pintype "unspecified"))
      (node (ref "D7") (pin "3") (pinfunction "3_3") (pintype "unspecified"))
      (node (ref "DC/AUX") (pin "1") (pinfunction "EP_1") (pintype "unspecified"))
      (node (ref "DC/AUX") (pin "2") (pinfunction "EP_2") (pintype "unspecified"))
      (node (ref "DC/AUX") (pin "3") (pinfunction "EP_3") (pintype "unspecified"))
      (node (ref "DC/AUX") (pin "4") (pinfunction "EP_4") (pintype "unspecified"))
      (node (ref "DC/AUX") (pin "A1") (pinfunction "GND_A1") (pintype "unspecified"))
      (node (ref "DC/AUX") (pin "A12") (pinfunction "GND_A12") (pintype "unspecified"))
      (node (ref "DC/AUX") (pin "B1") (pinfunction "GND_B1") (pintype "unspecified"))
      (node (ref "DC/AUX") (pin "B12") (pinfunction "GND_B12") (pintype "unspecified"))
      (node (ref "DIFF") (pin "1") (pinfunction "K_1") (pintype "input"))
      (node (ref "GNSS") (pin "4") (pinfunction "gn_4") (pintype "unspecified"))
      (node (ref "GNSS") (pin "Shield") (pinfunction "Shield_Shield") (pintype "unspecified"))
      (node (ref "H1") (pin "3") (pinfunction "3_3") (pintype "unspecified"))
      (node (ref "INPUTS") (pin "3") (pinfunction "-_3") (pintype "unspecified"))
      (node (ref "INPUTS") (pin "Shield") (pinfunction "Shield_Shield") (pintype "unspecified"))
      (node (ref "J7") (pin "1") (pinfunction "1_1") (pintype "unspecified"))
      (node (ref "LED1") (pin "1") (pinfunction "K_1") (pintype "input"))
      (node (ref "LED2") (pin "1") (pinfunction "-_1") (pintype "input"))
      (node (ref "LED3") (pin "1") (pinfunction "K_1") (pintype "input"))
      (node (ref "LED4") (pin "1") (pinfunction "-_1") (pintype "input"))
      (node (ref "P1") (pin "10") (pinfunction "10_10") (pintype "unspecified"))
      (node (ref "POWER") (pin "3") (pinfunction "-_3") (pintype "unspecified"))
      (node (ref "POWER") (pin "Shield") (pinfunction "Shield_Shield") (pintype "unspecified"))
      (node (ref "Q1") (pin "2") (pinfunction "S_2") (pintype "unspecified"))
      (node (ref "Q10") (pin "3") (pinfunction "3_3") (pintype "input"))
      (node (ref "Q11") (pin "3") (pinfunction "3_3") (pintype "input"))
      (node (ref "Q3") (pin "2") (pinfunction "S_2") (pintype "unspecified"))
      (node (ref "Q4") (pin "2") (pinfunction "S_2") (pintype "unspecified"))
      (node (ref "Q5") (pin "2") (pinfunction "S_2") (pintype "unspecified"))
      (node (ref "Q6") (pin "2") (pinfunction "S_2") (pintype "unspecified"))
      (node (ref "Q9") (pin "3") (pinfunction "3_3") (pintype "input"))
      (node (ref "QWIIC") (pin "1") (pinfunction "GND_1") (pintype "unspecified"))
      (node (ref "QWIIC") (pin "5") (pinfunction "NC1_5") (pintype "unspecified"))
      (node (ref "QWIIC") (pin "6") (pinfunction "NC2_6") (pintype "unspecified"))
      (node (ref "R1") (pin "1") (pinfunction "1_1") (pintype "input"))
      (node (ref "R10") (pin "1") (pinfunction "1_1") (pintype "input"))
      (node (ref "R100") (pin "1") (pinfunction "1_1") (pintype "input"))
      (node (ref "R102") (pin "2") (pinfunction "2_2") (pintype "input"))
      (node (ref "R14") (pin "1") (pinfunction "1_1") (pintype "input"))
      (node (ref "R16") (pin "2") (pinfunction "2_2") (pintype "input"))
      (node (ref "R18") (pin "1") (pinfunction "1_1") (pintype "input"))
      (node (ref "R25") (pin "2") (pinfunction "2_2") (pintype "input"))
      (node (ref "R26") (pin "2") (pinfunction "2_2") (pintype "input"))
      (node (ref "R27") (pin "2") (pinfunction "2_2") (pintype "input"))
      (node (ref "R36") (pin "1") (pinfunction "1_1") (pintype "input"))
      (node (ref "R38") (pin "2") (pinfunction "2_2") (pintype "input"))
      (node (ref "R42") (pin "2") (pinfunction "2_2") (pintype "input"))
      (node (ref "R43") (pin "1") (pinfunction "1_1") (pintype "input"))
      (node (ref "R44") (pin "1") (pinfunction "1_1") (pintype "input"))
      (node (ref "R46") (pin "1") (pinfunction "1_1") (pintype "input"))
      (node (ref "R47") (pin "1") (pinfunction "1_1") (pintype "input"))
      (node (ref "R70") (pin "1") (pinfunction "1_1") (pintype "input"))
      (node (ref "R77") (pin "2") (pinfunction "2_2") (pintype "input"))
      (node (ref "R81") (pin "2") (pinfunction "2_2") (pintype "input"))
      (node (ref "R82") (pin "2") (pinfunction "2_2") (pintype "input"))
      (node (ref "R93") (pin "2") (pinfunction "2_2") (pintype "input"))
      (node (ref "R99") (pin "2") (pinfunction "2_2") (pintype "input"))
      (node (ref "ROTARY/485") (pin "3") (pinfunction "-_3") (pintype "unspecified"))
      (node (ref "ROTARY/485") (pin "Shield") (pinfunction "Shield_Shield") (pintype "unspecified"))
      (node (ref "STEERING") (pin "3") (pinfunction "-_3") (pintype "unspecified"))
      (node (ref "STEERING") (pin "Shield") (pinfunction "Shield_Shield") (pintype "unspecified"))
      (node (ref "TO_PC") (pin "1") (pinfunction "EP_1") (pintype "unspecified"))
      (node (ref "TO_PC") (pin "2") (pinfunction "EP_2") (pintype "unspecified"))
      (node (ref "TO_PC") (pin "3") (pinfunction "EP_3") (pintype "unspecified"))
      (node (ref "TO_PC") (pin "4") (pinfunction "EP_4") (pintype "unspecified"))
      (node (ref "TO_PC") (pin "A1") (pinfunction "GND_A1") (pintype "unspecified"))
      (node (ref "TO_PC") (pin "A12") (pinfunction "GND_A12") (pintype "unspecified"))
      (node (ref "TO_PC") (pin "B1") (pinfunction "GND_B1") (pintype "unspecified"))
      (node (ref "TO_PC") (pin "B12") (pinfunction "GND_B12") (pintype "unspecified"))
      (node (ref "U1") (pin "1") (pinfunction "GND_1") (pintype "unspecified"))
      (node (ref "U1") (pin "27") (pinfunction "GND_27") (pintype "unspecified"))
      (node (ref "U1") (pin "4") (pinfunction "GND_4") (pintype "unspecified"))
      (node (ref "U11") (pin "14") (pinfunction "USB1_AVSSTX3V3_14") (pintype "unspecified"))
      (node (ref "U11") (pin "2") (pinfunction "VSS_2") (pintype "unspecified"))
      (node (ref "U11") (pin "22") (pinfunction "VSS_22") (pintype "unspecified"))
      (node (ref "U11") (pin "30") (pinfunction "VSSA/VREFN_30") (pintype "unspecified"))
      (node (ref "U11") (pin "34") (pinfunction "VSS_34") (pintype "unspecified"))
      (node (ref "U11") (pin "49") (pinfunction "VSS_49") (pintype "unspecified"))
      (node (ref "U11") (pin "51") (pinfunction "RTCXIN_51") (pintype "unspecified"))
      (node (ref "U11") (pin "53") (pinfunction "VSS_53") (pintype "unspecified"))
      (node (ref "U11") (pin "6") (pinfunction "USB1_AVSSC_6") (pintype "unspecified"))
      (node (ref "U11") (pin "71") (pinfunction "VSS_71") (pintype "unspecified"))
      (node (ref "U11") (pin "79") (pinfunction "VSS_79") (pintype "unspecified"))
      (node (ref "U11") (pin "96") (pinfunction "VSS_96") (pintype "unspecified"))
      (node (ref "U12") (pin "2") (pinfunction "GND_2") (pintype "unspecified"))
      (node (ref "U12") (pin "8") (pinfunction "S_8") (pintype "unspecified"))
      (node (ref "U13") (pin "1") (pinfunction "GND_1") (pintype "unspecified"))
      (node (ref "U15") (pin "6") (pinfunction "GND_6") (pintype "passive"))
      (node (ref "U16") (pin "14") (pinfunction "GND_14") (pintype "unspecified"))
      (node (ref "U16") (pin "17") (pinfunction "GND_17") (pintype "unspecified"))
      (node (ref "U16") (pin "20") (pinfunction "GND_20") (pintype "unspecified"))
      (node (ref "U16") (pin "22") (pinfunction "GND_22") (pintype "unspecified"))
      (node (ref "U17") (pin "1") (pinfunction "ADDR_1") (pintype "unspecified"))
      (node (ref "U17") (pin "3") (pinfunction "GND_3") (pintype "unspecified"))
      (node (ref "U18") (pin "10") (pinfunction "GND_10") (pintype "unspecified"))
      (node (ref "U18") (pin "12") (pinfunction "GND_12") (pintype "unspecified"))
      (node (ref "U18") (pin "5") (pinfunction "GND_5") (pintype "unspecified"))
      (node (ref "U18") (pin "7") (pinfunction "SA0_7") (pintype "unspecified"))
      (node (ref "U19") (pin "1") (pinfunction "GND_1") (pintype "unspecified"))
      (node (ref "U2") (pin "1") (pinfunction "VSS_1") (pintype "unspecified"))
      (node (ref "U3") (pin "1") (pinfunction "GND_1") (pintype "unspecified"))
      (node (ref "U4") (pin "1") (pinfunction "GND_1") (pintype "unspecified"))
      (node (ref "U5") (pin "21") (pinfunction "GND_21") (pintype "unspecified"))
      (node (ref "U5") (pin "3") (pinfunction "GND_3") (pintype "unspecified"))
      (node (ref "U5") (pin "5") (pinfunction "GND_5") (pintype "unspecified"))
      (node (ref "U6") (pin "1") (pinfunction "GND_1") (pintype "unspecified"))
      (node (ref "U7") (pin "2") (pinfunction "GND_2") (pintype "unspecified"))
      (node (ref "U7") (pin "8") (pinfunction "S_8") (pintype "unspecified"))
      (node (ref "U8") (pin "5") (pinfunction "GND_5") (pintype "unspecified"))
      (node (ref "USB1") (pin "0") (pinfunction "SHLD_0") (pintype "unspecified"))
      (node (ref "USB1") (pin "4") (pinfunction "GND_4") (pintype "input"))
      (node (ref "USB_AUX") (pin "4") (pinfunction "GND_4") (pintype "unspecified"))
      (node (ref "USB_AUX") (pin "8") (pinfunction "GND_8") (pintype "unspecified"))
      (node (ref "USB_AUX") (pin "9") (pinfunction "9_9") (pintype "unspecified"))
      (node (ref "WAS1") (pin "3") (pinfunction "-_3") (pintype "unspecified"))
      (node (ref "WAS1") (pin "Shield") (pinfunction "Shield_Shield") (pintype "unspecified"))
      (node (ref "X1") (pin "2") (pinfunction "GND_2") (pintype "input"))
      (node (ref "X1") (pin "4") (pinfunction "GND_4") (pintype "input"))
      (node (ref "X2") (pin "2") (pinfunction "GND_2") (pintype "unspecified"))
      (node (ref "X2") (pin "4") (pinfunction "GND_4") (pintype "unspecified"))
      (node (ref "X3") (pin "2") (pinfunction "GND_2") (pintype "unspecified"))
      (node (ref "X3") (pin "4") (pinfunction "GND_4") (pintype "unspecified"))
    )
    (net (code "56") (name "GNSS+") (class "Default")
      (node (ref "F1") (pin "1") (pinfunction "1_1") (pintype "unspecified"))
      (node (ref "GNSS") (pin "2") (pinfunction "wh/gn_2") (pintype "unspecified"))
      (node (ref "R64") (pin "2") (pinfunction "2_2") (pintype "input"))
    )
    (net (code "57") (name "INH") (class "Default")
      (node (ref "R61") (pin "2") (pinfunction "2_2") (pintype "unspecified"))
      (node (ref "U10") (pin "3") (pinfunction "INH_3") (pintype "unspecified"))
      (node (ref "U14") (pin "2") (pinfunction "IN_2") (pintype "unspecified"))
      (node (ref "U14") (pin "3") (pinfunction "DEN_3") (pintype "unspecified"))
      (node (ref "U9") (pin "3") (pinfunction "INH_3") (pintype "unspecified"))
    )
    (net (code "58") (name "In+") (class "Default")
      (node (ref "ARDU1") (pin "7") (pinfunction "7_7") (pintype "unspecified"))
      (node (ref "CN17") (pin "1") (pinfunction "1_1") (pintype "unspecified"))
      (node (ref "F4") (pin "2") (pinfunction "2_2") (pintype "unspecified"))
      (node (ref "INPUTS") (pin "2") (pinfunction "2_2") (pintype "unspecified"))
      (node (ref "R73") (pin "2") (pinfunction "2_2") (pintype "input"))
    )
    (net (code "59") (name "In0") (class "Default")
      (node (ref "CN17") (pin "4") (pinfunction "4_4") (pintype "unspecified"))
      (node (ref "INPUTS") (pin "5") (pinfunction "5_5") (pintype "unspecified"))
      (node (ref "STEER") (pin "2") (pinfunction "A_2") (pintype "input"))
    )
    (net (code "60") (name "In1") (class "Default")
      (node (ref "CN17") (pin "2") (pinfunction "2_2") (pintype "unspecified"))
      (node (ref "INPUTS") (pin "1") (pinfunction "+_1") (pintype "unspecified"))
      (node (ref "WORK") (pin "2") (pinfunction "A_2") (pintype "input"))
    )
    (net (code "61") (name "In2") (class "Default")
      (node (ref "CN17") (pin "3") (pinfunction "3_3") (pintype "unspecified"))
      (node (ref "INPUTS") (pin "4") (pinfunction "4_4") (pintype "unspecified"))
      (node (ref "REMOTE") (pin "2") (pinfunction "A_2") (pintype "input"))
    )
    (net (code "62") (name "MA") (class "Default")
      (node (ref "CN18") (pin "4") (pinfunction "4_4") (pintype "unspecified"))
      (node (ref "M1") (pin "2") (pinfunction "A_2") (pintype "input"))
      (node (ref "M2") (pin "1") (pinfunction "K_1") (pintype "input"))
      (node (ref "STEERING") (pin "4") (pinfunction "4_4") (pintype "unspecified"))
      (node (ref "U10") (pin "8") (pinfunction "OUT_8") (pintype "unspecified"))
    )
    (net (code "63") (name "MB") (class "Default")
      (node (ref "CN18") (pin "2") (pinfunction "2_2") (pintype "unspecified"))
      (node (ref "R24") (pin "2") (pinfunction "2_2") (pintype "input"))
      (node (ref "STEERING") (pin "2") (pinfunction "2_2") (pintype "unspecified"))
      (node (ref "U9") (pin "4") (pinfunction "OUT_4") (pintype "unspecified"))
      (node (ref "U9") (pin "8") (pinfunction "OUT_8") (pintype "unspecified"))
    )
    (net (code "64") (name "Net-(3V3--)") (class "Default")
      (node (ref "3V3") (pin "1") (pinfunction "-_1") (pintype "input"))
      (node (ref "R102") (pin "1") (pinfunction "1_1") (pintype "input"))
    )
    (net (code "65") (name "Net-(5V--)") (class "Default")
      (node (ref "5V") (pin "1") (pinfunction "-_1") (pintype "input"))
      (node (ref "R70") (pin "2") (pinfunction "2_2") (pintype "input"))
    )
    (net (code "66") (name "Net-(12V-+)") (class "Default")
      (node (ref "12V") (pin "2") (pinfunction "+_2") (pintype "input"))
      (node (ref "R100") (pin "2") (pinfunction "2_2") (pintype "input"))
      (node (ref "R15") (pin "1") (pinfunction "1_1") (pintype "input"))
      (node (ref "U4") (pin "5") (pinfunction "EN_5") (pintype "unspecified"))
    )
    (net (code "67") (name "Net-(ANT1-A)") (class "Default")
      (node (ref "ANT1") (pin "2") (pinfunction "A_2") (pintype "input"))
      (node (ref "R56") (pin "1") (pinfunction "1_1") (pintype "input"))
    )
    (net (code "68") (name "Net-(ANT2-A)") (class "Default")
      (node (ref "ANT2") (pin "2") (pinfunction "A_2") (pintype "input"))
      (node (ref "R52") (pin "1") (pinfunction "1_1") (pintype "input"))
    )
    (net (code "69") (name "Net-(ARDU-A)") (class "Default")
      (node (ref "ARDU") (pin "2") (pinfunction "A_2") (pintype "input"))
      (node (ref "AUX0") (pin "2") (pinfunction "A_2") (pintype "input"))
      (node (ref "AUX1") (pin "1") (pinfunction "-_1") (pintype "input"))
      (node (ref "GNSS_") (pin "1") (pinfunction "-_1") (pintype "input"))
      (node (ref "U2") (pin "22") (pinfunction "DRV_22") (pintype "unspecified"))
      (node (ref "USB:") (pin "2") (pinfunction "A_2") (pintype "input"))
    )
    (net (code "70") (name "Net-(ARDU-K)") (class "Default")
      (node (ref "ARDU") (pin "1") (pinfunction "K_1") (pintype "input"))
      (node (ref "AUX1") (pin "2") (pinfunction "+_2") (pintype "input"))
      (node (ref "R4") (pin "1") (pinfunction "1_1") (pintype "input"))
    )
    (net (code "71") (name "Net-(AUX0-K)") (class "Default")
      (node (ref "AUX0") (pin "1") (pinfunction "K_1") (pintype "input"))
      (node (ref "GNSS_") (pin "2") (pinfunction "+_2") (pintype "input"))
      (node (ref "R3") (pin "2") (pinfunction "2_2") (pintype "input"))
    )
    (net (code "72") (name "Net-(C52-Pad2)") (class "Default")
      (node (ref "C52") (pin "2") (pinfunction "2_2") (pintype "unspecified"))
      (node (ref "C62") (pin "2") (pinfunction "2_2") (pintype "input"))
      (node (ref "L1") (pin "2") (pinfunction "2_2") (pintype "unspecified"))
      (node (ref "L2") (pin "1") (pinfunction "1_1") (pintype "input"))
      (node (ref "R19") (pin "2") (pinfunction "2_2") (pintype "input"))
    )
    (net (code "73") (name "Net-(CHA-K)") (class "Default")
      (node (ref "CHA") (pin "1") (pinfunction "K_1") (pintype "input"))
      (node (ref "R32") (pin "2") (pinfunction "2_2") (pintype "input"))
    )
    (net (code "74") (name "Net-(CHB-K)") (class "Default")
      (node (ref "CHB") (pin "1") (pinfunction "K_1") (pintype "input"))
      (node (ref "R31") (pin "2") (pinfunction "2_2") (pintype "input"))
    )
    (net (code "75") (name "Net-(CN13-Pad1)") (class "Default")
      (node (ref "CN13") (pin "1") (pinfunction "1_1") (pintype "unspecified"))
      (node (ref "CN14") (pin "1") (pinfunction "1_1") (pintype "unspecified"))
      (node (ref "R46") (pin "2") (pinfunction "2_2") (pintype "input"))
    )
    (net (code "76") (name "Net-(CN13-Pad2)") (class "Default")
      (node (ref "CN13") (pin "2") (pinfunction "2_2") (pintype "unspecified"))
      (node (ref "CN14") (pin "2") (pinfunction "2_2") (pintype "unspecified"))
      (node (ref "R43") (pin "2") (pinfunction "2_2") (pintype "input"))
    )
    (net (code "77") (name "Net-(CN13-Pad3)") (class "Default")
      (node (ref "CN13") (pin "3") (pinfunction "3_3") (pintype "unspecified"))
      (node (ref "CN2") (pin "1") (pinfunction "1_1") (pintype "unspecified"))
      (node (ref "CN3") (pin "5") (pinfunction "5_5") (pintype "unspecified"))
      (node (ref "R50") (pin "1") (pinfunction "1_1") (pintype "input"))
    )
    (net (code "78") (name "Net-(CN14-Pad3)") (class "Default")
      (node (ref "CN14") (pin "3") (pinfunction "3_3") (pintype "unspecified"))
      (node (ref "J1") (pin "1") (pinfunction "1_1") (pintype "unspecified"))
    )
    (net (code "79") (name "Net-(DIFF-A)") (class "Default")
      (node (ref "DIFF") (pin "2") (pinfunction "A_2") (pintype "input"))
      (node (ref "R98") (pin "1") (pinfunction "1_1") (pintype "input"))
    )
    (net (code "80") (name "Net-(FCAN-A)") (class "Default")
      (node (ref "F2") (pin "1") (pinfunction "1_1") (pintype "unspecified"))
      (node (ref "FCAN") (pin "1") (pinfunction "A_1") (pintype "input"))
      (node (ref "J2") (pin "1") (pinfunction "1_1") (pintype "unspecified"))
    )
    (net (code "81") (name "Net-(FCAN-K)") (class "Default")
      (node (ref "FCAN") (pin "2") (pinfunction "K_2") (pintype "input"))
      (node (ref "R71") (pin "1") (pinfunction "1_1") (pintype "input"))
    )
    (net (code "82") (name "Net-(FCAN1-A)") (class "Default")
      (node (ref "F3") (pin "1") (pinfunction "1_1") (pintype "unspecified"))
      (node (ref "FCAN1") (pin "1") (pinfunction "A_1") (pintype "input"))
      (node (ref "J3") (pin "1") (pinfunction "1_1") (pintype "unspecified"))
    )
    (net (code "83") (name "Net-(FCAN1-K)") (class "Default")
      (node (ref "FCAN1") (pin "2") (pinfunction "K_2") (pintype "input"))
      (node (ref "R72") (pin "1") (pinfunction "1_1") (pintype "input"))
    )
    (net (code "84") (name "Net-(FGNSS-K)") (class "Default")
      (node (ref "FGNSS") (pin "2") (pinfunction "K_2") (pintype "input"))
      (node (ref "R64") (pin "1") (pinfunction "1_1") (pintype "input"))
    )
    (net (code "85") (name "Net-(FINP-K)") (class "Default")
      (node (ref "FINP") (pin "2") (pinfunction "K_2") (pintype "input"))
      (node (ref "R73") (pin "1") (pinfunction "1_1") (pintype "input"))
    )
    (net (code "86") (name "Net-(FROT-K)") (class "Default")
      (node (ref "FROT") (pin "2") (pinfunction "K_2") (pintype "input"))
      (node (ref "R75") (pin "1") (pinfunction "1_1") (pintype "input"))
    )
    (net (code "87") (name "Net-(FSER-K)") (class "Default")
      (node (ref "FSER") (pin "2") (pinfunction "K_2") (pintype "input"))
      (node (ref "R76") (pin "2") (pinfunction "2_2") (pintype "input"))
    )
    (net (code "88") (name "Net-(FWAS-K)") (class "Default")
      (node (ref "FWAS") (pin "2") (pinfunction "K_2") (pintype "input"))
      (node (ref "R74") (pin "1") (pinfunction "1_1") (pintype "input"))
    )
    (net (code "89") (name "Net-(GNSS-+_wh{slash}or)") (class "Default")
      (node (ref "GNSS") (pin "1") (pinfunction "+_wh/or_1") (pintype "unspecified"))
      (node (ref "J9") (pin "4") (pinfunction "4_4") (pintype "unspecified"))
    )
    (net (code "90") (name "Net-(GNSS--_or)") (class "Default")
      (node (ref "GNSS") (pin "3") (pinfunction "-_or_3") (pintype "unspecified"))
      (node (ref "J9") (pin "3") (pinfunction "3_3") (pintype "unspecified"))
    )
    (net (code "91") (name "Net-(J2-Pad4)") (class "Default")
      (node (ref "J2") (pin "4") (pinfunction "4_4") (pintype "unspecified"))
      (node (ref "R60") (pin "2") (pinfunction "2_2") (pintype "input"))
    )
    (net (code "92") (name "Net-(J3-Pad4)") (class "Default")
      (node (ref "J3") (pin "4") (pinfunction "4_4") (pintype "unspecified"))
      (node (ref "R65") (pin "2") (pinfunction "2_2") (pintype "input"))
    )
    (net (code "93") (name "Net-(J4-Pad2)") (class "Default")
      (node (ref "J4") (pin "2") (pinfunction "2_2") (pintype "unspecified"))
      (node (ref "R92") (pin "1") (pinfunction "1_1") (pintype "input"))
    )
    (net (code "94") (name "Net-(J8-Pad3)") (class "Default")
      (node (ref "J8") (pin "3") (pinfunction "3_3") (pintype "unspecified"))
      (node (ref "R15") (pin "2") (pinfunction "2_2") (pintype "input"))
    )
    (net (code "95") (name "Net-(LED-K)") (class "Default")
      (node (ref "LED") (pin "2") (pinfunction "K_2") (pintype "input"))
      (node (ref "R10") (pin "2") (pinfunction "2_2") (pintype "input"))
    )
    (net (code "96") (name "Net-(LED1-A)") (class "Default")
      (node (ref "LED1") (pin "2") (pinfunction "A_2") (pintype "input"))
      (node (ref "R84") (pin "1") (pinfunction "1_1") (pintype "input"))
    )
    (net (code "97") (name "Net-(LED2-+)") (class "Default")
      (node (ref "LED2") (pin "2") (pinfunction "+_2") (pintype "input"))
      (node (ref "R85") (pin "1") (pinfunction "1_1") (pintype "input"))
    )
    (net (code "98") (name "Net-(LED3-A)") (class "Default")
      (node (ref "LED3") (pin "2") (pinfunction "A_2") (pintype "input"))
      (node (ref "R86") (pin "1") (pinfunction "1_1") (pintype "input"))
    )
    (net (code "99") (name "Net-(LED4-+)") (class "Default")
      (node (ref "LED4") (pin "2") (pinfunction "+_2") (pintype "input"))
      (node (ref "R87") (pin "1") (pinfunction "1_1") (pintype "input"))
    )
    (net (code "100") (name "Net-(M1-K)") (class "Default")
      (node (ref "M1") (pin "1") (pinfunction "K_1") (pintype "input"))
      (node (ref "M2") (pin "2") (pinfunction "A_2") (pintype "input"))
      (node (ref "R24") (pin "1") (pinfunction "1_1") (pintype "input"))
    )
    (net (code "101") (name "Net-(MOT--)") (class "Default")
      (node (ref "MOT") (pin "1") (pinfunction "-_1") (pintype "input"))
      (node (ref "R49") (pin "2") (pinfunction "2_2") (pintype "input"))
      (node (ref "R51") (pin "1") (pinfunction "1_1") (pintype "input"))
      (node (ref "R8") (pin "1") (pinfunction "1_1") (pintype "input"))
    )
    (net (code "102") (name "Net-(Q1-G)") (class "Default")
      (node (ref "C28") (pin "2") (pinfunction "2_2") (pintype "unspecified"))
      (node (ref "Q1") (pin "1") (pinfunction "G_1") (pintype "unspecified"))
      (node (ref "R41") (pin "2") (pinfunction "2_2") (pintype "input"))
      (node (ref "R44") (pin "2") (pinfunction "2_2") (pintype "input"))
    )
    (net (code "103") (name "Net-(Q2-Pad1)") (class "Default")
      (node (ref "Q2") (pin "1") (pinfunction "1_1") (pintype "input"))
      (node (ref "R8") (pin "2") (pinfunction "2_2") (pintype "input"))
    )
    (net (code "104") (name "Net-(Q2-Pad3)") (class "Default")
      (node (ref "Q2") (pin "3") (pinfunction "3_3") (pintype "input"))
      (node (ref "R63") (pin "1") (pinfunction "1_1") (pintype "unspecified"))
    )
    (net (code "105") (name "Net-(Q6-G)") (class "Default")
      (node (ref "Q6") (pin "1") (pinfunction "G_1") (pintype "unspecified"))
      (node (ref "R33") (pin "1") (pinfunction "1_1") (pintype "input"))
    )
    (net (code "106") (name "Net-(Q8-G)") (class "Default")
      (node (ref "Q8") (pin "4") (pinfunction "G_4") (pintype "unspecified"))
      (node (ref "R35") (pin "2") (pinfunction "2_2") (pintype "input"))
      (node (ref "R39") (pin "2") (pinfunction "2_2") (pintype "input"))
    )
    (net (code "107") (name "Net-(Q9-Pad2)") (class "Default")
      (node (ref "Q9") (pin "2") (pinfunction "2_2") (pintype "input"))
      (node (ref "R58") (pin "1") (pinfunction "1_1") (pintype "input"))
    )
    (net (code "108") (name "Net-(Q10-Pad2)") (class "Default")
      (node (ref "Q10") (pin "2") (pinfunction "2_2") (pintype "input"))
      (node (ref "R57") (pin "1") (pinfunction "1_1") (pintype "input"))
    )
    (net (code "109") (name "Net-(Q12-Pad1)") (class "Default")
      (node (ref "Q12") (pin "1") (pinfunction "1_1") (pintype "input"))
      (node (ref "R42") (pin "1") (pinfunction "1_1") (pintype "input"))
    )
    (net (code "110") (name "Net-(Q12-Pad3)") (class "Default")
      (node (ref "Q12") (pin "3") (pinfunction "3_3") (pintype "input"))
      (node (ref "R61") (pin "1") (pinfunction "1_1") (pintype "unspecified"))
    )
    (net (code "111") (name "Net-(R80-Pad2)") (class "Default")
      (node (ref "R80") (pin "2") (pinfunction "2_2") (pintype "input"))
      (node (ref "R81") (pin "1") (pinfunction "1_1") (pintype "input"))
      (node (ref "R82") (pin "1") (pinfunction "1_1") (pintype "input"))
    )
    (net (code "112") (name "Net-(REMOTE-K)") (class "Default")
      (node (ref "R40") (pin "1") (pinfunction "1_1") (pintype "input"))
      (node (ref "REMOTE") (pin "1") (pinfunction "K_1") (pintype "input"))
    )
    (net (code "113") (name "Net-(RX485-K)") (class "Default")
      (node (ref "R66") (pin "1") (pinfunction "1_1") (pintype "input"))
      (node (ref "RX485") (pin "1") (pinfunction "K_1") (pintype "input"))
    )
    (net (code "114") (name "Net-(RXCAN-K)") (class "Default")
      (node (ref "R68") (pin "1") (pinfunction "1_1") (pintype "input"))
      (node (ref "RXCAN") (pin "1") (pinfunction "K_1") (pintype "input"))
    )
    (net (code "115") (name "Net-(RXCAN1-K)") (class "Default")
      (node (ref "R89") (pin "1") (pinfunction "1_1") (pintype "input"))
      (node (ref "RXCAN1") (pin "1") (pinfunction "K_1") (pintype "input"))
    )
    (net (code "116") (name "Net-(RXD-A)") (class "Default")
      (node (ref "R23") (pin "1") (pinfunction "1_1") (pintype "input"))
      (node (ref "RXD") (pin "2") (pinfunction "A_2") (pintype "input"))
    )
    (net (code "117") (name "Net-(STEER-K)") (class "Default")
      (node (ref "R41") (pin "1") (pinfunction "1_1") (pintype "input"))
      (node (ref "STEER") (pin "1") (pinfunction "K_1") (pintype "input"))
    )
    (net (code "118") (name "Net-(TX485--)") (class "Default")
      (node (ref "R67") (pin "1") (pinfunction "1_1") (pintype "input"))
      (node (ref "TX485") (pin "1") (pinfunction "-_1") (pintype "input"))
    )
    (net (code "119") (name "Net-(TXCAN--)") (class "Default")
      (node (ref "R69") (pin "1") (pinfunction "1_1") (pintype "input"))
      (node (ref "TXCAN") (pin "1") (pinfunction "-_1") (pintype "input"))
    )
    (net (code "120") (name "Net-(TXCAN1--)") (class "Default")
      (node (ref "R88") (pin "1") (pinfunction "1_1") (pintype "input"))
      (node (ref "TXCAN1") (pin "1") (pinfunction "-_1") (pintype "input"))
    )
    (net (code "121") (name "Net-(TXD-+)") (class "Default")
      (node (ref "R22") (pin "1") (pinfunction "1_1") (pintype "input"))
      (node (ref "TXD") (pin "2") (pinfunction "+_2") (pintype "input"))
    )
    (net (code "122") (name "Net-(U1-RES)") (class "Default")
      (node (ref "C55") (pin "2") (pinfunction "2_2") (pintype "unspecified"))
      (node (ref "U1") (pin "2") (pinfunction "RES_2") (pintype "unspecified"))
    )
    (net (code "123") (name "Net-(U2-LED1)") (class "Default")
      (node (ref "R4") (pin "2") (pinfunction "2_2") (pintype "input"))
      (node (ref "U2") (pin "23") (pinfunction "LED1_23") (pintype "unspecified"))
    )
    (net (code "124") (name "Net-(U2-LED2)") (class "Default")
      (node (ref "R3") (pin "1") (pinfunction "1_1") (pintype "input"))
      (node (ref "U2") (pin "24") (pinfunction "LED2_24") (pintype "unspecified"))
    )
    (net (code "125") (name "Net-(U2-REXT)") (class "Default")
      (node (ref "R1") (pin "2") (pinfunction "2_2") (pintype "input"))
      (node (ref "U2") (pin "14") (pinfunction "REXT_14") (pintype "unspecified"))
    )
    (net (code "126") (name "Net-(U2-TESTJ)") (class "Default")
      (node (ref "R2") (pin "1") (pinfunction "1_1") (pintype "input"))
      (node (ref "U2") (pin "27") (pinfunction "TESTJ_27") (pintype "unspecified"))
    )
    (net (code "127") (name "Net-(U2-VBUSM)") (class "Default")
      (node (ref "Q7") (pin "3") (pinfunction "3_3") (pintype "input"))
      (node (ref "R50") (pin "2") (pinfunction "2_2") (pintype "input"))
      (node (ref "U2") (pin "18") (pinfunction "VBUSM_18") (pintype "unspecified"))
    )
    (net (code "128") (name "Net-(U2-XIN)") (class "Default")
      (node (ref "C23") (pin "1") (pinfunction "1_1") (pintype "input"))
      (node (ref "U2") (pin "3") (pinfunction "XIN_3") (pintype "unspecified"))
      (node (ref "X2") (pin "3") (pinfunction "OSC2_3") (pintype "unspecified"))
    )
    (net (code "129") (name "Net-(U2-XOUT)") (class "Default")
      (node (ref "C13") (pin "2") (pinfunction "2_2") (pintype "input"))
      (node (ref "U2") (pin "2") (pinfunction "XOUT_2") (pintype "unspecified"))
      (node (ref "X2") (pin "1") (pinfunction "OSC1_1") (pintype "unspecified"))
    )
    (net (code "130") (name "Net-(U3-DTR#)") (class "Default")
      (node (ref "C7") (pin "2") (pinfunction "2_2") (pintype "unspecified"))
      (node (ref "U3") (pin "13") (pinfunction "DTR#_13") (pintype "unspecified"))
    )
    (net (code "131") (name "Net-(U3-V3)") (class "Default")
      (node (ref "C1") (pin "1") (pinfunction "1_1") (pintype "unspecified"))
      (node (ref "U3") (pin "4") (pinfunction "V3_4") (pintype "unspecified"))
    )
    (net (code "132") (name "Net-(U4-BOOT)") (class "Default")
      (node (ref "C16") (pin "1") (pinfunction "1_1") (pintype "unspecified"))
      (node (ref "U4") (pin "6") (pinfunction "BOOT_6") (pintype "unspecified"))
    )
    (net (code "133") (name "Net-(U5-(PCINT6{slash}XTAL1{slash}TOSC1)PB6)") (class "Default")
      (node (ref "C6") (pin "2") (pinfunction "2_2") (pintype "unspecified"))
      (node (ref "U5") (pin "7") (pinfunction "(PCINT6/XTAL1/TOSC1)PB6_7") (pintype "unspecified"))
      (node (ref "X1") (pin "3") (pinfunction "3_3") (pintype "input"))
    )
    (net (code "134") (name "Net-(U5-(PCINT7{slash}XTAL2{slash}TOSC2)PB7)") (class "Default")
      (node (ref "C5") (pin "2") (pinfunction "2_2") (pintype "unspecified"))
      (node (ref "U5") (pin "8") (pinfunction "(PCINT7/XTAL2/TOSC2)PB7_8") (pintype "unspecified"))
      (node (ref "X1") (pin "1") (pinfunction "1_1") (pintype "input"))
    )
    (net (code "135") (name "Net-(U5-AREF)") (class "Default")
      (node (ref "C3") (pin "1") (pinfunction "1_1") (pintype "unspecified"))
      (node (ref "U5") (pin "20") (pinfunction "AREF_20") (pintype "unspecified"))
    )
    (net (code "136") (name "Net-(U6-V3)") (class "Default")
      (node (ref "C38") (pin "1") (pinfunction "1_1") (pintype "unspecified"))
      (node (ref "U6") (pin "4") (pinfunction "V3_4") (pintype "unspecified"))
    )
    (net (code "137") (name "Net-(U9-IN)") (class "Default")
      (node (ref "R55") (pin "2") (pinfunction "2_2") (pintype "unspecified"))
      (node (ref "U9") (pin "2") (pinfunction "IN_2") (pintype "unspecified"))
    )
    (net (code "138") (name "Net-(U9-SR)") (class "Default")
      (node (ref "R11") (pin "2") (pinfunction "2_2") (pintype "input"))
      (node (ref "U9") (pin "5") (pinfunction "SR_5") (pintype "unspecified"))
    )
    (net (code "139") (name "Net-(U10-IN)") (class "Default")
      (node (ref "R62") (pin "1") (pinfunction "1_1") (pintype "unspecified"))
      (node (ref "U10") (pin "2") (pinfunction "IN_2") (pintype "unspecified"))
    )
    (net (code "140") (name "Net-(U10-SR)") (class "Default")
      (node (ref "R21") (pin "1") (pinfunction "1_1") (pintype "input"))
      (node (ref "U10") (pin "5") (pinfunction "SR_5") (pintype "unspecified"))
    )
    (net (code "141") (name "Net-(U11-PIO0_5{slash}CAN0_TD)") (class "Default")
      (node (ref "R83") (pin "2") (pinfunction "2_2") (pintype "input"))
      (node (ref "U11") (pin "89") (pinfunction "PIO0_5/CAN0_TD_89") (pintype "bidirectional"))
    )
    (net (code "142") (name "Net-(U11-PIO0_6{slash}FC3_SCK)") (class "Default")
      (node (ref "BOOT") (pin "1") (pinfunction "1_1") (pintype "unspecified"))
      (node (ref "R83") (pin "1") (pinfunction "1_1") (pintype "input"))
      (node (ref "U11") (pin "90") (pinfunction "PIO0_6/FC3_SCK_90") (pintype "bidirectional"))
    )
    (net (code "143") (name "Net-(U11-PIO0_23{slash}SPIFI_CSN)") (class "Default")
      (node (ref "R84") (pin "2") (pinfunction "2_2") (pintype "input"))
      (node (ref "U11") (pin "35") (pinfunction "PIO0_23/SPIFI_CSN_35") (pintype "bidirectional"))
    )
    (net (code "144") (name "Net-(U11-PIO0_24{slash}SPIFI_IO0)") (class "Default")
      (node (ref "R87") (pin "2") (pinfunction "2_2") (pintype "input"))
      (node (ref "U11") (pin "38") (pinfunction "PIO0_24/SPIFI_IO0_38") (pintype "bidirectional"))
    )
    (net (code "145") (name "Net-(U11-PIO1_8{slash}SD_CLK)") (class "Default")
      (node (ref "R85") (pin "2") (pinfunction "2_2") (pintype "input"))
      (node (ref "U11") (pin "36") (pinfunction "PIO1_8/SD_CLK_36") (pintype "bidirectional"))
    )
    (net (code "146") (name "Net-(U11-PIO1_21{slash}FC4_RXD_SDA_MOSI)") (class "Default")
      (node (ref "R86") (pin "2") (pinfunction "2_2") (pintype "input"))
      (node (ref "U11") (pin "37") (pinfunction "PIO1_21/FC4_RXD_SDA_MOSI_37") (pintype "bidirectional"))
    )
    (net (code "147") (name "Net-(U11-USB1_REXT)") (class "Default")
      (node (ref "R80") (pin "1") (pinfunction "1_1") (pintype "input"))
      (node (ref "U11") (pin "7") (pinfunction "USB1_REXT_7") (pintype "unspecified"))
    )
    (net (code "148") (name "Net-(U11-XTALIN)") (class "Default")
      (node (ref "C39") (pin "2") (pinfunction "2_2") (pintype "input"))
      (node (ref "U11") (pin "20") (pinfunction "XTALIN_20") (pintype "unspecified"))
      (node (ref "X3") (pin "3") (pinfunction "OSC2_3") (pintype "unspecified"))
    )
    (net (code "149") (name "Net-(U11-XTALOUT)") (class "Default")
      (node (ref "C37") (pin "2") (pinfunction "2_2") (pintype "input"))
      (node (ref "U11") (pin "19") (pinfunction "XTALOUT_19") (pintype "unspecified"))
      (node (ref "X3") (pin "1") (pinfunction "OSC1_1") (pintype "unspecified"))
    )
    (net (code "150") (name "Net-(U13-BOOT)") (class "Default")
      (node (ref "C11") (pin "1") (pinfunction "1_1") (pintype "unspecified"))
      (node (ref "U13") (pin "6") (pinfunction "BOOT_6") (pintype "unspecified"))
    )
    (net (code "151") (name "Net-(U13-FB)") (class "Default")
      (node (ref "C62") (pin "1") (pinfunction "1_1") (pintype "input"))
      (node (ref "R19") (pin "1") (pinfunction "1_1") (pintype "input"))
      (node (ref "R99") (pin "1") (pinfunction "1_1") (pintype "input"))
      (node (ref "U13") (pin "4") (pinfunction "FB_4") (pintype "unspecified"))
    )
    (net (code "152") (name "Net-(U13-SW)") (class "Default")
      (node (ref "C11") (pin "2") (pinfunction "2_2") (pintype "unspecified"))
      (node (ref "L1") (pin "1") (pinfunction "1_1") (pintype "unspecified"))
      (node (ref "U13") (pin "2") (pinfunction "SW_2") (pintype "unspecified"))
    )
    (net (code "153") (name "Net-(U16-Ant1{slash}{slash})") (class "Default")
      (node (ref "R56") (pin "2") (pinfunction "2_2") (pintype "input"))
      (node (ref "U16") (pin "7") (pinfunction "Ant1//_7") (pintype "unspecified"))
    )
    (net (code "154") (name "Net-(U16-Ant2{slash}CANRX{slash}{slash})") (class "Default")
      (node (ref "R52") (pin "2") (pinfunction "2_2") (pintype "input"))
      (node (ref "U16") (pin "10") (pinfunction "Ant2/CANRX//_10") (pintype "unspecified"))
    )
    (net (code "155") (name "Net-(U16-SCLK{slash}{slash})") (class "Default")
      (node (ref "R98") (pin "2") (pinfunction "2_2") (pintype "input"))
      (node (ref "U16") (pin "21") (pinfunction "SCLK//_21") (pintype "unspecified"))
    )
    (net (code "156") (name "Net-(U18-BYP)") (class "Default")
      (node (ref "C8") (pin "2") (pinfunction "2_2") (pintype "unspecified"))
      (node (ref "U18") (pin "2") (pinfunction "BYP_2") (pintype "unspecified"))
    )
    (net (code "157") (name "Net-(U19-V3)") (class "Default")
      (node (ref "C58") (pin "1") (pinfunction "1_1") (pintype "unspecified"))
      (node (ref "U19") (pin "4") (pinfunction "V3_4") (pintype "unspecified"))
    )
    (net (code "158") (name "Net-(USB:-K)") (class "Default")
      (node (ref "R14") (pin "2") (pinfunction "2_2") (pintype "input"))
      (node (ref "USB:") (pin "1") (pinfunction "K_1") (pintype "input"))
    )
    (net (code "159") (name "Net-(WAS2-K)") (class "Default")
      (node (ref "R58") (pin "2") (pinfunction "2_2") (pintype "input"))
      (node (ref "WAS2") (pin "1") (pinfunction "K_1") (pintype "input"))
    )
    (net (code "160") (name "Net-(WAS3-K)") (class "Default")
      (node (ref "R57") (pin "2") (pinfunction "2_2") (pintype "input"))
      (node (ref "WAS3") (pin "1") (pinfunction "K_1") (pintype "input"))
    )
    (net (code "161") (name "Net-(WIFI--)") (class "Default")
      (node (ref "R95") (pin "2") (pinfunction "2_2") (pintype "input"))
      (node (ref "WIFI") (pin "1") (pinfunction "-_1") (pintype "input"))
    )
    (net (code "162") (name "Net-(WORK-K)") (class "Default")
      (node (ref "R45") (pin "1") (pinfunction "1_1") (pintype "input"))
      (node (ref "WORK") (pin "1") (pinfunction "K_1") (pintype "input"))
    )
    (net (code "163") (name "Out") (class "Default")
      (node (ref "J8") (pin "1") (pinfunction "1_1") (pintype "unspecified"))
      (node (ref "Q6") (pin "3") (pinfunction "D_3") (pintype "unspecified"))
    )
    (net (code "164") (name "Rot+") (class "Default")
      (node (ref "CN1") (pin "1") (pinfunction "1_1") (pintype "unspecified"))
      (node (ref "F6") (pin "2") (pinfunction "2_2") (pintype "unspecified"))
      (node (ref "R75") (pin "2") (pinfunction "2_2") (pintype "input"))
      (node (ref "ROTARY/485") (pin "1") (pinfunction "+_1") (pintype "unspecified"))
    )
    (net (code "165") (name "RxD485") (class "Default")
      (node (ref "Q11") (pin "1") (pinfunction "1_1") (pintype "input"))
      (node (ref "R66") (pin "2") (pinfunction "2_2") (pintype "input"))
      (node (ref "U6") (pin "3") (pinfunction "RXD_3") (pintype "unspecified"))
      (node (ref "U8") (pin "1") (pinfunction "RO_1") (pintype "unspecified"))
    )
    (net (code "166") (name "RxDCAN") (class "Default")
      (node (ref "R68") (pin "2") (pinfunction "2_2") (pintype "input"))
      (node (ref "U1") (pin "12") (pinfunction "IO25_12") (pintype "unspecified"))
      (node (ref "U11") (pin "60") (pinfunction "PIO1_3/CAN0_RD_60") (pintype "bidirectional"))
      (node (ref "U7") (pin "4") (pinfunction "RXD_4") (pintype "unspecified"))
    )
    (net (code "167") (name "RxDCAN1") (class "Default")
      (node (ref "R89") (pin "2") (pinfunction "2_2") (pintype "input"))
      (node (ref "U11") (pin "5") (pinfunction "PIO1_18/FC8_TXD_SCL_MISO_5") (pintype "bidirectional"))
      (node (ref "U12") (pin "4") (pinfunction "RXD_4") (pintype "unspecified"))
    )
    (net (code "168") (name "RxD_ESP") (class "Default")
      (node (ref "Q11") (pin "2") (pinfunction "2_2") (pintype "input"))
      (node (ref "U1") (pin "7") (pinfunction "RXD_7") (pintype "unspecified"))
    )
    (net (code "169") (name "RxD_GNSS") (class "Default")
      (node (ref "ARDU1") (pin "2") (pinfunction "2_2") (pintype "unspecified"))
      (node (ref "U16") (pin "16") (pinfunction "RxD1_16") (pintype "unspecified"))
      (node (ref "U19") (pin "2") (pinfunction "TXD_2") (pintype "unspecified"))
    )
    (net (code "170") (name "SW!") (class "Default")
      (node (ref "C16") (pin "2") (pinfunction "2_2") (pintype "unspecified"))
      (node (ref "L7") (pin "1") (pinfunction "1_1") (pintype "unspecified"))
      (node (ref "U4") (pin "2") (pinfunction "SW_2") (pintype "unspecified"))
    )
    (net (code "171") (name "SWCLK") (class "Default")
      (node (ref "CN6") (pin "4") (pinfunction "4_4") (pintype "unspecified"))
      (node (ref "R78") (pin "2") (pinfunction "2_2") (pintype "input"))
      (node (ref "U11") (pin "24") (pinfunction "PIO0_11/SWCLK_24") (pintype "unspecified"))
    )
    (net (code "172") (name "SWDIO") (class "Default")
      (node (ref "CN6") (pin "2") (pinfunction "2_2") (pintype "unspecified"))
      (node (ref "R79") (pin "2") (pinfunction "2_2") (pintype "input"))
      (node (ref "U11") (pin "25") (pinfunction "PIO0_12/SWDIO_25") (pintype "unspecified"))
    )
    (net (code "173") (name "Servo+") (class "Default")
      (node (ref "CN18") (pin "3") (pinfunction "3_3") (pintype "unspecified"))
      (node (ref "F7") (pin "2") (pinfunction "2_2") (pintype "unspecified"))
      (node (ref "R76") (pin "1") (pinfunction "1_1") (pintype "input"))
      (node (ref "STEERING") (pin "1") (pinfunction "+_1") (pintype "unspecified"))
    )
    (net (code "174") (name "SteerEnable") (class "Default")
      (node (ref "J7") (pin "2") (pinfunction "2_2") (pintype "unspecified"))
      (node (ref "Q5") (pin "1") (pinfunction "G_1") (pintype "unspecified"))
      (node (ref "R16") (pin "1") (pinfunction "1_1") (pintype "input"))
      (node (ref "R63") (pin "2") (pinfunction "2_2") (pintype "unspecified"))
    )
    (net (code "175") (name "TxD485") (class "Default")
      (node (ref "R67") (pin "2") (pinfunction "2_2") (pintype "input"))
      (node (ref "U1") (pin "3") (pinfunction "TXD_3") (pintype "unspecified"))
      (node (ref "U6") (pin "2") (pinfunction "TXD_2") (pintype "unspecified"))
      (node (ref "U8") (pin "4") (pinfunction "DI_4") (pintype "unspecified"))
    )
    (net (code "176") (name "TxDCAN") (class "Default")
      (node (ref "R69") (pin "2") (pinfunction "2_2") (pintype "input"))
      (node (ref "U1") (pin "19") (pinfunction "IO17_19") (pintype "unspecified"))
      (node (ref "U11") (pin "58") (pinfunction "PIO1_2/CAN0_TD_58") (pintype "bidirectional"))
      (node (ref "U7") (pin "1") (pinfunction "TXD_1") (pintype "unspecified"))
    )
    (net (code "177") (name "TxDCAN1") (class "Default")
      (node (ref "R88") (pin "2") (pinfunction "2_2") (pintype "input"))
      (node (ref "U11") (pin "47") (pinfunction "PIO1_17/ENET_MDIO_47") (pintype "bidirectional"))
      (node (ref "U12") (pin "1") (pinfunction "TXD_1") (pintype "unspecified"))
    )
    (net (code "178") (name "TxD_GNSS") (class "Default")
      (node (ref "ARDU1") (pin "3") (pinfunction "3_3") (pintype "unspecified"))
      (node (ref "U16") (pin "15") (pinfunction "TxD1_15") (pintype "unspecified"))
      (node (ref "U19") (pin "3") (pinfunction "RXD_3") (pintype "unspecified"))
    )
    (net (code "179") (name "USB_Aux0_N") (class "Default")
      (node (ref "CN14") (pin "6") (pinfunction "6_6") (pintype "unspecified"))
      (node (ref "U2") (pin "8") (pinfunction "DM2_8") (pintype "unspecified"))
      (node (ref "U6") (pin "6") (pinfunction "UD-_6") (pintype "unspecified"))
      (node (ref "USB_AUX") (pin "6") (pinfunction "D-_6") (pintype "unspecified"))
    )
    (net (code "180") (name "USB_Aux0_P") (class "Default")
      (node (ref "CN14") (pin "5") (pinfunction "5_5") (pintype "unspecified"))
      (node (ref "U2") (pin "9") (pinfunction "DP2_9") (pintype "unspecified"))
      (node (ref "U6") (pin "5") (pinfunction "UD+_5") (pintype "unspecified"))
      (node (ref "USB_AUX") (pin "7") (pinfunction "D+_7") (pintype "unspecified"))
    )
    (net (code "181") (name "USB_Aux1_N") (class "Default")
      (node (ref "U11") (pin "12") (pinfunction "USB1_DM_12") (pintype "unspecified"))
      (node (ref "U2") (pin "6") (pinfunction "DM3_6") (pintype "unspecified"))
      (node (ref "USB_AUX") (pin "2") (pinfunction "D-_2") (pintype "unspecified"))
    )
    (net (code "182") (name "USB_Aux1_P") (class "Default")
      (node (ref "U11") (pin "13") (pinfunction "USB1_DP_13") (pintype "unspecified"))
      (node (ref "U2") (pin "7") (pinfunction "DP3_7") (pintype "unspecified"))
      (node (ref "USB_AUX") (pin "3") (pinfunction "D+_3") (pintype "unspecified"))
    )
    (net (code "183") (name "USB_Nano_N") (class "Default")
      (node (ref "U2") (pin "10") (pinfunction "DM1_10") (pintype "unspecified"))
      (node (ref "U3") (pin "6") (pinfunction "UD-_6") (pintype "unspecified"))
      (node (ref "UARDU") (pin "1") (pinfunction "1_1") (pintype "unspecified"))
    )
    (net (code "184") (name "USB_Nano_P") (class "Default")
      (node (ref "U2") (pin "11") (pinfunction "DP1_11") (pintype "unspecified"))
      (node (ref "U3") (pin "5") (pinfunction "UD+_5") (pintype "unspecified"))
      (node (ref "UARDU") (pin "2") (pinfunction "2_2") (pintype "unspecified"))
    )
    (net (code "185") (name "USB_RTU_N") (class "Default")
      (node (ref "J9") (pin "1") (pinfunction "1_1") (pintype "unspecified"))
      (node (ref "U19") (pin "6") (pinfunction "UD-_6") (pintype "unspecified"))
      (node (ref "U2") (pin "4") (pinfunction "DM4_4") (pintype "unspecified"))
      (node (ref "USB1") (pin "2") (pinfunction "D-_2") (pintype "input"))
    )
    (net (code "186") (name "USB_RTU_P") (class "Default")
      (node (ref "J9") (pin "2") (pinfunction "2_2") (pintype "unspecified"))
      (node (ref "U19") (pin "5") (pinfunction "UD+_5") (pintype "unspecified"))
      (node (ref "U2") (pin "5") (pinfunction "DP4_5") (pintype "unspecified"))
      (node (ref "USB1") (pin "3") (pinfunction "D+_3") (pintype "input"))
    )
    (net (code "187") (name "USB_Up_N") (class "Default")
      (node (ref "CN13") (pin "6") (pinfunction "6_6") (pintype "unspecified"))
      (node (ref "CN2") (pin "2") (pinfunction "2_2") (pintype "unspecified"))
      (node (ref "CN3") (pin "4") (pinfunction "4_4") (pintype "unspecified"))
      (node (ref "U2") (pin "15") (pinfunction "DMU_15") (pintype "unspecified"))
    )
    (net (code "188") (name "USB_Up_P") (class "Default")
      (node (ref "CN13") (pin "5") (pinfunction "5_5") (pintype "unspecified"))
      (node (ref "CN2") (pin "3") (pinfunction "3_3") (pintype "unspecified"))
      (node (ref "CN3") (pin "3") (pinfunction "3_3") (pintype "unspecified"))
      (node (ref "U2") (pin "16") (pinfunction "DPU_16") (pintype "unspecified"))
    )
    (net (code "189") (name "VBUS") (class "Default")
      (node (ref "CN10") (pin "3") (pinfunction "3_3") (pintype "unspecified"))
      (node (ref "CN8") (pin "3") (pinfunction "3_3") (pintype "unspecified"))
      (node (ref "CN9") (pin "3") (pinfunction "3_3") (pintype "unspecified"))
      (node (ref "DC/AUX") (pin "A4") (pinfunction "VBUS_A4") (pintype "unspecified"))
      (node (ref "DC/AUX") (pin "A9") (pinfunction "VBUS_A9") (pintype "unspecified"))
      (node (ref "DC/AUX") (pin "B4") (pinfunction "VBUS_B4") (pintype "unspecified"))
      (node (ref "DC/AUX") (pin "B9") (pinfunction "VBUS_B9") (pintype "unspecified"))
      (node (ref "TO_PC") (pin "A4") (pinfunction "VBUS_A4") (pintype "unspecified"))
      (node (ref "TO_PC") (pin "A9") (pinfunction "VBUS_A9") (pintype "unspecified"))
      (node (ref "TO_PC") (pin "B4") (pinfunction "VBUS_B4") (pintype "unspecified"))
      (node (ref "TO_PC") (pin "B9") (pinfunction "VBUS_B9") (pintype "unspecified"))
    )
    (net (code "190") (name "WAS") (class "Default")
      (node (ref "CN5") (pin "3") (pinfunction "3_3") (pintype "unspecified"))
      (node (ref "OP1") (pin "1") (pinfunction "1_1") (pintype "unspecified"))
      (node (ref "Q9") (pin "1") (pinfunction "1_1") (pintype "input"))
      (node (ref "R13") (pin "2") (pinfunction "2_2") (pintype "input"))
      (node (ref "WAS1") (pin "4") (pinfunction "4_4") (pintype "unspecified"))
    )
    (net (code "191") (name "WAS+") (class "Default")
      (node (ref "CN5") (pin "1") (pinfunction "1_1") (pintype "unspecified"))
      (node (ref "F5") (pin "2") (pinfunction "2_2") (pintype "unspecified"))
      (node (ref "R74") (pin "2") (pinfunction "2_2") (pintype "input"))
      (node (ref "WAS1") (pin "1") (pinfunction "+_1") (pintype "unspecified"))
    )
    (net (code "192") (name "WAS_0V") (class "Default")
      (node (ref "CN5") (pin "4") (pinfunction "4_4") (pintype "unspecified"))
      (node (ref "OP1") (pin "2") (pinfunction "2_2") (pintype "unspecified"))
      (node (ref "Q10") (pin "1") (pinfunction "1_1") (pintype "input"))
      (node (ref "R5") (pin "2") (pinfunction "2_2") (pintype "input"))
    )
    (net (code "193") (name "WAS_N") (class "Default")
      (node (ref "C33") (pin "2") (pinfunction "2_2") (pintype "unspecified"))
      (node (ref "R5") (pin "1") (pinfunction "1_1") (pintype "input"))
      (node (ref "U1") (pin "9") (pinfunction "SVN_9") (pintype "unspecified"))
      (node (ref "U17") (pin "5") (pinfunction "AIN1_5") (pintype "unspecified"))
    )
    (net (code "194") (name "WiFiLED") (class "Default")
      (node (ref "R95") (pin "1") (pinfunction "1_1") (pintype "input"))
      (node (ref "U1") (pin "28") (pinfunction "IO0_28") (pintype "unspecified"))
    )
    (net (code "195") (name "_Reset") (class "Default")
      (node (ref "C7") (pin "1") (pinfunction "1_1") (pintype "unspecified"))
      (node (ref "H1") (pin "2") (pinfunction "2_2") (pintype "unspecified"))
      (node (ref "R6") (pin "1") (pinfunction "1_1") (pintype "input"))
      (node (ref "U5") (pin "29") (pinfunction "PC6(RESET#/PCINT14)_29") (pintype "unspecified"))
    )
    (net (code "196") (name "_ResetNXP") (class "Default")
      (node (ref "CN6") (pin "10") (pinfunction "10_10") (pintype "unspecified"))
      (node (ref "U11") (pin "48") (pinfunction "RESETN_48") (pintype "unspecified"))
    )
    (net (code "197") (name "_RxD") (class "Default")
      (node (ref "R9") (pin "2") (pinfunction "2_2") (pintype "input"))
      (node (ref "RXD") (pin "1") (pinfunction "K_1") (pintype "input"))
      (node (ref "U3") (pin "2") (pinfunction "TXD_2") (pintype "unspecified"))
    )
    (net (code "198") (name "_TxD") (class "Default")
      (node (ref "R7") (pin "1") (pinfunction "1_1") (pintype "input"))
      (node (ref "U3") (pin "3") (pinfunction "RXD_3") (pintype "unspecified"))
    )
    (net (code "199") (name "_URES") (class "Default")
      (node (ref "R34") (pin "1") (pinfunction "1_1") (pintype "input"))
      (node (ref "U2") (pin "17") (pinfunction "XRSTJ_17") (pintype "unspecified"))
    )
    (net (code "200") (name "unconnected-(CN6-Pad6)") (class "Default")
      (node (ref "CN6") (pin "6") (pinfunction "6_6") (pintype "unspecified+no_connect"))
    )
    (net (code "201") (name "unconnected-(CN6-Pad7)") (class "Default")
      (node (ref "CN6") (pin "7") (pinfunction "7_7") (pintype "unspecified+no_connect"))
    )
    (net (code "202") (name "unconnected-(CN6-Pad8)") (class "Default")
      (node (ref "CN6") (pin "8") (pinfunction "8_8") (pintype "unspecified+no_connect"))
    )
    (net (code "203") (name "unconnected-(CN6-Pad11)") (class "Default")
      (node (ref "CN6") (pin "11") (pinfunction "11_11") (pintype "unspecified+no_connect"))
    )
    (net (code "204") (name "unconnected-(CN6-Pad12)") (class "Default")
      (node (ref "CN6") (pin "12") (pinfunction "12_12") (pintype "unspecified+no_connect"))
    )
    (net (code "205") (name "unconnected-(DC/AUX-SUB1-PadA8)") (class "Default")
      (node (ref "DC/AUX") (pin "A8") (pinfunction "SUB1_A8") (pintype "unspecified+no_connect"))
    )
    (net (code "206") (name "unconnected-(DC/AUX-SUB2-PadB8)") (class "Default")
      (node (ref "DC/AUX") (pin "B8") (pinfunction "SUB2_B8") (pintype "unspecified+no_connect"))
    )
    (net (code "207") (name "unconnected-(P1-Pad1)") (class "Default")
      (node (ref "P1") (pin "1") (pinfunction "1_1") (pintype "unspecified+no_connect"))
    )
    (net (code "208") (name "unconnected-(P1-Pad2)") (class "Default")
      (node (ref "P1") (pin "2") (pinfunction "2_2") (pintype "unspecified+no_connect"))
    )
    (net (code "209") (name "unconnected-(P1-Pad3)") (class "Default")
      (node (ref "P1") (pin "3") (pinfunction "3_3") (pintype "unspecified+no_connect"))
    )
    (net (code "210") (name "unconnected-(P1-Pad8)") (class "Default")
      (node (ref "P1") (pin "8") (pinfunction "8_8") (pintype "unspecified+no_connect"))
    )
    (net (code "211") (name "unconnected-(P2---Pad2)") (class "Default")
      (node (ref "P2") (pin "2") (pinfunction "-_2") (pintype "unspecified+no_connect"))
    )
    (net (code "212") (name "unconnected-(P2---Pad3)") (class "Default")
      (node (ref "P2") (pin "3") (pinfunction "-_3") (pintype "unspecified+no_connect"))
    )
    (net (code "213") (name "unconnected-(P2---Pad4)") (class "Default")
      (node (ref "P2") (pin "4") (pinfunction "-_4") (pintype "unspecified+no_connect"))
    )
    (net (code "214") (name "unconnected-(P2---Pad5)") (class "Default")
      (node (ref "P2") (pin "5") (pinfunction "-_5") (pintype "unspecified+no_connect"))
    )
    (net (code "215") (name "unconnected-(P2---Pad6)") (class "Default")
      (node (ref "P2") (pin "6") (pinfunction "-_6") (pintype "unspecified+no_connect"))
    )
    (net (code "216") (name "unconnected-(P2---Pad8)") (class "Default")
      (node (ref "P2") (pin "8") (pinfunction "-_8") (pintype "unspecified+no_connect"))
    )
    (net (code "217") (name "unconnected-(P2---Pad9)") (class "Default")
      (node (ref "P2") (pin "9") (pinfunction "-_9") (pintype "unspecified+no_connect"))
    )
    (net (code "218") (name "unconnected-(P2---Pad10)") (class "Default")
      (node (ref "P2") (pin "10") (pinfunction "-_10") (pintype "unspecified+no_connect"))
    )
    (net (code "219") (name "unconnected-(P2---Pad14)") (class "Default")
      (node (ref "P2") (pin "14") (pinfunction "-_14") (pintype "unspecified+no_connect"))
    )
    (net (code "220") (name "unconnected-(P2---Pad15)") (class "Default")
      (node (ref "P2") (pin "15") (pinfunction "-_15") (pintype "unspecified+no_connect"))
    )
    (net (code "221") (name "unconnected-(P2---Pad16)") (class "Default")
      (node (ref "P2") (pin "16") (pinfunction "-_16") (pintype "unspecified+no_connect"))
    )
    (net (code "222") (name "unconnected-(P2---Pad17)") (class "Default")
      (node (ref "P2") (pin "17") (pinfunction "-_17") (pintype "unspecified+no_connect"))
    )
    (net (code "223") (name "unconnected-(P2---Pad18)") (class "Default")
      (node (ref "P2") (pin "18") (pinfunction "-_18") (pintype "unspecified+no_connect"))
    )
    (net (code "224") (name "unconnected-(P2---Pad19)") (class "Default")
      (node (ref "P2") (pin "19") (pinfunction "-_19") (pintype "unspecified+no_connect"))
    )
    (net (code "225") (name "unconnected-(P2---Pad20)") (class "Default")
      (node (ref "P2") (pin "20") (pinfunction "-_20") (pintype "unspecified+no_connect"))
    )
    (net (code "226") (name "unconnected-(P2---Pad21)") (class "Default")
      (node (ref "P2") (pin "21") (pinfunction "-_21") (pintype "unspecified+no_connect"))
    )
    (net (code "227") (name "unconnected-(P2---Pad22)") (class "Default")
      (node (ref "P2") (pin "22") (pinfunction "-_22") (pintype "unspecified+no_connect"))
    )
    (net (code "228") (name "unconnected-(P2---Pad23)") (class "Default")
      (node (ref "P2") (pin "23") (pinfunction "-_23") (pintype "unspecified+no_connect"))
    )
    (net (code "229") (name "unconnected-(P2---Pad24)") (class "Default")
      (node (ref "P2") (pin "24") (pinfunction "-_24") (pintype "unspecified+no_connect"))
    )
    (net (code "230") (name "unconnected-(P2---Pad25)") (class "Default")
      (node (ref "P2") (pin "25") (pinfunction "-_25") (pintype "unspecified+no_connect"))
    )
    (net (code "231") (name "unconnected-(P2---Pad27)") (class "Default")
      (node (ref "P2") (pin "27") (pinfunction "-_27") (pintype "unspecified+no_connect"))
    )
    (net (code "232") (name "unconnected-(P2---Pad28)") (class "Default")
      (node (ref "P2") (pin "28") (pinfunction "-_28") (pintype "unspecified+no_connect"))
    )
    (net (code "233") (name "unconnected-(P2---Pad32)") (class "Default")
      (node (ref "P2") (pin "32") (pinfunction "-_32") (pintype "unspecified+no_connect"))
    )
    (net (code "234") (name "unconnected-(P2-5V_IN-Pad29)") (class "Default")
      (node (ref "P2") (pin "29") (pinfunction "5V_IN_29") (pintype "unspecified+no_connect"))
    )
    (net (code "235") (name "unconnected-(P2-GND-Pad7)") (class "Default")
      (node (ref "P2") (pin "7") (pinfunction "GND_7") (pintype "unspecified+no_connect"))
    )
    (net (code "236") (name "unconnected-(P2-GND-Pad30)") (class "Default")
      (node (ref "P2") (pin "30") (pinfunction "GND_30") (pintype "unspecified+no_connect"))
    )
    (net (code "237") (name "unconnected-(P2-GND-Pad31)") (class "Default")
      (node (ref "P2") (pin "31") (pinfunction "GND_31") (pintype "unspecified+no_connect"))
    )
    (net (code "238") (name "unconnected-(P2-IOREF-Pad26)") (class "Default")
      (node (ref "P2") (pin "26") (pinfunction "IOREF_26") (pintype "unspecified+no_connect"))
    )
    (net (code "239") (name "unconnected-(P2-RX1-Pad12)") (class "Default")
      (node (ref "P2") (pin "12") (pinfunction "RX1_12") (pintype "unspecified+no_connect"))
    )
    (net (code "240") (name "unconnected-(P2-RX2-Pad1)") (class "Default")
      (node (ref "P2") (pin "1") (pinfunction "RX2_1") (pintype "unspecified+no_connect"))
    )
    (net (code "241") (name "unconnected-(P2-TX1-Pad11)") (class "Default")
      (node (ref "P2") (pin "11") (pinfunction "TX1_11") (pintype "unspecified+no_connect"))
    )
    (net (code "242") (name "unconnected-(P2-TX2-Pad13)") (class "Default")
      (node (ref "P2") (pin "13") (pinfunction "TX2_13") (pintype "unspecified+no_connect"))
    )
    (net (code "243") (name "unconnected-(Q7-Pad2)") (class "Default")
      (node (ref "Q7") (pin "2") (pinfunction "2_2") (pintype "input+no_connect"))
    )
    (net (code "244") (name "unconnected-(TO_PC-SUB1-PadA8)") (class "Default")
      (node (ref "TO_PC") (pin "A8") (pinfunction "SUB1_A8") (pintype "unspecified+no_connect"))
    )
    (net (code "245") (name "unconnected-(TO_PC-SUB2-PadB8)") (class "Default")
      (node (ref "TO_PC") (pin "B8") (pinfunction "SUB2_B8") (pintype "unspecified+no_connect"))
    )
    (net (code "246") (name "unconnected-(U1-CLK-Pad40)") (class "Default")
      (node (ref "U1") (pin "40") (pinfunction "CLK_40") (pintype "unspecified+no_connect"))
    )
    (net (code "247") (name "unconnected-(U1-CMD-Pad37)") (class "Default")
      (node (ref "U1") (pin "37") (pinfunction "CMD_37") (pintype "unspecified+no_connect"))
    )
    (net (code "248") (name "unconnected-(U1-NC-Pad5)") (class "Default")
      (node (ref "U1") (pin "5") (pinfunction "NC_5") (pintype "unspecified+no_connect"))
    )
    (net (code "249") (name "unconnected-(U1-NC-Pad29)") (class "Default")
      (node (ref "U1") (pin "29") (pinfunction "NC_29") (pintype "unspecified+no_connect"))
    )
    (net (code "250") (name "unconnected-(U1-SD0-Pad39)") (class "Default")
      (node (ref "U1") (pin "39") (pinfunction "SD0_39") (pintype "unspecified+no_connect"))
    )
    (net (code "251") (name "unconnected-(U1-SD1-Pad36)") (class "Default")
      (node (ref "U1") (pin "36") (pinfunction "SD1_36") (pintype "unspecified+no_connect"))
    )
    (net (code "252") (name "unconnected-(U1-SD2-Pad33)") (class "Default")
      (node (ref "U1") (pin "33") (pinfunction "SD2_33") (pintype "unspecified+no_connect"))
    )
    (net (code "253") (name "unconnected-(U1-SD3-Pad38)") (class "Default")
      (node (ref "U1") (pin "38") (pinfunction "SD3_38") (pintype "unspecified+no_connect"))
    )
    (net (code "254") (name "unconnected-(U1-TCK-Pad34)") (class "Default")
      (node (ref "U1") (pin "34") (pinfunction "TCK_34") (pintype "unspecified+no_connect"))
    )
    (net (code "255") (name "unconnected-(U1-TD0-Pad35)") (class "Default")
      (node (ref "U1") (pin "35") (pinfunction "TD0_35") (pintype "unspecified+no_connect"))
    )
    (net (code "256") (name "unconnected-(U1-TDI-Pad20)") (class "Default")
      (node (ref "U1") (pin "20") (pinfunction "TDI_20") (pintype "unspecified+no_connect"))
    )
    (net (code "257") (name "unconnected-(U1-TMS-Pad25)") (class "Default")
      (node (ref "U1") (pin "25") (pinfunction "TMS_25") (pintype "unspecified+no_connect"))
    )
    (net (code "258") (name "unconnected-(U2-PWRJ-Pad25)") (class "Default")
      (node (ref "U2") (pin "25") (pinfunction "PWRJ_25") (pintype "unspecified+no_connect"))
    )
    (net (code "259") (name "unconnected-(U3-CTS#-Pad9)") (class "Default")
      (node (ref "U3") (pin "9") (pinfunction "CTS#_9") (pintype "unspecified+no_connect"))
    )
    (net (code "260") (name "unconnected-(U3-DCD#-Pad12)") (class "Default")
      (node (ref "U3") (pin "12") (pinfunction "DCD#_12") (pintype "unspecified+no_connect"))
    )
    (net (code "261") (name "unconnected-(U3-DSR#-Pad10)") (class "Default")
      (node (ref "U3") (pin "10") (pinfunction "DSR#_10") (pintype "unspecified+no_connect"))
    )
    (net (code "262") (name "unconnected-(U3-NC.-Pad8)") (class "Default")
      (node (ref "U3") (pin "8") (pinfunction "NC._8") (pintype "unspecified+no_connect"))
    )
    (net (code "263") (name "unconnected-(U3-RI#-Pad11)") (class "Default")
      (node (ref "U3") (pin "11") (pinfunction "RI#_11") (pintype "unspecified+no_connect"))
    )
    (net (code "264") (name "unconnected-(U3-RST#-Pad7)") (class "Default")
      (node (ref "U3") (pin "7") (pinfunction "RST#_7") (pintype "unspecified+no_connect"))
    )
    (net (code "265") (name "unconnected-(U3-RTS#-Pad14)") (class "Default")
      (node (ref "U3") (pin "14") (pinfunction "RTS#_14") (pintype "unspecified+no_connect"))
    )
    (net (code "266") (name "unconnected-(U3-TNOW-Pad15)") (class "Default")
      (node (ref "U3") (pin "15") (pinfunction "TNOW_15") (pintype "unspecified+no_connect"))
    )
    (net (code "267") (name "unconnected-(U5-ADC6-Pad19)") (class "Default")
      (node (ref "U5") (pin "19") (pinfunction "ADC6_19") (pintype "unspecified+no_connect"))
    )
    (net (code "268") (name "unconnected-(U6-CTS#-Pad9)") (class "Default")
      (node (ref "U6") (pin "9") (pinfunction "CTS#_9") (pintype "unspecified+no_connect"))
    )
    (net (code "269") (name "unconnected-(U6-DCD#-Pad12)") (class "Default")
      (node (ref "U6") (pin "12") (pinfunction "DCD#_12") (pintype "unspecified+no_connect"))
    )
    (net (code "270") (name "unconnected-(U6-DSR#-Pad10)") (class "Default")
      (node (ref "U6") (pin "10") (pinfunction "DSR#_10") (pintype "unspecified+no_connect"))
    )
    (net (code "271") (name "unconnected-(U6-DTR#-Pad13)") (class "Default")
      (node (ref "U6") (pin "13") (pinfunction "DTR#_13") (pintype "unspecified+no_connect"))
    )
    (net (code "272") (name "unconnected-(U6-NC.-Pad8)") (class "Default")
      (node (ref "U6") (pin "8") (pinfunction "NC._8") (pintype "unspecified+no_connect"))
    )
    (net (code "273") (name "unconnected-(U6-RI#-Pad11)") (class "Default")
      (node (ref "U6") (pin "11") (pinfunction "RI#_11") (pintype "unspecified+no_connect"))
    )
    (net (code "274") (name "unconnected-(U6-RST#-Pad7)") (class "Default")
      (node (ref "U6") (pin "7") (pinfunction "RST#_7") (pintype "unspecified+no_connect"))
    )
    (net (code "275") (name "unconnected-(U6-RTS#-Pad14)") (class "Default")
      (node (ref "U6") (pin "14") (pinfunction "RTS#_14") (pintype "unspecified+no_connect"))
    )
    (net (code "276") (name "unconnected-(U10-OUT-Pad4)") (class "Default")
      (node (ref "U10") (pin "4") (pinfunction "OUT_4") (pintype "unspecified+no_connect"))
    )
    (net (code "277") (name "unconnected-(U11-PIO0_0{slash}CAN1_RD-Pad93)") (class "Default")
      (node (ref "U11") (pin "93") (pinfunction "PIO0_0/CAN1_RD_93") (pintype "bidirectional+no_connect"))
    )
    (net (code "278") (name "unconnected-(U11-PIO0_1{slash}CAN1_TD-Pad100)") (class "Default")
      (node (ref "U11") (pin "100") (pinfunction "PIO0_1/CAN1_TD_100") (pintype "bidirectional+no_connect"))
    )
    (net (code "279") (name "unconnected-(U11-PIO0_2{slash}FC3_TXD_SCL_MISO-Pad83)") (class "Default")
      (node (ref "U11") (pin "83") (pinfunction "PIO0_2/FC3_TXD_SCL_MISO_83") (pintype "bidirectional+no_connect"))
    )
    (net (code "280") (name "unconnected-(U11-PIO0_3{slash}FC3_RXD_SDA_MOSI-Pad85)") (class "Default")
      (node (ref "U11") (pin "85") (pinfunction "PIO0_3/FC3_RXD_SDA_MOSI_85") (pintype "bidirectional+no_connect"))
    )
    (net (code "281") (name "unconnected-(U11-PIO0_4{slash}CAN0_RD-Pad87)") (class "Default")
      (node (ref "U11") (pin "87") (pinfunction "PIO0_4/CAN0_RD_87") (pintype "bidirectional+no_connect"))
    )
    (net (code "282") (name "unconnected-(U11-PIO0_7{slash}FC5_SCK-Pad61)") (class "Default")
      (node (ref "U11") (pin "61") (pinfunction "PIO0_7/FC5_SCK_61") (pintype "bidirectional+no_connect"))
    )
    (net (code "283") (name "unconnected-(U11-PIO0_8{slash}FC5_RXD_SDA_MOSI-Pad64)") (class "Default")
      (node (ref "U11") (pin "64") (pinfunction "PIO0_8/FC5_RXD_SDA_MOSI_64") (pintype "bidirectional+no_connect"))
    )
    (net (code "284") (name "unconnected-(U11-PIO0_9{slash}FC5_TXD_SCL_MISO-Pad65)") (class "Default")
      (node (ref "U11") (pin "65") (pinfunction "PIO0_9/FC5_TXD_SCL_MISO_65") (pintype "bidirectional+no_connect"))
    )
    (net (code "285") (name "unconnected-(U11-PIO0_10{slash}SWO-Pad23)") (class "Default")
      (node (ref "U11") (pin "23") (pinfunction "PIO0_10/SWO_23") (pintype "unspecified+no_connect"))
    )
    (net (code "286") (name "unconnected-(U11-PIO0_13{slash}FC1_CTS_SDA_SSEL0-Pad67)") (class "Default")
      (node (ref "U11") (pin "67") (pinfunction "PIO0_13/FC1_CTS_SDA_SSEL0_67") (pintype "bidirectional+no_connect"))
    )
    (net (code "287") (name "unconnected-(U11-PIO0_14{slash}FC1_RTS_SCL_SSEL1-Pad69)") (class "Default")
      (node (ref "U11") (pin "69") (pinfunction "PIO0_14/FC1_RTS_SCL_SSEL1_69") (pintype "bidirectional+no_connect"))
    )
    (net (code "288") (name "unconnected-(U11-PIO0_15{slash}ADC0_3-Pad26)") (class "Default")
      (node (ref "U11") (pin "26") (pinfunction "PIO0_15/ADC0_3_26") (pintype "bidirectional+no_connect"))
    )
    (net (code "289") (name "unconnected-(U11-PIO0_16{slash}ADC0_4-Pad27)") (class "Default")
      (node (ref "U11") (pin "27") (pinfunction "PIO0_16/ADC0_4_27") (pintype "bidirectional+no_connect"))
    )
    (net (code "290") (name "unconnected-(U11-PIO0_17{slash}FC4_SSEL2-Pad70)") (class "Default")
      (node (ref "U11") (pin "70") (pinfunction "PIO0_17/FC4_SSEL2_70") (pintype "bidirectional+no_connect"))
    )
    (net (code "291") (name "unconnected-(U11-PIO0_18{slash}FC4_CTS_SDA_SSEL0-Pad72)") (class "Default")
      (node (ref "U11") (pin "72") (pinfunction "PIO0_18/FC4_CTS_SDA_SSEL0_72") (pintype "bidirectional+no_connect"))
    )
    (net (code "292") (name "unconnected-(U11-PIO0_19{slash}FC4_RTS_SCL_SSEL1-Pad91)") (class "Default")
      (node (ref "U11") (pin "91") (pinfunction "PIO0_19/FC4_RTS_SCL_SSEL1_91") (pintype "bidirectional+no_connect"))
    )
    (net (code "293") (name "unconnected-(U11-PIO0_20{slash}FC3_CTS_SDA_SSEL0-Pad74)") (class "Default")
      (node (ref "U11") (pin "74") (pinfunction "PIO0_20/FC3_CTS_SDA_SSEL0_74") (pintype "bidirectional+no_connect"))
    )
    (net (code "294") (name "unconnected-(U11-PIO0_21{slash}FC3_RTS_SCL_SSEL1-Pad77)") (class "Default")
      (node (ref "U11") (pin "77") (pinfunction "PIO0_21/FC3_RTS_SCL_SSEL1_77") (pintype "bidirectional+no_connect"))
    )
    (net (code "295") (name "unconnected-(U11-PIO0_22{slash}FC6_TXD_SCL_MISO_WS-Pad80)") (class "Default")
      (node (ref "U11") (pin "80") (pinfunction "PIO0_22/FC6_TXD_SCL_MISO_WS_80") (pintype "bidirectional+no_connect"))
    )
    (net (code "296") (name "unconnected-(U11-PIO0_25{slash}SPIFI_IO1-Pad40)") (class "Default")
      (node (ref "U11") (pin "40") (pinfunction "PIO0_25/SPIFI_IO1_40") (pintype "bidirectional+no_connect"))
    )
    (net (code "297") (name "unconnected-(U11-PIO0_26{slash}SPIFI_CLK-Pad56)") (class "Default")
      (node (ref "U11") (pin "56") (pinfunction "PIO0_26/SPIFI_CLK_56") (pintype "bidirectional+no_connect"))
    )
    (net (code "298") (name "unconnected-(U11-PIO0_27{slash}SPIFI_IO3-Pad42)") (class "Default")
      (node (ref "U11") (pin "42") (pinfunction "PIO0_27/SPIFI_IO3_42") (pintype "bidirectional+no_connect"))
    )
    (net (code "299") (name "unconnected-(U11-PIO0_28{slash}SPIFI_IO2-Pad44)") (class "Default")
      (node (ref "U11") (pin "44") (pinfunction "PIO0_28/SPIFI_IO2_44") (pintype "bidirectional+no_connect"))
    )
    (net (code "300") (name "unconnected-(U11-PIO0_29{slash}FC0_RXD_SDA_MOSI-Pad82)") (class "Default")
      (node (ref "U11") (pin "82") (pinfunction "PIO0_29/FC0_RXD_SDA_MOSI_82") (pintype "bidirectional+no_connect"))
    )
    (net (code "301") (name "unconnected-(U11-PIO0_30{slash}PIO0_30-Pad95)") (class "Default")
      (node (ref "U11") (pin "95") (pinfunction "PIO0_30/PIO0_30_95") (pintype "bidirectional+no_connect"))
    )
    (net (code "302") (name "unconnected-(U11-PIO0_31{slash}SD_D2-Pad28)") (class "Default")
      (node (ref "U11") (pin "28") (pinfunction "PIO0_31/SD_D2_28") (pintype "bidirectional+no_connect"))
    )
    (net (code "303") (name "unconnected-(U11-PIO1_0{slash}SD_D3-Pad29)") (class "Default")
      (node (ref "U11") (pin "29") (pinfunction "PIO1_0/SD_D3_29") (pintype "bidirectional+no_connect"))
    )
    (net (code "304") (name "unconnected-(U11-PIO1_1{slash}FC3_RXD_SDA_MOSI-Pad55)") (class "Default")
      (node (ref "U11") (pin "55") (pinfunction "PIO1_1/FC3_RXD_SDA_MOSI_55") (pintype "bidirectional+no_connect"))
    )
    (net (code "305") (name "unconnected-(U11-PIO1_4{slash}SD_D0-Pad3)") (class "Default")
      (node (ref "U11") (pin "3") (pinfunction "PIO1_4/SD_D0_3") (pintype "bidirectional+no_connect"))
    )
    (net (code "306") (name "unconnected-(U11-PIO1_5{slash}FC0_RXD_SDA_MOSI-Pad4)") (class "Default")
      (node (ref "U11") (pin "4") (pinfunction "PIO1_5/FC0_RXD_SDA_MOSI_4") (pintype "bidirectional+no_connect"))
    )
    (net (code "307") (name "unconnected-(U11-PIO1_6{slash}FC0_TXD_SCL_MISO-Pad15)") (class "Default")
      (node (ref "U11") (pin "15") (pinfunction "PIO1_6/FC0_TXD_SCL_MISO_15") (pintype "bidirectional+no_connect"))
    )
    (net (code "308") (name "unconnected-(U11-PIO1_7{slash}SD_D1-Pad18)") (class "Default")
      (node (ref "U11") (pin "18") (pinfunction "PIO1_7/SD_D1_18") (pintype "bidirectional+no_connect"))
    )
    (net (code "309") (name "unconnected-(U11-PIO1_9{slash}FC4_CTS_SDA_SSEL0-Pad39)") (class "Default")
      (node (ref "U11") (pin "39") (pinfunction "PIO1_9/FC4_CTS_SDA_SSEL0_39") (pintype "bidirectional+no_connect"))
    )
    (net (code "310") (name "unconnected-(U11-PIO1_10{slash}ENET_TXD1-Pad41)") (class "Default")
      (node (ref "U11") (pin "41") (pinfunction "PIO1_10/ENET_TXD1_41") (pintype "bidirectional+no_connect"))
    )
    (net (code "311") (name "unconnected-(U11-PIO1_11{slash}ENET_TX_EN-Pad94)") (class "Default")
      (node (ref "U11") (pin "94") (pinfunction "PIO1_11/ENET_TX_EN_94") (pintype "bidirectional+no_connect"))
    )
    (net (code "312") (name "unconnected-(U11-PIO1_12{slash}ENET_RXD0-Pad62)") (class "Default")
      (node (ref "U11") (pin "62") (pinfunction "PIO1_12/ENET_RXD0_62") (pintype "bidirectional+no_connect"))
    )
    (net (code "313") (name "unconnected-(U11-PIO1_13{slash}ENET_RXD1-Pad66)") (class "Default")
      (node (ref "U11") (pin "66") (pinfunction "PIO1_13/ENET_RXD1_66") (pintype "bidirectional+no_connect"))
    )
    (net (code "314") (name "unconnected-(U11-PIO1_14{slash}FC5_CTS_SDA_SSEL0-Pad78)") (class "Default")
      (node (ref "U11") (pin "78") (pinfunction "PIO1_14/FC5_CTS_SDA_SSEL0_78") (pintype "bidirectional+no_connect"))
    )
    (net (code "315") (name "unconnected-(U11-PIO1_15{slash}ENET_RX_CLK-Pad84)") (class "Default")
      (node (ref "U11") (pin "84") (pinfunction "PIO1_15/ENET_RX_CLK_84") (pintype "bidirectional+no_connect"))
    )
    (net (code "316") (name "unconnected-(U11-PIO1_16{slash}ENET_MDC-Pad88)") (class "Default")
      (node (ref "U11") (pin "88") (pinfunction "PIO1_16/ENET_MDC_88") (pintype "bidirectional+no_connect"))
    )
    (net (code "317") (name "unconnected-(U11-PIO1_19{slash}FC4_SCK-Pad16)") (class "Default")
      (node (ref "U11") (pin "16") (pinfunction "PIO1_19/FC4_SCK_16") (pintype "bidirectional+no_connect"))
    )
    (net (code "318") (name "unconnected-(U11-PIO1_20{slash}FC4_TXD_SCL_MISO-Pad17)") (class "Default")
      (node (ref "U11") (pin "17") (pinfunction "PIO1_20/FC4_TXD_SCL_MISO_17") (pintype "bidirectional+no_connect"))
    )
    (net (code "319") (name "unconnected-(U11-PIO1_22{slash}SD_CMD-Pad43)") (class "Default")
      (node (ref "U11") (pin "43") (pinfunction "PIO1_22/SD_CMD_43") (pintype "bidirectional+no_connect"))
    )
    (net (code "320") (name "unconnected-(U11-PIO1_23{slash}FC2_SCK-Pad46)") (class "Default")
      (node (ref "U11") (pin "46") (pinfunction "PIO1_23/FC2_SCK_46") (pintype "bidirectional+no_connect"))
    )
    (net (code "321") (name "unconnected-(U11-PIO1_24{slash}FC2_RXD_SDA_MOSI-Pad57)") (class "Default")
      (node (ref "U11") (pin "57") (pinfunction "PIO1_24/FC2_RXD_SDA_MOSI_57") (pintype "bidirectional+no_connect"))
    )
    (net (code "322") (name "unconnected-(U11-PIO1_25{slash}FC2_TXD_SCL_MISO-Pad59)") (class "Default")
      (node (ref "U11") (pin "59") (pinfunction "PIO1_25/FC2_TXD_SCL_MISO_59") (pintype "bidirectional+no_connect"))
    )
    (net (code "323") (name "unconnected-(U11-PIO1_26{slash}FC2_CTS_SDA_SSEL0-Pad63)") (class "Default")
      (node (ref "U11") (pin "63") (pinfunction "PIO1_26/FC2_CTS_SDA_SSEL0_63") (pintype "bidirectional+no_connect"))
    )
    (net (code "324") (name "unconnected-(U11-PIO1_27{slash}CLKOUT-Pad68)") (class "Default")
      (node (ref "U11") (pin "68") (pinfunction "PIO1_27/CLKOUT_68") (pintype "bidirectional+no_connect"))
    )
    (net (code "325") (name "unconnected-(U11-PIO1_28{slash}FC7_SCK-Pad73)") (class "Default")
      (node (ref "U11") (pin "73") (pinfunction "PIO1_28/FC7_SCK_73") (pintype "bidirectional+no_connect"))
    )
    (net (code "326") (name "unconnected-(U11-PIO1_29{slash}FC7_RXD_SDA_MOSI_DATA-Pad81)") (class "Default")
      (node (ref "U11") (pin "81") (pinfunction "PIO1_29/FC7_RXD_SDA_MOSI_DATA_81") (pintype "bidirectional+no_connect"))
    )
    (net (code "327") (name "unconnected-(U11-PIO1_30{slash}USB1_UP_LED-Pad86)") (class "Default")
      (node (ref "U11") (pin "86") (pinfunction "PIO1_30/USB1_UP_LED_86") (pintype "bidirectional+no_connect"))
    )
    (net (code "328") (name "unconnected-(U11-PIO1_31{slash}MCLK-Pad92)") (class "Default")
      (node (ref "U11") (pin "92") (pinfunction "PIO1_31/MCLK_92") (pintype "bidirectional+no_connect"))
    )
    (net (code "329") (name "unconnected-(U11-RTCXOUT-Pad52)") (class "Default")
      (node (ref "U11") (pin "52") (pinfunction "RTCXOUT_52") (pintype "unspecified+no_connect"))
    )
    (net (code "330") (name "unconnected-(U11-USB0_DM-Pad98)") (class "Default")
      (node (ref "U11") (pin "98") (pinfunction "USB0_DM_98") (pintype "unspecified+no_connect"))
    )
    (net (code "331") (name "unconnected-(U11-USB0_DP-Pad97)") (class "Default")
      (node (ref "U11") (pin "97") (pinfunction "USB0_DP_97") (pintype "unspecified+no_connect"))
    )
    (net (code "332") (name "unconnected-(U11-USB1_ID-Pad8)") (class "Default")
      (node (ref "U11") (pin "8") (pinfunction "USB1_ID_8") (pintype "unspecified+no_connect"))
    )
    (net (code "333") (name "unconnected-(U14-NC-Pad5)") (class "Default")
      (node (ref "U14") (pin "5") (pinfunction "NC_5") (pintype "unspecified+no_connect"))
    )
    (net (code "334") (name "unconnected-(U15-Factory_Use-Pad5)") (class "Default")
      (node (ref "U15") (pin "5") (pinfunction "Factory_Use_5") (pintype "input+no_connect"))
    )
    (net (code "335") (name "unconnected-(U15-Mode-Pad4)") (class "Default")
      (node (ref "U15") (pin "4") (pinfunction "Mode_4") (pintype "input+no_connect"))
    )
    (net (code "336") (name "unconnected-(U16-Bias-Pad4)") (class "Default")
      (node (ref "U16") (pin "4") (pinfunction "Bias_4") (pintype "unspecified+no_connect"))
    )
    (net (code "337") (name "unconnected-(U16-CAN2RX-Pad12)") (class "Default")
      (node (ref "U16") (pin "12") (pinfunction "CAN2RX_12") (pintype "unspecified+no_connect"))
    )
    (net (code "338") (name "unconnected-(U16-CAN2TX{slash}{slash}-Pad24)") (class "Default")
      (node (ref "U16") (pin "24") (pinfunction "CAN2TX//_24") (pintype "unspecified+no_connect"))
    )
    (net (code "339") (name "unconnected-(U16-CANTX{slash}{slash}-Pad11)") (class "Default")
      (node (ref "U16") (pin "11") (pinfunction "CANTX//_11") (pintype "unspecified+no_connect"))
    )
    (net (code "340") (name "unconnected-(U16-Link_Act-Pad3)") (class "Default")
      (node (ref "U16") (pin "3") (pinfunction "Link_Act_3") (pintype "unspecified+no_connect"))
    )
    (net (code "341") (name "unconnected-(U16-MISO{slash}RxD3-Pad8)") (class "Default")
      (node (ref "U16") (pin "8") (pinfunction "MISO/RxD3_8") (pintype "unspecified+no_connect"))
    )
    (net (code "342") (name "unconnected-(U16-MOSI{slash}SDA-Pad1)") (class "Default")
      (node (ref "U16") (pin "1") (pinfunction "MOSI/SDA_1") (pintype "unspecified+no_connect"))
    )
    (net (code "343") (name "unconnected-(U16-PPS-Pad23)") (class "Default")
      (node (ref "U16") (pin "23") (pinfunction "PPS_23") (pintype "unspecified+no_connect"))
    )
    (net (code "344") (name "unconnected-(U16-RD+-Pad26)") (class "Default")
      (node (ref "U16") (pin "26") (pinfunction "RD+_26") (pintype "unspecified+no_connect"))
    )
    (net (code "345") (name "unconnected-(U16-RD--Pad28)") (class "Default")
      (node (ref "U16") (pin "28") (pinfunction "RD-_28") (pintype "unspecified+no_connect"))
    )
    (net (code "346") (name "unconnected-(U16-RxD2{slash}{slash}-Pad19)") (class "Default")
      (node (ref "U16") (pin "19") (pinfunction "RxD2//_19") (pintype "unspecified+no_connect"))
    )
    (net (code "347") (name "unconnected-(U16-TD+-Pad25)") (class "Default")
      (node (ref "U16") (pin "25") (pinfunction "TD+_25") (pintype "unspecified+no_connect"))
    )
    (net (code "348") (name "unconnected-(U16-TD--Pad27)") (class "Default")
      (node (ref "U16") (pin "27") (pinfunction "TD-_27") (pintype "unspecified+no_connect"))
    )
    (net (code "349") (name "unconnected-(U16-TxD2{slash}{slash}-Pad18)") (class "Default")
      (node (ref "U16") (pin "18") (pinfunction "TxD2//_18") (pintype "unspecified+no_connect"))
    )
    (net (code "350") (name "unconnected-(U16-TxD3-Pad13)") (class "Default")
      (node (ref "U16") (pin "13") (pinfunction "TxD3_13") (pintype "unspecified+no_connect"))
    )
    (net (code "351") (name "unconnected-(U16-_CS{slash}SCL-Pad2)") (class "Default")
      (node (ref "U16") (pin "2") (pinfunction "_CS/SCL_2") (pintype "unspecified+no_connect"))
    )
    (net (code "352") (name "unconnected-(U16-_Reset-Pad9)") (class "Default")
      (node (ref "U16") (pin "9") (pinfunction "_Reset_9") (pintype "unspecified+no_connect"))
    )
    (net (code "353") (name "unconnected-(U16-n.c.-Pad5)") (class "Default")
      (node (ref "U16") (pin "5") (pinfunction "n.c._5") (pintype "unspecified+no_connect"))
    )
    (net (code "354") (name "unconnected-(U17-ALERT{slash}RDY-Pad2)") (class "Default")
      (node (ref "U17") (pin "2") (pinfunction "ALERT/RDY_2") (pintype "unspecified+no_connect"))
    )
    (net (code "355") (name "unconnected-(U18-INT1-Pad11)") (class "Default")
      (node (ref "U18") (pin "11") (pinfunction "INT1_11") (pintype "unspecified+no_connect"))
    )
    (net (code "356") (name "unconnected-(U18-INT2-Pad9)") (class "Default")
      (node (ref "U18") (pin "9") (pinfunction "INT2_9") (pintype "unspecified+no_connect"))
    )
    (net (code "357") (name "unconnected-(U18-NC-Pad3)") (class "Default")
      (node (ref "U18") (pin "3") (pinfunction "NC_3") (pintype "unspecified+no_connect"))
    )
    (net (code "358") (name "unconnected-(U18-NC-Pad8)") (class "Default")
      (node (ref "U18") (pin "8") (pinfunction "NC_8") (pintype "unspecified+no_connect"))
    )
    (net (code "359") (name "unconnected-(U18-NC-Pad13)") (class "Default")
      (node (ref "U18") (pin "13") (pinfunction "NC_13") (pintype "unspecified+no_connect"))
    )
    (net (code "360") (name "unconnected-(U18-NC-Pad15)") (class "Default")
      (node (ref "U18") (pin "15") (pinfunction "NC_15") (pintype "unspecified+no_connect"))
    )
    (net (code "361") (name "unconnected-(U18-NC-Pad16)") (class "Default")
      (node (ref "U18") (pin "16") (pinfunction "NC_16") (pintype "unspecified+no_connect"))
    )
    (net (code "362") (name "unconnected-(U19-CTS#-Pad9)") (class "Default")
      (node (ref "U19") (pin "9") (pinfunction "CTS#_9") (pintype "unspecified+no_connect"))
    )
    (net (code "363") (name "unconnected-(U19-DCD#-Pad12)") (class "Default")
      (node (ref "U19") (pin "12") (pinfunction "DCD#_12") (pintype "unspecified+no_connect"))
    )
    (net (code "364") (name "unconnected-(U19-DSR#-Pad10)") (class "Default")
      (node (ref "U19") (pin "10") (pinfunction "DSR#_10") (pintype "unspecified+no_connect"))
    )
    (net (code "365") (name "unconnected-(U19-DTR#-Pad13)") (class "Default")
      (node (ref "U19") (pin "13") (pinfunction "DTR#_13") (pintype "unspecified+no_connect"))
    )
    (net (code "366") (name "unconnected-(U19-NC.-Pad8)") (class "Default")
      (node (ref "U19") (pin "8") (pinfunction "NC._8") (pintype "unspecified+no_connect"))
    )
    (net (code "367") (name "unconnected-(U19-RI#-Pad11)") (class "Default")
      (node (ref "U19") (pin "11") (pinfunction "RI#_11") (pintype "unspecified+no_connect"))
    )
    (net (code "368") (name "unconnected-(U19-RST#-Pad7)") (class "Default")
      (node (ref "U19") (pin "7") (pinfunction "RST#_7") (pintype "unspecified+no_connect"))
    )
    (net (code "369") (name "unconnected-(U19-RTS#-Pad14)") (class "Default")
      (node (ref "U19") (pin "14") (pinfunction "RTS#_14") (pintype "unspecified+no_connect"))
    )
    (net (code "370") (name "unconnected-(U19-TNOW-Pad15)") (class "Default")
      (node (ref "U19") (pin "15") (pinfunction "TNOW_15") (pintype "unspecified+no_connect"))
    )
  )
)
